# 2_keys.net
KiCad netlist of a schematic drawn in Altium Designer
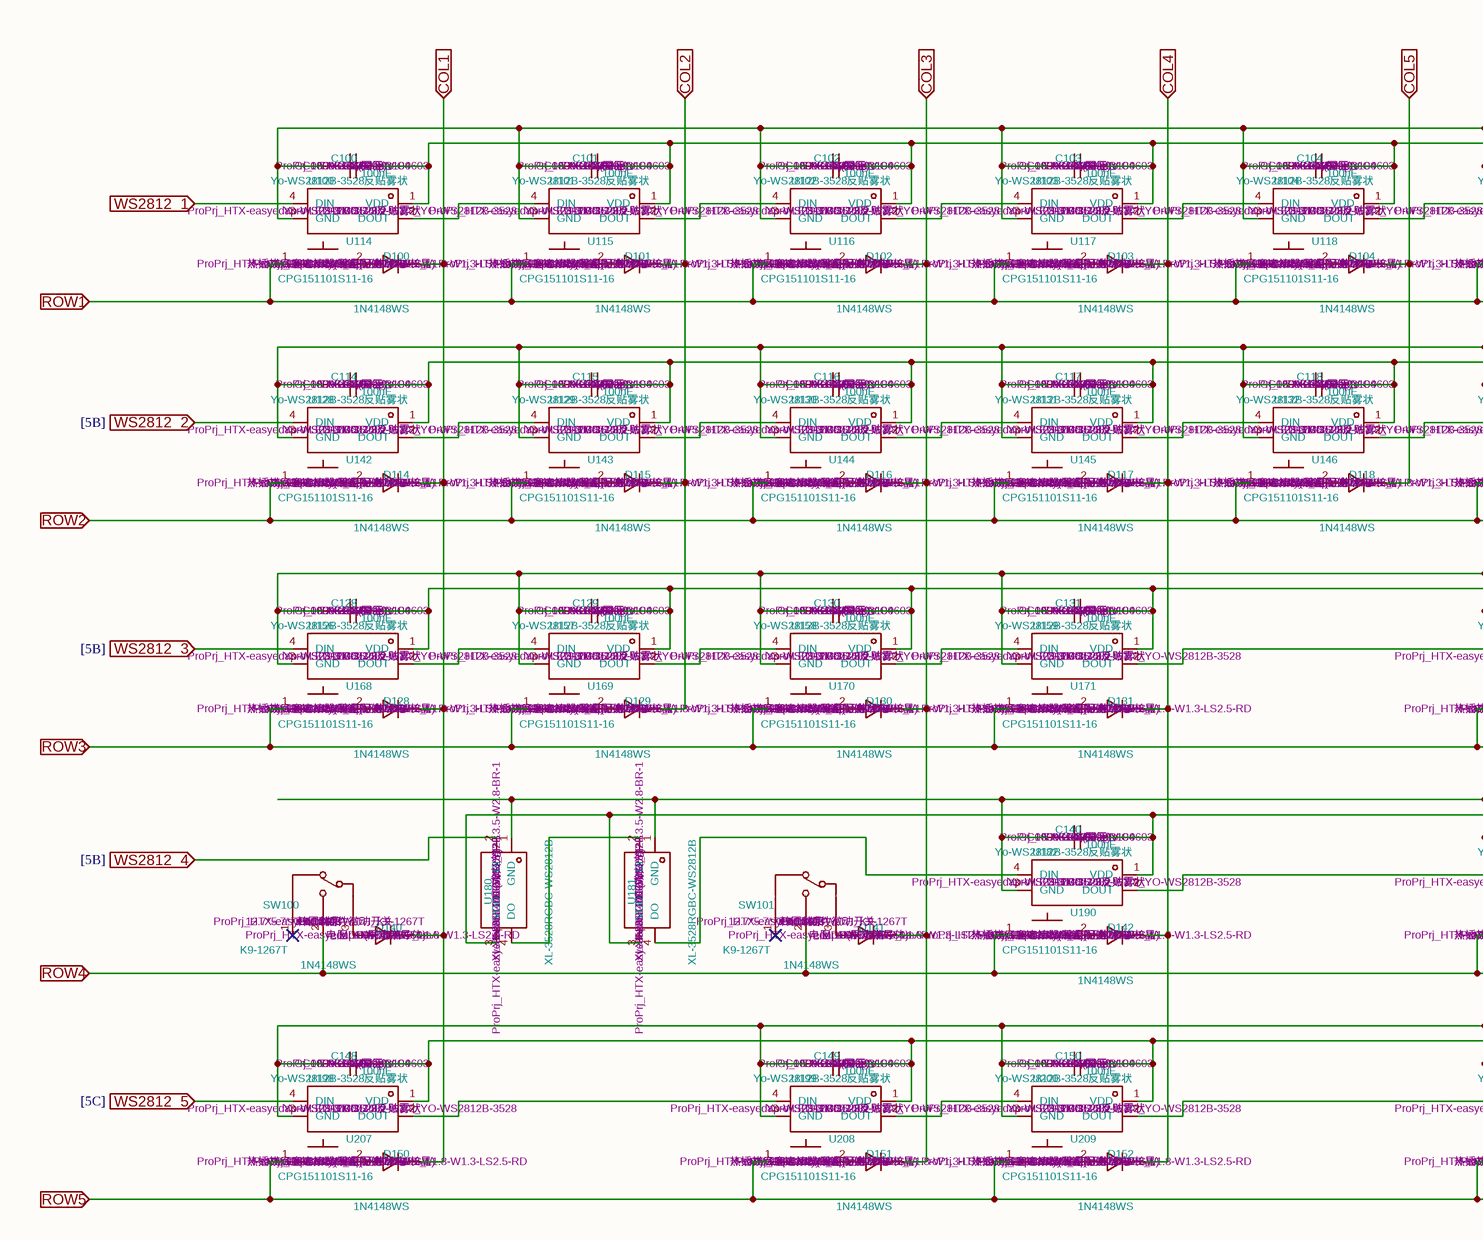
[diagram p0: 2_keys.SchDoc, left]
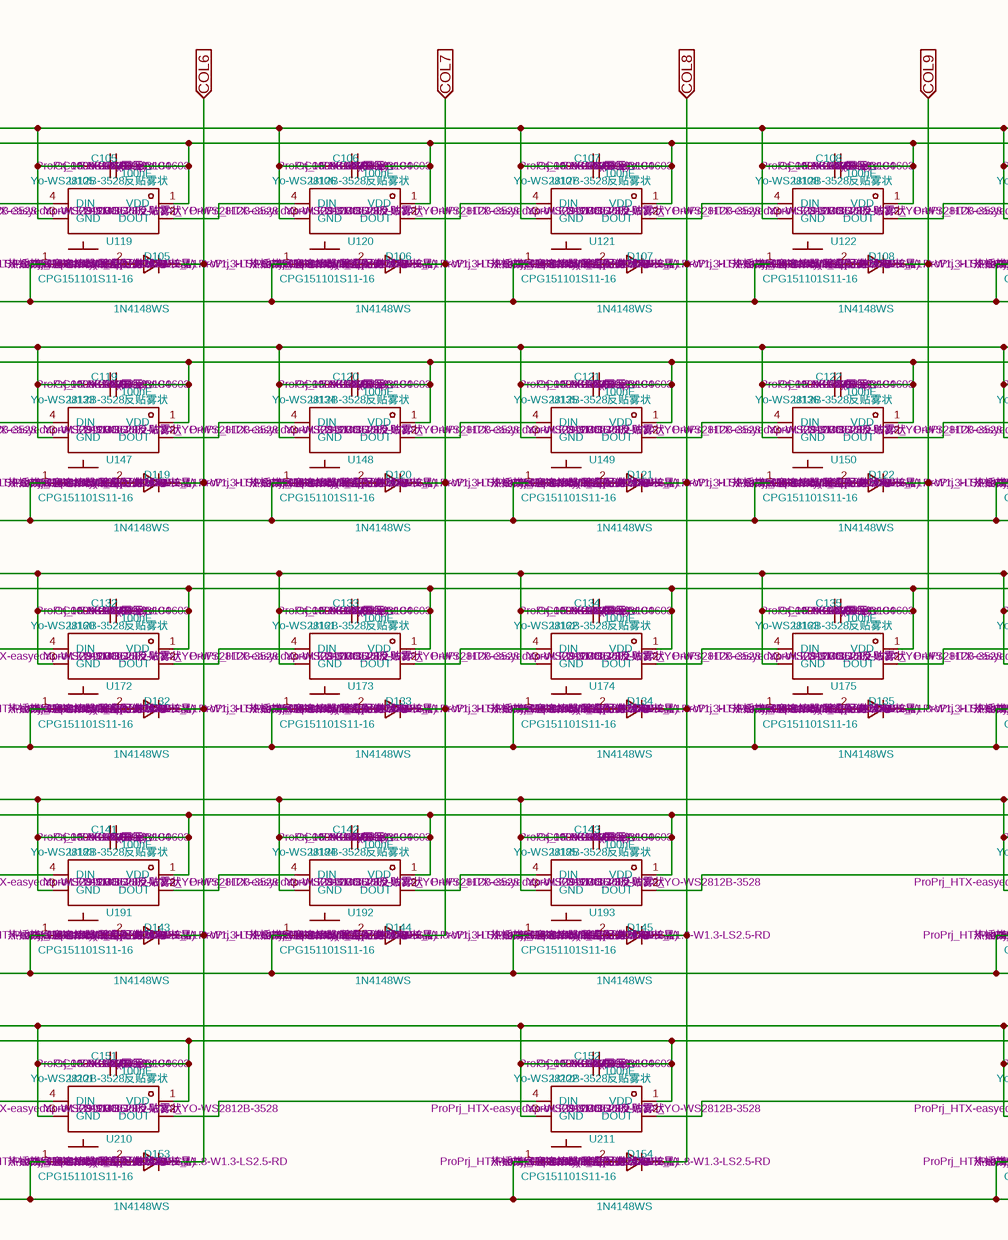
[diagram p1: 2_keys.SchDoc, middle]
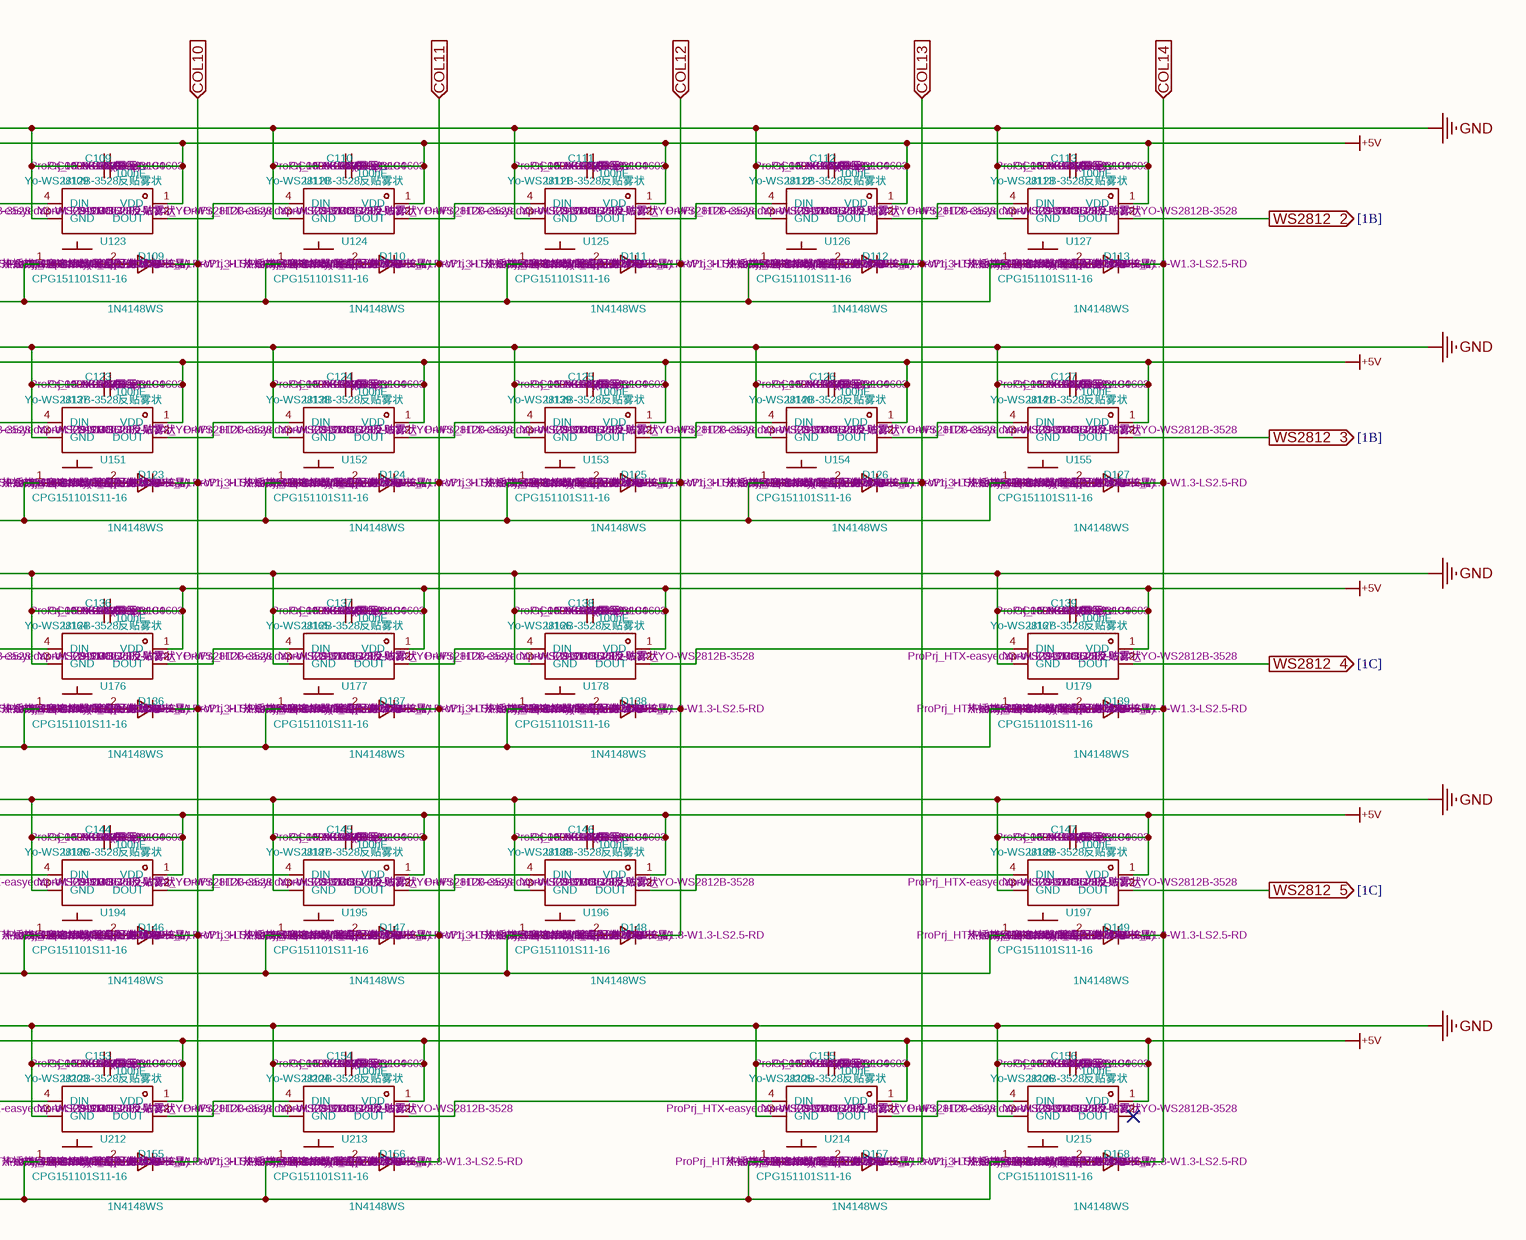
[diagram p2: 2_keys.SchDoc, right]

(export (version "E")
  (design (tool "Eeschema 10.0.6"))
  (components
    (comp (ref "C100")
      (value "100nF")
      (footprint "ProPrj_HTX-easyedapro:C0603")
      (fields
        (field (name "MANUFACTURER PART") "CC0603KRX7R9BB104")
        (field (name "MANUFACTURER") "YAGEO(国巨)")
        (field (name "SUPPLIER PART") "C14663")
        (field (name "SUPPLIER") "LCSC")
        (field (name "LCSC PART NAME") "100nF ±10% 50V")
      )
      (libsource (lib "easyedapro") (part "CC0603KRX7R9BB104"))
    )
    (comp (ref "C101")
      (value "100nF")
      (footprint "ProPrj_HTX-easyedapro:C0603")
      (fields
        (field (name "MANUFACTURER PART") "CC0603KRX7R9BB104")
        (field (name "MANUFACTURER") "YAGEO(国巨)")
        (field (name "SUPPLIER PART") "C14663")
        (field (name "SUPPLIER") "LCSC")
        (field (name "LCSC PART NAME") "100nF ±10% 50V")
      )
      (libsource (lib "easyedapro") (part "CC0603KRX7R9BB104"))
    )
    (comp (ref "C102")
      (value "100nF")
      (footprint "ProPrj_HTX-easyedapro:C0603")
      (fields
        (field (name "MANUFACTURER PART") "CC0603KRX7R9BB104")
        (field (name "MANUFACTURER") "YAGEO(国巨)")
        (field (name "SUPPLIER PART") "C14663")
        (field (name "SUPPLIER") "LCSC")
        (field (name "LCSC PART NAME") "100nF ±10% 50V")
      )
      (libsource (lib "easyedapro") (part "CC0603KRX7R9BB104"))
    )
    (comp (ref "C103")
      (value "100nF")
      (footprint "ProPrj_HTX-easyedapro:C0603")
      (fields
        (field (name "MANUFACTURER PART") "CC0603KRX7R9BB104")
        (field (name "MANUFACTURER") "YAGEO(国巨)")
        (field (name "SUPPLIER PART") "C14663")
        (field (name "SUPPLIER") "LCSC")
        (field (name "LCSC PART NAME") "100nF ±10% 50V")
      )
      (libsource (lib "easyedapro") (part "CC0603KRX7R9BB104"))
    )
    (comp (ref "C104")
      (value "100nF")
      (footprint "ProPrj_HTX-easyedapro:C0603")
      (fields
        (field (name "MANUFACTURER PART") "CC0603KRX7R9BB104")
        (field (name "MANUFACTURER") "YAGEO(国巨)")
        (field (name "SUPPLIER PART") "C14663")
        (field (name "SUPPLIER") "LCSC")
        (field (name "LCSC PART NAME") "100nF ±10% 50V")
      )
      (libsource (lib "easyedapro") (part "CC0603KRX7R9BB104"))
    )
    (comp (ref "C105")
      (value "100nF")
      (footprint "ProPrj_HTX-easyedapro:C0603")
      (fields
        (field (name "MANUFACTURER PART") "CC0603KRX7R9BB104")
        (field (name "MANUFACTURER") "YAGEO(国巨)")
        (field (name "SUPPLIER PART") "C14663")
        (field (name "SUPPLIER") "LCSC")
        (field (name "LCSC PART NAME") "100nF ±10% 50V")
      )
      (libsource (lib "easyedapro") (part "CC0603KRX7R9BB104"))
    )
    (comp (ref "C106")
      (value "100nF")
      (footprint "ProPrj_HTX-easyedapro:C0603")
      (fields
        (field (name "MANUFACTURER PART") "CC0603KRX7R9BB104")
        (field (name "MANUFACTURER") "YAGEO(国巨)")
        (field (name "SUPPLIER PART") "C14663")
        (field (name "SUPPLIER") "LCSC")
        (field (name "LCSC PART NAME") "100nF ±10% 50V")
      )
      (libsource (lib "easyedapro") (part "CC0603KRX7R9BB104"))
    )
    (comp (ref "C107")
      (value "100nF")
      (footprint "ProPrj_HTX-easyedapro:C0603")
      (fields
        (field (name "MANUFACTURER PART") "CC0603KRX7R9BB104")
        (field (name "MANUFACTURER") "YAGEO(国巨)")
        (field (name "SUPPLIER PART") "C14663")
        (field (name "SUPPLIER") "LCSC")
        (field (name "LCSC PART NAME") "100nF ±10% 50V")
      )
      (libsource (lib "easyedapro") (part "CC0603KRX7R9BB104"))
    )
    (comp (ref "C108")
      (value "100nF")
      (footprint "ProPrj_HTX-easyedapro:C0603")
      (fields
        (field (name "MANUFACTURER PART") "CC0603KRX7R9BB104")
        (field (name "MANUFACTURER") "YAGEO(国巨)")
        (field (name "SUPPLIER PART") "C14663")
        (field (name "SUPPLIER") "LCSC")
        (field (name "LCSC PART NAME") "100nF ±10% 50V")
      )
      (libsource (lib "easyedapro") (part "CC0603KRX7R9BB104"))
    )
    (comp (ref "C109")
      (value "100nF")
      (footprint "ProPrj_HTX-easyedapro:C0603")
      (fields
        (field (name "MANUFACTURER PART") "CC0603KRX7R9BB104")
        (field (name "MANUFACTURER") "YAGEO(国巨)")
        (field (name "SUPPLIER PART") "C14663")
        (field (name "SUPPLIER") "LCSC")
        (field (name "LCSC PART NAME") "100nF ±10% 50V")
      )
      (libsource (lib "easyedapro") (part "CC0603KRX7R9BB104"))
    )
    (comp (ref "C110")
      (value "100nF")
      (footprint "ProPrj_HTX-easyedapro:C0603")
      (fields
        (field (name "MANUFACTURER PART") "CC0603KRX7R9BB104")
        (field (name "MANUFACTURER") "YAGEO(国巨)")
        (field (name "SUPPLIER PART") "C14663")
        (field (name "SUPPLIER") "LCSC")
        (field (name "LCSC PART NAME") "100nF ±10% 50V")
      )
      (libsource (lib "easyedapro") (part "CC0603KRX7R9BB104"))
    )
    (comp (ref "C111")
      (value "100nF")
      (footprint "ProPrj_HTX-easyedapro:C0603")
      (fields
        (field (name "MANUFACTURER PART") "CC0603KRX7R9BB104")
        (field (name "MANUFACTURER") "YAGEO(国巨)")
        (field (name "SUPPLIER PART") "C14663")
        (field (name "SUPPLIER") "LCSC")
        (field (name "LCSC PART NAME") "100nF ±10% 50V")
      )
      (libsource (lib "easyedapro") (part "CC0603KRX7R9BB104"))
    )
    (comp (ref "C112")
      (value "100nF")
      (footprint "ProPrj_HTX-easyedapro:C0603")
      (fields
        (field (name "MANUFACTURER PART") "CC0603KRX7R9BB104")
        (field (name "MANUFACTURER") "YAGEO(国巨)")
        (field (name "SUPPLIER PART") "C14663")
        (field (name "SUPPLIER") "LCSC")
        (field (name "LCSC PART NAME") "100nF ±10% 50V")
      )
      (libsource (lib "easyedapro") (part "CC0603KRX7R9BB104"))
    )
    (comp (ref "C113")
      (value "100nF")
      (footprint "ProPrj_HTX-easyedapro:C0603")
      (fields
        (field (name "MANUFACTURER PART") "CC0603KRX7R9BB104")
        (field (name "MANUFACTURER") "YAGEO(国巨)")
        (field (name "SUPPLIER PART") "C14663")
        (field (name "SUPPLIER") "LCSC")
        (field (name "LCSC PART NAME") "100nF ±10% 50V")
      )
      (libsource (lib "easyedapro") (part "CC0603KRX7R9BB104"))
    )
    (comp (ref "C114")
      (value "100nF")
      (footprint "ProPrj_HTX-easyedapro:C0603")
      (fields
        (field (name "MANUFACTURER PART") "CC0603KRX7R9BB104")
        (field (name "MANUFACTURER") "YAGEO(国巨)")
        (field (name "SUPPLIER PART") "C14663")
        (field (name "SUPPLIER") "LCSC")
        (field (name "LCSC PART NAME") "100nF ±10% 50V")
      )
      (libsource (lib "easyedapro") (part "CC0603KRX7R9BB104"))
    )
    (comp (ref "C115")
      (value "100nF")
      (footprint "ProPrj_HTX-easyedapro:C0603")
      (fields
        (field (name "MANUFACTURER PART") "CC0603KRX7R9BB104")
        (field (name "MANUFACTURER") "YAGEO(国巨)")
        (field (name "SUPPLIER PART") "C14663")
        (field (name "SUPPLIER") "LCSC")
        (field (name "LCSC PART NAME") "100nF ±10% 50V")
      )
      (libsource (lib "easyedapro") (part "CC0603KRX7R9BB104"))
    )
    (comp (ref "C116")
      (value "100nF")
      (footprint "ProPrj_HTX-easyedapro:C0603")
      (fields
        (field (name "MANUFACTURER PART") "CC0603KRX7R9BB104")
        (field (name "MANUFACTURER") "YAGEO(国巨)")
        (field (name "SUPPLIER PART") "C14663")
        (field (name "SUPPLIER") "LCSC")
        (field (name "LCSC PART NAME") "100nF ±10% 50V")
      )
      (libsource (lib "easyedapro") (part "CC0603KRX7R9BB104"))
    )
    (comp (ref "C117")
      (value "100nF")
      (footprint "ProPrj_HTX-easyedapro:C0603")
      (fields
        (field (name "MANUFACTURER PART") "CC0603KRX7R9BB104")
        (field (name "MANUFACTURER") "YAGEO(国巨)")
        (field (name "SUPPLIER PART") "C14663")
        (field (name "SUPPLIER") "LCSC")
        (field (name "LCSC PART NAME") "100nF ±10% 50V")
      )
      (libsource (lib "easyedapro") (part "CC0603KRX7R9BB104"))
    )
    (comp (ref "C118")
      (value "100nF")
      (footprint "ProPrj_HTX-easyedapro:C0603")
      (fields
        (field (name "MANUFACTURER PART") "CC0603KRX7R9BB104")
        (field (name "MANUFACTURER") "YAGEO(国巨)")
        (field (name "SUPPLIER PART") "C14663")
        (field (name "SUPPLIER") "LCSC")
        (field (name "LCSC PART NAME") "100nF ±10% 50V")
      )
      (libsource (lib "easyedapro") (part "CC0603KRX7R9BB104"))
    )
    (comp (ref "C119")
      (value "100nF")
      (footprint "ProPrj_HTX-easyedapro:C0603")
      (fields
        (field (name "MANUFACTURER PART") "CC0603KRX7R9BB104")
        (field (name "MANUFACTURER") "YAGEO(国巨)")
        (field (name "SUPPLIER PART") "C14663")
        (field (name "SUPPLIER") "LCSC")
        (field (name "LCSC PART NAME") "100nF ±10% 50V")
      )
      (libsource (lib "easyedapro") (part "CC0603KRX7R9BB104"))
    )
    (comp (ref "C120")
      (value "100nF")
      (footprint "ProPrj_HTX-easyedapro:C0603")
      (fields
        (field (name "MANUFACTURER PART") "CC0603KRX7R9BB104")
        (field (name "MANUFACTURER") "YAGEO(国巨)")
        (field (name "SUPPLIER PART") "C14663")
        (field (name "SUPPLIER") "LCSC")
        (field (name "LCSC PART NAME") "100nF ±10% 50V")
      )
      (libsource (lib "easyedapro") (part "CC0603KRX7R9BB104"))
    )
    (comp (ref "C121")
      (value "100nF")
      (footprint "ProPrj_HTX-easyedapro:C0603")
      (fields
        (field (name "MANUFACTURER PART") "CC0603KRX7R9BB104")
        (field (name "MANUFACTURER") "YAGEO(国巨)")
        (field (name "SUPPLIER PART") "C14663")
        (field (name "SUPPLIER") "LCSC")
        (field (name "LCSC PART NAME") "100nF ±10% 50V")
      )
      (libsource (lib "easyedapro") (part "CC0603KRX7R9BB104"))
    )
    (comp (ref "C122")
      (value "100nF")
      (footprint "ProPrj_HTX-easyedapro:C0603")
      (fields
        (field (name "MANUFACTURER PART") "CC0603KRX7R9BB104")
        (field (name "MANUFACTURER") "YAGEO(国巨)")
        (field (name "SUPPLIER PART") "C14663")
        (field (name "SUPPLIER") "LCSC")
        (field (name "LCSC PART NAME") "100nF ±10% 50V")
      )
      (libsource (lib "easyedapro") (part "CC0603KRX7R9BB104"))
    )
    (comp (ref "C123")
      (value "100nF")
      (footprint "ProPrj_HTX-easyedapro:C0603")
      (fields
        (field (name "MANUFACTURER PART") "CC0603KRX7R9BB104")
        (field (name "MANUFACTURER") "YAGEO(国巨)")
        (field (name "SUPPLIER PART") "C14663")
        (field (name "SUPPLIER") "LCSC")
        (field (name "LCSC PART NAME") "100nF ±10% 50V")
      )
      (libsource (lib "easyedapro") (part "CC0603KRX7R9BB104"))
    )
    (comp (ref "C124")
      (value "100nF")
      (footprint "ProPrj_HTX-easyedapro:C0603")
      (fields
        (field (name "MANUFACTURER PART") "CC0603KRX7R9BB104")
        (field (name "MANUFACTURER") "YAGEO(国巨)")
        (field (name "SUPPLIER PART") "C14663")
        (field (name "SUPPLIER") "LCSC")
        (field (name "LCSC PART NAME") "100nF ±10% 50V")
      )
      (libsource (lib "easyedapro") (part "CC0603KRX7R9BB104"))
    )
    (comp (ref "C125")
      (value "100nF")
      (footprint "ProPrj_HTX-easyedapro:C0603")
      (fields
        (field (name "MANUFACTURER PART") "CC0603KRX7R9BB104")
        (field (name "MANUFACTURER") "YAGEO(国巨)")
        (field (name "SUPPLIER PART") "C14663")
        (field (name "SUPPLIER") "LCSC")
        (field (name "LCSC PART NAME") "100nF ±10% 50V")
      )
      (libsource (lib "easyedapro") (part "CC0603KRX7R9BB104"))
    )
    (comp (ref "C126")
      (value "100nF")
      (footprint "ProPrj_HTX-easyedapro:C0603")
      (fields
        (field (name "MANUFACTURER PART") "CC0603KRX7R9BB104")
        (field (name "MANUFACTURER") "YAGEO(国巨)")
        (field (name "SUPPLIER PART") "C14663")
        (field (name "SUPPLIER") "LCSC")
        (field (name "LCSC PART NAME") "100nF ±10% 50V")
      )
      (libsource (lib "easyedapro") (part "CC0603KRX7R9BB104"))
    )
    (comp (ref "C127")
      (value "100nF")
      (footprint "ProPrj_HTX-easyedapro:C0603")
      (fields
        (field (name "MANUFACTURER PART") "CC0603KRX7R9BB104")
        (field (name "MANUFACTURER") "YAGEO(国巨)")
        (field (name "SUPPLIER PART") "C14663")
        (field (name "SUPPLIER") "LCSC")
        (field (name "LCSC PART NAME") "100nF ±10% 50V")
      )
      (libsource (lib "easyedapro") (part "CC0603KRX7R9BB104"))
    )
    (comp (ref "C128")
      (value "100nF")
      (footprint "ProPrj_HTX-easyedapro:C0603")
      (fields
        (field (name "MANUFACTURER PART") "CC0603KRX7R9BB104")
        (field (name "MANUFACTURER") "YAGEO(国巨)")
        (field (name "SUPPLIER PART") "C14663")
        (field (name "SUPPLIER") "LCSC")
        (field (name "LCSC PART NAME") "100nF ±10% 50V")
      )
      (libsource (lib "easyedapro") (part "CC0603KRX7R9BB104"))
    )
    (comp (ref "C129")
      (value "100nF")
      (footprint "ProPrj_HTX-easyedapro:C0603")
      (fields
        (field (name "MANUFACTURER PART") "CC0603KRX7R9BB104")
        (field (name "MANUFACTURER") "YAGEO(国巨)")
        (field (name "SUPPLIER PART") "C14663")
        (field (name "SUPPLIER") "LCSC")
        (field (name "LCSC PART NAME") "100nF ±10% 50V")
      )
      (libsource (lib "easyedapro") (part "CC0603KRX7R9BB104"))
    )
    (comp (ref "C130")
      (value "100nF")
      (footprint "ProPrj_HTX-easyedapro:C0603")
      (fields
        (field (name "MANUFACTURER PART") "CC0603KRX7R9BB104")
        (field (name "MANUFACTURER") "YAGEO(国巨)")
        (field (name "SUPPLIER PART") "C14663")
        (field (name "SUPPLIER") "LCSC")
        (field (name "LCSC PART NAME") "100nF ±10% 50V")
      )
      (libsource (lib "easyedapro") (part "CC0603KRX7R9BB104"))
    )
    (comp (ref "C131")
      (value "100nF")
      (footprint "ProPrj_HTX-easyedapro:C0603")
      (fields
        (field (name "MANUFACTURER PART") "CC0603KRX7R9BB104")
        (field (name "MANUFACTURER") "YAGEO(国巨)")
        (field (name "SUPPLIER PART") "C14663")
        (field (name "SUPPLIER") "LCSC")
        (field (name "LCSC PART NAME") "100nF ±10% 50V")
      )
      (libsource (lib "easyedapro") (part "CC0603KRX7R9BB104"))
    )
    (comp (ref "C132")
      (value "100nF")
      (footprint "ProPrj_HTX-easyedapro:C0603")
      (fields
        (field (name "MANUFACTURER PART") "CC0603KRX7R9BB104")
        (field (name "MANUFACTURER") "YAGEO(国巨)")
        (field (name "SUPPLIER PART") "C14663")
        (field (name "SUPPLIER") "LCSC")
        (field (name "LCSC PART NAME") "100nF ±10% 50V")
      )
      (libsource (lib "easyedapro") (part "CC0603KRX7R9BB104"))
    )
    (comp (ref "C133")
      (value "100nF")
      (footprint "ProPrj_HTX-easyedapro:C0603")
      (fields
        (field (name "MANUFACTURER PART") "CC0603KRX7R9BB104")
        (field (name "MANUFACTURER") "YAGEO(国巨)")
        (field (name "SUPPLIER PART") "C14663")
        (field (name "SUPPLIER") "LCSC")
        (field (name "LCSC PART NAME") "100nF ±10% 50V")
      )
      (libsource (lib "easyedapro") (part "CC0603KRX7R9BB104"))
    )
    (comp (ref "C134")
      (value "100nF")
      (footprint "ProPrj_HTX-easyedapro:C0603")
      (fields
        (field (name "MANUFACTURER PART") "CC0603KRX7R9BB104")
        (field (name "MANUFACTURER") "YAGEO(国巨)")
        (field (name "SUPPLIER PART") "C14663")
        (field (name "SUPPLIER") "LCSC")
        (field (name "LCSC PART NAME") "100nF ±10% 50V")
      )
      (libsource (lib "easyedapro") (part "CC0603KRX7R9BB104"))
    )
    (comp (ref "C135")
      (value "100nF")
      (footprint "ProPrj_HTX-easyedapro:C0603")
      (fields
        (field (name "MANUFACTURER PART") "CC0603KRX7R9BB104")
        (field (name "MANUFACTURER") "YAGEO(国巨)")
        (field (name "SUPPLIER PART") "C14663")
        (field (name "SUPPLIER") "LCSC")
        (field (name "LCSC PART NAME") "100nF ±10% 50V")
      )
      (libsource (lib "easyedapro") (part "CC0603KRX7R9BB104"))
    )
    (comp (ref "C136")
      (value "100nF")
      (footprint "ProPrj_HTX-easyedapro:C0603")
      (fields
        (field (name "MANUFACTURER PART") "CC0603KRX7R9BB104")
        (field (name "MANUFACTURER") "YAGEO(国巨)")
        (field (name "SUPPLIER PART") "C14663")
        (field (name "SUPPLIER") "LCSC")
        (field (name "LCSC PART NAME") "100nF ±10% 50V")
      )
      (libsource (lib "easyedapro") (part "CC0603KRX7R9BB104"))
    )
    (comp (ref "C137")
      (value "100nF")
      (footprint "ProPrj_HTX-easyedapro:C0603")
      (fields
        (field (name "MANUFACTURER PART") "CC0603KRX7R9BB104")
        (field (name "MANUFACTURER") "YAGEO(国巨)")
        (field (name "SUPPLIER PART") "C14663")
        (field (name "SUPPLIER") "LCSC")
        (field (name "LCSC PART NAME") "100nF ±10% 50V")
      )
      (libsource (lib "easyedapro") (part "CC0603KRX7R9BB104"))
    )
    (comp (ref "C138")
      (value "100nF")
      (footprint "ProPrj_HTX-easyedapro:C0603")
      (fields
        (field (name "MANUFACTURER PART") "CC0603KRX7R9BB104")
        (field (name "MANUFACTURER") "YAGEO(国巨)")
        (field (name "SUPPLIER PART") "C14663")
        (field (name "SUPPLIER") "LCSC")
        (field (name "LCSC PART NAME") "100nF ±10% 50V")
      )
      (libsource (lib "easyedapro") (part "CC0603KRX7R9BB104"))
    )
    (comp (ref "C139")
      (value "100nF")
      (footprint "ProPrj_HTX-easyedapro:C0603")
      (fields
        (field (name "MANUFACTURER PART") "CC0603KRX7R9BB104")
        (field (name "MANUFACTURER") "YAGEO(国巨)")
        (field (name "SUPPLIER PART") "C14663")
        (field (name "SUPPLIER") "LCSC")
        (field (name "LCSC PART NAME") "100nF ±10% 50V")
      )
      (libsource (lib "easyedapro") (part "CC0603KRX7R9BB104"))
    )
    (comp (ref "C140")
      (value "100nF")
      (footprint "ProPrj_HTX-easyedapro:C0603")
      (fields
        (field (name "MANUFACTURER PART") "CC0603KRX7R9BB104")
        (field (name "MANUFACTURER") "YAGEO(国巨)")
        (field (name "SUPPLIER PART") "C14663")
        (field (name "SUPPLIER") "LCSC")
        (field (name "LCSC PART NAME") "100nF ±10% 50V")
      )
      (libsource (lib "easyedapro") (part "CC0603KRX7R9BB104"))
    )
    (comp (ref "C141")
      (value "100nF")
      (footprint "ProPrj_HTX-easyedapro:C0603")
      (fields
        (field (name "MANUFACTURER PART") "CC0603KRX7R9BB104")
        (field (name "MANUFACTURER") "YAGEO(国巨)")
        (field (name "SUPPLIER PART") "C14663")
        (field (name "SUPPLIER") "LCSC")
        (field (name "LCSC PART NAME") "100nF ±10% 50V")
      )
      (libsource (lib "easyedapro") (part "CC0603KRX7R9BB104"))
    )
    (comp (ref "C142")
      (value "100nF")
      (footprint "ProPrj_HTX-easyedapro:C0603")
      (fields
        (field (name "MANUFACTURER PART") "CC0603KRX7R9BB104")
        (field (name "MANUFACTURER") "YAGEO(国巨)")
        (field (name "SUPPLIER PART") "C14663")
        (field (name "SUPPLIER") "LCSC")
        (field (name "LCSC PART NAME") "100nF ±10% 50V")
      )
      (libsource (lib "easyedapro") (part "CC0603KRX7R9BB104"))
    )
    (comp (ref "C143")
      (value "100nF")
      (footprint "ProPrj_HTX-easyedapro:C0603")
      (fields
        (field (name "MANUFACTURER PART") "CC0603KRX7R9BB104")
        (field (name "MANUFACTURER") "YAGEO(国巨)")
        (field (name "SUPPLIER PART") "C14663")
        (field (name "SUPPLIER") "LCSC")
        (field (name "LCSC PART NAME") "100nF ±10% 50V")
      )
      (libsource (lib "easyedapro") (part "CC0603KRX7R9BB104"))
    )
    (comp (ref "C144")
      (value "100nF")
      (footprint "ProPrj_HTX-easyedapro:C0603")
      (fields
        (field (name "MANUFACTURER PART") "CC0603KRX7R9BB104")
        (field (name "MANUFACTURER") "YAGEO(国巨)")
        (field (name "SUPPLIER PART") "C14663")
        (field (name "SUPPLIER") "LCSC")
        (field (name "LCSC PART NAME") "100nF ±10% 50V")
      )
      (libsource (lib "easyedapro") (part "CC0603KRX7R9BB104"))
    )
    (comp (ref "C145")
      (value "100nF")
      (footprint "ProPrj_HTX-easyedapro:C0603")
      (fields
        (field (name "MANUFACTURER PART") "CC0603KRX7R9BB104")
        (field (name "MANUFACTURER") "YAGEO(国巨)")
        (field (name "SUPPLIER PART") "C14663")
        (field (name "SUPPLIER") "LCSC")
        (field (name "LCSC PART NAME") "100nF ±10% 50V")
      )
      (libsource (lib "easyedapro") (part "CC0603KRX7R9BB104"))
    )
    (comp (ref "C146")
      (value "100nF")
      (footprint "ProPrj_HTX-easyedapro:C0603")
      (fields
        (field (name "MANUFACTURER PART") "CC0603KRX7R9BB104")
        (field (name "MANUFACTURER") "YAGEO(国巨)")
        (field (name "SUPPLIER PART") "C14663")
        (field (name "SUPPLIER") "LCSC")
        (field (name "LCSC PART NAME") "100nF ±10% 50V")
      )
      (libsource (lib "easyedapro") (part "CC0603KRX7R9BB104"))
    )
    (comp (ref "C147")
      (value "100nF")
      (footprint "ProPrj_HTX-easyedapro:C0603")
      (fields
        (field (name "MANUFACTURER PART") "CC0603KRX7R9BB104")
        (field (name "MANUFACTURER") "YAGEO(国巨)")
        (field (name "SUPPLIER PART") "C14663")
        (field (name "SUPPLIER") "LCSC")
        (field (name "LCSC PART NAME") "100nF ±10% 50V")
      )
      (libsource (lib "easyedapro") (part "CC0603KRX7R9BB104"))
    )
    (comp (ref "C148")
      (value "100nF")
      (footprint "ProPrj_HTX-easyedapro:C0603")
      (fields
        (field (name "MANUFACTURER PART") "CC0603KRX7R9BB104")
        (field (name "MANUFACTURER") "YAGEO(国巨)")
        (field (name "SUPPLIER PART") "C14663")
        (field (name "SUPPLIER") "LCSC")
        (field (name "LCSC PART NAME") "100nF ±10% 50V")
      )
      (libsource (lib "easyedapro") (part "CC0603KRX7R9BB104"))
    )
    (comp (ref "C149")
      (value "100nF")
      (footprint "ProPrj_HTX-easyedapro:C0603")
      (fields
        (field (name "MANUFACTURER PART") "CC0603KRX7R9BB104")
        (field (name "MANUFACTURER") "YAGEO(国巨)")
        (field (name "SUPPLIER PART") "C14663")
        (field (name "SUPPLIER") "LCSC")
        (field (name "LCSC PART NAME") "100nF ±10% 50V")
      )
      (libsource (lib "easyedapro") (part "CC0603KRX7R9BB104"))
    )
    (comp (ref "C150")
      (value "100nF")
      (footprint "ProPrj_HTX-easyedapro:C0603")
      (fields
        (field (name "MANUFACTURER PART") "CC0603KRX7R9BB104")
        (field (name "MANUFACTURER") "YAGEO(国巨)")
        (field (name "SUPPLIER PART") "C14663")
        (field (name "SUPPLIER") "LCSC")
        (field (name "LCSC PART NAME") "100nF ±10% 50V")
      )
      (libsource (lib "easyedapro") (part "CC0603KRX7R9BB104"))
    )
    (comp (ref "C151")
      (value "100nF")
      (footprint "ProPrj_HTX-easyedapro:C0603")
      (fields
        (field (name "MANUFACTURER PART") "CC0603KRX7R9BB104")
        (field (name "MANUFACTURER") "YAGEO(国巨)")
        (field (name "SUPPLIER PART") "C14663")
        (field (name "SUPPLIER") "LCSC")
        (field (name "LCSC PART NAME") "100nF ±10% 50V")
      )
      (libsource (lib "easyedapro") (part "CC0603KRX7R9BB104"))
    )
    (comp (ref "C152")
      (value "100nF")
      (footprint "ProPrj_HTX-easyedapro:C0603")
      (fields
        (field (name "MANUFACTURER PART") "CC0603KRX7R9BB104")
        (field (name "MANUFACTURER") "YAGEO(国巨)")
        (field (name "SUPPLIER PART") "C14663")
        (field (name "SUPPLIER") "LCSC")
        (field (name "LCSC PART NAME") "100nF ±10% 50V")
      )
      (libsource (lib "easyedapro") (part "CC0603KRX7R9BB104"))
    )
    (comp (ref "C153")
      (value "100nF")
      (footprint "ProPrj_HTX-easyedapro:C0603")
      (fields
        (field (name "MANUFACTURER PART") "CC0603KRX7R9BB104")
        (field (name "MANUFACTURER") "YAGEO(国巨)")
        (field (name "SUPPLIER PART") "C14663")
        (field (name "SUPPLIER") "LCSC")
        (field (name "LCSC PART NAME") "100nF ±10% 50V")
      )
      (libsource (lib "easyedapro") (part "CC0603KRX7R9BB104"))
    )
    (comp (ref "C154")
      (value "100nF")
      (footprint "ProPrj_HTX-easyedapro:C0603")
      (fields
        (field (name "MANUFACTURER PART") "CC0603KRX7R9BB104")
        (field (name "MANUFACTURER") "YAGEO(国巨)")
        (field (name "SUPPLIER PART") "C14663")
        (field (name "SUPPLIER") "LCSC")
        (field (name "LCSC PART NAME") "100nF ±10% 50V")
      )
      (libsource (lib "easyedapro") (part "CC0603KRX7R9BB104"))
    )
    (comp (ref "C155")
      (value "100nF")
      (footprint "ProPrj_HTX-easyedapro:C0603")
      (fields
        (field (name "MANUFACTURER PART") "CC0603KRX7R9BB104")
        (field (name "MANUFACTURER") "YAGEO(国巨)")
        (field (name "SUPPLIER PART") "C14663")
        (field (name "SUPPLIER") "LCSC")
        (field (name "LCSC PART NAME") "100nF ±10% 50V")
      )
      (libsource (lib "easyedapro") (part "CC0603KRX7R9BB104"))
    )
    (comp (ref "C156")
      (value "100nF")
      (footprint "ProPrj_HTX-easyedapro:C0603")
      (fields
        (field (name "MANUFACTURER PART") "CC0603KRX7R9BB104")
        (field (name "MANUFACTURER") "YAGEO(国巨)")
        (field (name "SUPPLIER PART") "C14663")
        (field (name "SUPPLIER") "LCSC")
        (field (name "LCSC PART NAME") "100nF ±10% 50V")
      )
      (libsource (lib "easyedapro") (part "CC0603KRX7R9BB104"))
    )
    (comp (ref "D100")
      (value "1N4148WS")
      (footprint "ProPrj_HTX-easyedapro:SOD-323_L1.8-W1.3-LS2.5-RD")
      (fields
        (field (name "MANUFACTURER PART") "1N4148WS")
        (field (name "MANUFACTURER") "CJ(江苏长电/长晶)")
        (field (name "SUPPLIER PART") "C2128")
        (field (name "SUPPLIER") "LCSC")
        (field (name "LCSC PART NAME") "丝印T4")
      )
      (libsource (lib "easyedapro") (part "1N4148WS T4"))
    )
    (comp (ref "D101")
      (value "1N4148WS")
      (footprint "ProPrj_HTX-easyedapro:SOD-323_L1.8-W1.3-LS2.5-RD")
      (fields
        (field (name "MANUFACTURER PART") "1N4148WS")
        (field (name "MANUFACTURER") "CJ(江苏长电/长晶)")
        (field (name "SUPPLIER PART") "C2128")
        (field (name "SUPPLIER") "LCSC")
        (field (name "LCSC PART NAME") "丝印T4")
      )
      (libsource (lib "easyedapro") (part "1N4148WS T4"))
    )
    (comp (ref "D102")
      (value "1N4148WS")
      (footprint "ProPrj_HTX-easyedapro:SOD-323_L1.8-W1.3-LS2.5-RD")
      (fields
        (field (name "MANUFACTURER PART") "1N4148WS")
        (field (name "MANUFACTURER") "CJ(江苏长电/长晶)")
        (field (name "SUPPLIER PART") "C2128")
        (field (name "SUPPLIER") "LCSC")
        (field (name "LCSC PART NAME") "丝印T4")
      )
      (libsource (lib "easyedapro") (part "1N4148WS T4"))
    )
    (comp (ref "D103")
      (value "1N4148WS")
      (footprint "ProPrj_HTX-easyedapro:SOD-323_L1.8-W1.3-LS2.5-RD")
      (fields
        (field (name "MANUFACTURER PART") "1N4148WS")
        (field (name "MANUFACTURER") "CJ(江苏长电/长晶)")
        (field (name "SUPPLIER PART") "C2128")
        (field (name "SUPPLIER") "LCSC")
        (field (name "LCSC PART NAME") "丝印T4")
      )
      (libsource (lib "easyedapro") (part "1N4148WS T4"))
    )
    (comp (ref "D104")
      (value "1N4148WS")
      (footprint "ProPrj_HTX-easyedapro:SOD-323_L1.8-W1.3-LS2.5-RD")
      (fields
        (field (name "MANUFACTURER PART") "1N4148WS")
        (field (name "MANUFACTURER") "CJ(江苏长电/长晶)")
        (field (name "SUPPLIER PART") "C2128")
        (field (name "SUPPLIER") "LCSC")
        (field (name "LCSC PART NAME") "丝印T4")
      )
      (libsource (lib "easyedapro") (part "1N4148WS T4"))
    )
    (comp (ref "D105")
      (value "1N4148WS")
      (footprint "ProPrj_HTX-easyedapro:SOD-323_L1.8-W1.3-LS2.5-RD")
      (fields
        (field (name "MANUFACTURER PART") "1N4148WS")
        (field (name "MANUFACTURER") "CJ(江苏长电/长晶)")
        (field (name "SUPPLIER PART") "C2128")
        (field (name "SUPPLIER") "LCSC")
        (field (name "LCSC PART NAME") "丝印T4")
      )
      (libsource (lib "easyedapro") (part "1N4148WS T4"))
    )
    (comp (ref "D106")
      (value "1N4148WS")
      (footprint "ProPrj_HTX-easyedapro:SOD-323_L1.8-W1.3-LS2.5-RD")
      (fields
        (field (name "MANUFACTURER PART") "1N4148WS")
        (field (name "MANUFACTURER") "CJ(江苏长电/长晶)")
        (field (name "SUPPLIER PART") "C2128")
        (field (name "SUPPLIER") "LCSC")
        (field (name "LCSC PART NAME") "丝印T4")
      )
      (libsource (lib "easyedapro") (part "1N4148WS T4"))
    )
    (comp (ref "D107")
      (value "1N4148WS")
      (footprint "ProPrj_HTX-easyedapro:SOD-323_L1.8-W1.3-LS2.5-RD")
      (fields
        (field (name "MANUFACTURER PART") "1N4148WS")
        (field (name "MANUFACTURER") "CJ(江苏长电/长晶)")
        (field (name "SUPPLIER PART") "C2128")
        (field (name "SUPPLIER") "LCSC")
        (field (name "LCSC PART NAME") "丝印T4")
      )
      (libsource (lib "easyedapro") (part "1N4148WS T4"))
    )
    (comp (ref "D108")
      (value "1N4148WS")
      (footprint "ProPrj_HTX-easyedapro:SOD-323_L1.8-W1.3-LS2.5-RD")
      (fields
        (field (name "MANUFACTURER PART") "1N4148WS")
        (field (name "MANUFACTURER") "CJ(江苏长电/长晶)")
        (field (name "SUPPLIER PART") "C2128")
        (field (name "SUPPLIER") "LCSC")
        (field (name "LCSC PART NAME") "丝印T4")
      )
      (libsource (lib "easyedapro") (part "1N4148WS T4"))
    )
    (comp (ref "D109")
      (value "1N4148WS")
      (footprint "ProPrj_HTX-easyedapro:SOD-323_L1.8-W1.3-LS2.5-RD")
      (fields
        (field (name "MANUFACTURER PART") "1N4148WS")
        (field (name "MANUFACTURER") "CJ(江苏长电/长晶)")
        (field (name "SUPPLIER PART") "C2128")
        (field (name "SUPPLIER") "LCSC")
        (field (name "LCSC PART NAME") "丝印T4")
      )
      (libsource (lib "easyedapro") (part "1N4148WS T4"))
    )
    (comp (ref "D110")
      (value "1N4148WS")
      (footprint "ProPrj_HTX-easyedapro:SOD-323_L1.8-W1.3-LS2.5-RD")
      (fields
        (field (name "MANUFACTURER PART") "1N4148WS")
        (field (name "MANUFACTURER") "CJ(江苏长电/长晶)")
        (field (name "SUPPLIER PART") "C2128")
        (field (name "SUPPLIER") "LCSC")
        (field (name "LCSC PART NAME") "丝印T4")
      )
      (libsource (lib "easyedapro") (part "1N4148WS T4"))
    )
    (comp (ref "D111")
      (value "1N4148WS")
      (footprint "ProPrj_HTX-easyedapro:SOD-323_L1.8-W1.3-LS2.5-RD")
      (fields
        (field (name "MANUFACTURER PART") "1N4148WS")
        (field (name "MANUFACTURER") "CJ(江苏长电/长晶)")
        (field (name "SUPPLIER PART") "C2128")
        (field (name "SUPPLIER") "LCSC")
        (field (name "LCSC PART NAME") "丝印T4")
      )
      (libsource (lib "easyedapro") (part "1N4148WS T4"))
    )
    (comp (ref "D112")
      (value "1N4148WS")
      (footprint "ProPrj_HTX-easyedapro:SOD-323_L1.8-W1.3-LS2.5-RD")
      (fields
        (field (name "MANUFACTURER PART") "1N4148WS")
        (field (name "MANUFACTURER") "CJ(江苏长电/长晶)")
        (field (name "SUPPLIER PART") "C2128")
        (field (name "SUPPLIER") "LCSC")
        (field (name "LCSC PART NAME") "丝印T4")
      )
      (libsource (lib "easyedapro") (part "1N4148WS T4"))
    )
    (comp (ref "D113")
      (value "1N4148WS")
      (footprint "ProPrj_HTX-easyedapro:SOD-323_L1.8-W1.3-LS2.5-RD")
      (fields
        (field (name "MANUFACTURER PART") "1N4148WS")
        (field (name "MANUFACTURER") "CJ(江苏长电/长晶)")
        (field (name "SUPPLIER PART") "C2128")
        (field (name "SUPPLIER") "LCSC")
        (field (name "LCSC PART NAME") "丝印T4")
      )
      (libsource (lib "easyedapro") (part "1N4148WS T4"))
    )
    (comp (ref "D114")
      (value "1N4148WS")
      (footprint "ProPrj_HTX-easyedapro:SOD-323_L1.8-W1.3-LS2.5-RD")
      (fields
        (field (name "MANUFACTURER PART") "1N4148WS")
        (field (name "MANUFACTURER") "CJ(江苏长电/长晶)")
        (field (name "SUPPLIER PART") "C2128")
        (field (name "SUPPLIER") "LCSC")
        (field (name "LCSC PART NAME") "丝印T4")
      )
      (libsource (lib "easyedapro") (part "1N4148WS T4"))
    )
    (comp (ref "D115")
      (value "1N4148WS")
      (footprint "ProPrj_HTX-easyedapro:SOD-323_L1.8-W1.3-LS2.5-RD")
      (fields
        (field (name "MANUFACTURER PART") "1N4148WS")
        (field (name "MANUFACTURER") "CJ(江苏长电/长晶)")
        (field (name "SUPPLIER PART") "C2128")
        (field (name "SUPPLIER") "LCSC")
        (field (name "LCSC PART NAME") "丝印T4")
      )
      (libsource (lib "easyedapro") (part "1N4148WS T4"))
    )
    (comp (ref "D116")
      (value "1N4148WS")
      (footprint "ProPrj_HTX-easyedapro:SOD-323_L1.8-W1.3-LS2.5-RD")
      (fields
        (field (name "MANUFACTURER PART") "1N4148WS")
        (field (name "MANUFACTURER") "CJ(江苏长电/长晶)")
        (field (name "SUPPLIER PART") "C2128")
        (field (name "SUPPLIER") "LCSC")
        (field (name "LCSC PART NAME") "丝印T4")
      )
      (libsource (lib "easyedapro") (part "1N4148WS T4"))
    )
    (comp (ref "D117")
      (value "1N4148WS")
      (footprint "ProPrj_HTX-easyedapro:SOD-323_L1.8-W1.3-LS2.5-RD")
      (fields
        (field (name "MANUFACTURER PART") "1N4148WS")
        (field (name "MANUFACTURER") "CJ(江苏长电/长晶)")
        (field (name "SUPPLIER PART") "C2128")
        (field (name "SUPPLIER") "LCSC")
        (field (name "LCSC PART NAME") "丝印T4")
      )
      (libsource (lib "easyedapro") (part "1N4148WS T4"))
    )
    (comp (ref "D118")
      (value "1N4148WS")
      (footprint "ProPrj_HTX-easyedapro:SOD-323_L1.8-W1.3-LS2.5-RD")
      (fields
        (field (name "MANUFACTURER PART") "1N4148WS")
        (field (name "MANUFACTURER") "CJ(江苏长电/长晶)")
        (field (name "SUPPLIER PART") "C2128")
        (field (name "SUPPLIER") "LCSC")
        (field (name "LCSC PART NAME") "丝印T4")
      )
      (libsource (lib "easyedapro") (part "1N4148WS T4"))
    )
    (comp (ref "D119")
      (value "1N4148WS")
      (footprint "ProPrj_HTX-easyedapro:SOD-323_L1.8-W1.3-LS2.5-RD")
      (fields
        (field (name "MANUFACTURER PART") "1N4148WS")
        (field (name "MANUFACTURER") "CJ(江苏长电/长晶)")
        (field (name "SUPPLIER PART") "C2128")
        (field (name "SUPPLIER") "LCSC")
        (field (name "LCSC PART NAME") "丝印T4")
      )
      (libsource (lib "easyedapro") (part "1N4148WS T4"))
    )
    (comp (ref "D120")
      (value "1N4148WS")
      (footprint "ProPrj_HTX-easyedapro:SOD-323_L1.8-W1.3-LS2.5-RD")
      (fields
        (field (name "MANUFACTURER PART") "1N4148WS")
        (field (name "MANUFACTURER") "CJ(江苏长电/长晶)")
        (field (name "SUPPLIER PART") "C2128")
        (field (name "SUPPLIER") "LCSC")
        (field (name "LCSC PART NAME") "丝印T4")
      )
      (libsource (lib "easyedapro") (part "1N4148WS T4"))
    )
    (comp (ref "D121")
      (value "1N4148WS")
      (footprint "ProPrj_HTX-easyedapro:SOD-323_L1.8-W1.3-LS2.5-RD")
      (fields
        (field (name "MANUFACTURER PART") "1N4148WS")
        (field (name "MANUFACTURER") "CJ(江苏长电/长晶)")
        (field (name "SUPPLIER PART") "C2128")
        (field (name "SUPPLIER") "LCSC")
        (field (name "LCSC PART NAME") "丝印T4")
      )
      (libsource (lib "easyedapro") (part "1N4148WS T4"))
    )
    (comp (ref "D122")
      (value "1N4148WS")
      (footprint "ProPrj_HTX-easyedapro:SOD-323_L1.8-W1.3-LS2.5-RD")
      (fields
        (field (name "MANUFACTURER PART") "1N4148WS")
        (field (name "MANUFACTURER") "CJ(江苏长电/长晶)")
        (field (name "SUPPLIER PART") "C2128")
        (field (name "SUPPLIER") "LCSC")
        (field (name "LCSC PART NAME") "丝印T4")
      )
      (libsource (lib "easyedapro") (part "1N4148WS T4"))
    )
    (comp (ref "D123")
      (value "1N4148WS")
      (footprint "ProPrj_HTX-easyedapro:SOD-323_L1.8-W1.3-LS2.5-RD")
      (fields
        (field (name "MANUFACTURER PART") "1N4148WS")
        (field (name "MANUFACTURER") "CJ(江苏长电/长晶)")
        (field (name "SUPPLIER PART") "C2128")
        (field (name "SUPPLIER") "LCSC")
        (field (name "LCSC PART NAME") "丝印T4")
      )
      (libsource (lib "easyedapro") (part "1N4148WS T4"))
    )
    (comp (ref "D124")
      (value "1N4148WS")
      (footprint "ProPrj_HTX-easyedapro:SOD-323_L1.8-W1.3-LS2.5-RD")
      (fields
        (field (name "MANUFACTURER PART") "1N4148WS")
        (field (name "MANUFACTURER") "CJ(江苏长电/长晶)")
        (field (name "SUPPLIER PART") "C2128")
        (field (name "SUPPLIER") "LCSC")
        (field (name "LCSC PART NAME") "丝印T4")
      )
      (libsource (lib "easyedapro") (part "1N4148WS T4"))
    )
    (comp (ref "D125")
      (value "1N4148WS")
      (footprint "ProPrj_HTX-easyedapro:SOD-323_L1.8-W1.3-LS2.5-RD")
      (fields
        (field (name "MANUFACTURER PART") "1N4148WS")
        (field (name "MANUFACTURER") "CJ(江苏长电/长晶)")
        (field (name "SUPPLIER PART") "C2128")
        (field (name "SUPPLIER") "LCSC")
        (field (name "LCSC PART NAME") "丝印T4")
      )
      (libsource (lib "easyedapro") (part "1N4148WS T4"))
    )
    (comp (ref "D126")
      (value "1N4148WS")
      (footprint "ProPrj_HTX-easyedapro:SOD-323_L1.8-W1.3-LS2.5-RD")
      (fields
        (field (name "MANUFACTURER PART") "1N4148WS")
        (field (name "MANUFACTURER") "CJ(江苏长电/长晶)")
        (field (name "SUPPLIER PART") "C2128")
        (field (name "SUPPLIER") "LCSC")
        (field (name "LCSC PART NAME") "丝印T4")
      )
      (libsource (lib "easyedapro") (part "1N4148WS T4"))
    )
    (comp (ref "D127")
      (value "1N4148WS")
      (footprint "ProPrj_HTX-easyedapro:SOD-323_L1.8-W1.3-LS2.5-RD")
      (fields
        (field (name "MANUFACTURER PART") "1N4148WS")
        (field (name "MANUFACTURER") "CJ(江苏长电/长晶)")
        (field (name "SUPPLIER PART") "C2128")
        (field (name "SUPPLIER") "LCSC")
        (field (name "LCSC PART NAME") "丝印T4")
      )
      (libsource (lib "easyedapro") (part "1N4148WS T4"))
    )
    (comp (ref "D128")
      (value "1N4148WS")
      (footprint "ProPrj_HTX-easyedapro:SOD-323_L1.8-W1.3-LS2.5-RD")
      (fields
        (field (name "MANUFACTURER PART") "1N4148WS")
        (field (name "MANUFACTURER") "CJ(江苏长电/长晶)")
        (field (name "SUPPLIER PART") "C2128")
        (field (name "SUPPLIER") "LCSC")
        (field (name "LCSC PART NAME") "丝印T4")
      )
      (libsource (lib "easyedapro") (part "1N4148WS T4"))
    )
    (comp (ref "D129")
      (value "1N4148WS")
      (footprint "ProPrj_HTX-easyedapro:SOD-323_L1.8-W1.3-LS2.5-RD")
      (fields
        (field (name "MANUFACTURER PART") "1N4148WS")
        (field (name "MANUFACTURER") "CJ(江苏长电/长晶)")
        (field (name "SUPPLIER PART") "C2128")
        (field (name "SUPPLIER") "LCSC")
        (field (name "LCSC PART NAME") "丝印T4")
      )
      (libsource (lib "easyedapro") (part "1N4148WS T4"))
    )
    (comp (ref "D130")
      (value "1N4148WS")
      (footprint "ProPrj_HTX-easyedapro:SOD-323_L1.8-W1.3-LS2.5-RD")
      (fields
        (field (name "MANUFACTURER PART") "1N4148WS")
        (field (name "MANUFACTURER") "CJ(江苏长电/长晶)")
        (field (name "SUPPLIER PART") "C2128")
        (field (name "SUPPLIER") "LCSC")
        (field (name "LCSC PART NAME") "丝印T4")
      )
      (libsource (lib "easyedapro") (part "1N4148WS T4"))
    )
    (comp (ref "D131")
      (value "1N4148WS")
      (footprint "ProPrj_HTX-easyedapro:SOD-323_L1.8-W1.3-LS2.5-RD")
      (fields
        (field (name "MANUFACTURER PART") "1N4148WS")
        (field (name "MANUFACTURER") "CJ(江苏长电/长晶)")
        (field (name "SUPPLIER PART") "C2128")
        (field (name "SUPPLIER") "LCSC")
        (field (name "LCSC PART NAME") "丝印T4")
      )
      (libsource (lib "easyedapro") (part "1N4148WS T4"))
    )
    (comp (ref "D132")
      (value "1N4148WS")
      (footprint "ProPrj_HTX-easyedapro:SOD-323_L1.8-W1.3-LS2.5-RD")
      (fields
        (field (name "MANUFACTURER PART") "1N4148WS")
        (field (name "MANUFACTURER") "CJ(江苏长电/长晶)")
        (field (name "SUPPLIER PART") "C2128")
        (field (name "SUPPLIER") "LCSC")
        (field (name "LCSC PART NAME") "丝印T4")
      )
      (libsource (lib "easyedapro") (part "1N4148WS T4"))
    )
    (comp (ref "D133")
      (value "1N4148WS")
      (footprint "ProPrj_HTX-easyedapro:SOD-323_L1.8-W1.3-LS2.5-RD")
      (fields
        (field (name "MANUFACTURER PART") "1N4148WS")
        (field (name "MANUFACTURER") "CJ(江苏长电/长晶)")
        (field (name "SUPPLIER PART") "C2128")
        (field (name "SUPPLIER") "LCSC")
        (field (name "LCSC PART NAME") "丝印T4")
      )
      (libsource (lib "easyedapro") (part "1N4148WS T4"))
    )
    (comp (ref "D134")
      (value "1N4148WS")
      (footprint "ProPrj_HTX-easyedapro:SOD-323_L1.8-W1.3-LS2.5-RD")
      (fields
        (field (name "MANUFACTURER PART") "1N4148WS")
        (field (name "MANUFACTURER") "CJ(江苏长电/长晶)")
        (field (name "SUPPLIER PART") "C2128")
        (field (name "SUPPLIER") "LCSC")
        (field (name "LCSC PART NAME") "丝印T4")
      )
      (libsource (lib "easyedapro") (part "1N4148WS T4"))
    )
    (comp (ref "D135")
      (value "1N4148WS")
      (footprint "ProPrj_HTX-easyedapro:SOD-323_L1.8-W1.3-LS2.5-RD")
      (fields
        (field (name "MANUFACTURER PART") "1N4148WS")
        (field (name "MANUFACTURER") "CJ(江苏长电/长晶)")
        (field (name "SUPPLIER PART") "C2128")
        (field (name "SUPPLIER") "LCSC")
        (field (name "LCSC PART NAME") "丝印T4")
      )
      (libsource (lib "easyedapro") (part "1N4148WS T4"))
    )
    (comp (ref "D136")
      (value "1N4148WS")
      (footprint "ProPrj_HTX-easyedapro:SOD-323_L1.8-W1.3-LS2.5-RD")
      (fields
        (field (name "MANUFACTURER PART") "1N4148WS")
        (field (name "MANUFACTURER") "CJ(江苏长电/长晶)")
        (field (name "SUPPLIER PART") "C2128")
        (field (name "SUPPLIER") "LCSC")
        (field (name "LCSC PART NAME") "丝印T4")
      )
      (libsource (lib "easyedapro") (part "1N4148WS T4"))
    )
    (comp (ref "D137")
      (value "1N4148WS")
      (footprint "ProPrj_HTX-easyedapro:SOD-323_L1.8-W1.3-LS2.5-RD")
      (fields
        (field (name "MANUFACTURER PART") "1N4148WS")
        (field (name "MANUFACTURER") "CJ(江苏长电/长晶)")
        (field (name "SUPPLIER PART") "C2128")
        (field (name "SUPPLIER") "LCSC")
        (field (name "LCSC PART NAME") "丝印T4")
      )
      (libsource (lib "easyedapro") (part "1N4148WS T4"))
    )
    (comp (ref "D138")
      (value "1N4148WS")
      (footprint "ProPrj_HTX-easyedapro:SOD-323_L1.8-W1.3-LS2.5-RD")
      (fields
        (field (name "MANUFACTURER PART") "1N4148WS")
        (field (name "MANUFACTURER") "CJ(江苏长电/长晶)")
        (field (name "SUPPLIER PART") "C2128")
        (field (name "SUPPLIER") "LCSC")
        (field (name "LCSC PART NAME") "丝印T4")
      )
      (libsource (lib "easyedapro") (part "1N4148WS T4"))
    )
    (comp (ref "D139")
      (value "1N4148WS")
      (footprint "ProPrj_HTX-easyedapro:SOD-323_L1.8-W1.3-LS2.5-RD")
      (fields
        (field (name "MANUFACTURER PART") "1N4148WS")
        (field (name "MANUFACTURER") "CJ(江苏长电/长晶)")
        (field (name "SUPPLIER PART") "C2128")
        (field (name "SUPPLIER") "LCSC")
        (field (name "LCSC PART NAME") "丝印T4")
      )
      (libsource (lib "easyedapro") (part "1N4148WS T4"))
    )
    (comp (ref "D140")
      (value "1N4148WS")
      (footprint "ProPrj_HTX-easyedapro:SOD-323_L1.8-W1.3-LS2.5-RD")
      (fields
        (field (name "MANUFACTURER PART") "1N4148WS")
        (field (name "MANUFACTURER") "MDD(辰达半导体)")
        (field (name "SUPPLIER PART") "C437156")
        (field (name "SUPPLIER") "LCSC")
        (field (name "LCSC PART NAME") "电压:100V 电流:150mA")
      )
      (libsource (lib "easyedapro") (part "1N4148WS_C437156"))
    )
    (comp (ref "D141")
      (value "1N4148WS")
      (footprint "ProPrj_HTX-easyedapro:SOD-323_L1.8-W1.3-LS2.5-RD")
      (fields
        (field (name "MANUFACTURER PART") "1N4148WS")
        (field (name "MANUFACTURER") "MDD(辰达半导体)")
        (field (name "SUPPLIER PART") "C437156")
        (field (name "SUPPLIER") "LCSC")
        (field (name "LCSC PART NAME") "电压:100V 电流:150mA")
      )
      (libsource (lib "easyedapro") (part "1N4148WS_C437156"))
    )
    (comp (ref "D142")
      (value "1N4148WS")
      (footprint "ProPrj_HTX-easyedapro:SOD-323_L1.8-W1.3-LS2.5-RD")
      (fields
        (field (name "MANUFACTURER PART") "1N4148WS")
        (field (name "MANUFACTURER") "CJ(江苏长电/长晶)")
        (field (name "SUPPLIER PART") "C2128")
        (field (name "SUPPLIER") "LCSC")
        (field (name "LCSC PART NAME") "丝印T4")
      )
      (libsource (lib "easyedapro") (part "1N4148WS T4"))
    )
    (comp (ref "D143")
      (value "1N4148WS")
      (footprint "ProPrj_HTX-easyedapro:SOD-323_L1.8-W1.3-LS2.5-RD")
      (fields
        (field (name "MANUFACTURER PART") "1N4148WS")
        (field (name "MANUFACTURER") "CJ(江苏长电/长晶)")
        (field (name "SUPPLIER PART") "C2128")
        (field (name "SUPPLIER") "LCSC")
        (field (name "LCSC PART NAME") "丝印T4")
      )
      (libsource (lib "easyedapro") (part "1N4148WS T4"))
    )
    (comp (ref "D144")
      (value "1N4148WS")
      (footprint "ProPrj_HTX-easyedapro:SOD-323_L1.8-W1.3-LS2.5-RD")
      (fields
        (field (name "MANUFACTURER PART") "1N4148WS")
        (field (name "MANUFACTURER") "CJ(江苏长电/长晶)")
        (field (name "SUPPLIER PART") "C2128")
        (field (name "SUPPLIER") "LCSC")
        (field (name "LCSC PART NAME") "丝印T4")
      )
      (libsource (lib "easyedapro") (part "1N4148WS T4"))
    )
    (comp (ref "D145")
      (value "1N4148WS")
      (footprint "ProPrj_HTX-easyedapro:SOD-323_L1.8-W1.3-LS2.5-RD")
      (fields
        (field (name "MANUFACTURER PART") "1N4148WS")
        (field (name "MANUFACTURER") "CJ(江苏长电/长晶)")
        (field (name "SUPPLIER PART") "C2128")
        (field (name "SUPPLIER") "LCSC")
        (field (name "LCSC PART NAME") "丝印T4")
      )
      (libsource (lib "easyedapro") (part "1N4148WS T4"))
    )
    (comp (ref "D146")
      (value "1N4148WS")
      (footprint "ProPrj_HTX-easyedapro:SOD-323_L1.8-W1.3-LS2.5-RD")
      (fields
        (field (name "MANUFACTURER PART") "1N4148WS")
        (field (name "MANUFACTURER") "CJ(江苏长电/长晶)")
        (field (name "SUPPLIER PART") "C2128")
        (field (name "SUPPLIER") "LCSC")
        (field (name "LCSC PART NAME") "丝印T4")
      )
      (libsource (lib "easyedapro") (part "1N4148WS T4"))
    )
    (comp (ref "D147")
      (value "1N4148WS")
      (footprint "ProPrj_HTX-easyedapro:SOD-323_L1.8-W1.3-LS2.5-RD")
      (fields
        (field (name "MANUFACTURER PART") "1N4148WS")
        (field (name "MANUFACTURER") "CJ(江苏长电/长晶)")
        (field (name "SUPPLIER PART") "C2128")
        (field (name "SUPPLIER") "LCSC")
        (field (name "LCSC PART NAME") "丝印T4")
      )
      (libsource (lib "easyedapro") (part "1N4148WS T4"))
    )
    (comp (ref "D148")
      (value "1N4148WS")
      (footprint "ProPrj_HTX-easyedapro:SOD-323_L1.8-W1.3-LS2.5-RD")
      (fields
        (field (name "MANUFACTURER PART") "1N4148WS")
        (field (name "MANUFACTURER") "CJ(江苏长电/长晶)")
        (field (name "SUPPLIER PART") "C2128")
        (field (name "SUPPLIER") "LCSC")
        (field (name "LCSC PART NAME") "丝印T4")
      )
      (libsource (lib "easyedapro") (part "1N4148WS T4"))
    )
    (comp (ref "D149")
      (value "1N4148WS")
      (footprint "ProPrj_HTX-easyedapro:SOD-323_L1.8-W1.3-LS2.5-RD")
      (fields
        (field (name "MANUFACTURER PART") "1N4148WS")
        (field (name "MANUFACTURER") "CJ(江苏长电/长晶)")
        (field (name "SUPPLIER PART") "C2128")
        (field (name "SUPPLIER") "LCSC")
        (field (name "LCSC PART NAME") "丝印T4")
      )
      (libsource (lib "easyedapro") (part "1N4148WS T4"))
    )
    (comp (ref "D150")
      (value "1N4148WS")
      (footprint "ProPrj_HTX-easyedapro:SOD-323_L1.8-W1.3-LS2.5-RD")
      (fields
        (field (name "MANUFACTURER PART") "1N4148WS")
        (field (name "MANUFACTURER") "CJ(江苏长电/长晶)")
        (field (name "SUPPLIER PART") "C2128")
        (field (name "SUPPLIER") "LCSC")
        (field (name "LCSC PART NAME") "丝印T4")
      )
      (libsource (lib "easyedapro") (part "1N4148WS T4"))
    )
    (comp (ref "D151")
      (value "1N4148WS")
      (footprint "ProPrj_HTX-easyedapro:SOD-323_L1.8-W1.3-LS2.5-RD")
      (fields
        (field (name "MANUFACTURER PART") "1N4148WS")
        (field (name "MANUFACTURER") "CJ(江苏长电/长晶)")
        (field (name "SUPPLIER PART") "C2128")
        (field (name "SUPPLIER") "LCSC")
        (field (name "LCSC PART NAME") "丝印T4")
      )
      (libsource (lib "easyedapro") (part "1N4148WS T4"))
    )
    (comp (ref "D152")
      (value "1N4148WS")
      (footprint "ProPrj_HTX-easyedapro:SOD-323_L1.8-W1.3-LS2.5-RD")
      (fields
        (field (name "MANUFACTURER PART") "1N4148WS")
        (field (name "MANUFACTURER") "CJ(江苏长电/长晶)")
        (field (name "SUPPLIER PART") "C2128")
        (field (name "SUPPLIER") "LCSC")
        (field (name "LCSC PART NAME") "丝印T4")
      )
      (libsource (lib "easyedapro") (part "1N4148WS T4"))
    )
    (comp (ref "D153")
      (value "1N4148WS")
      (footprint "ProPrj_HTX-easyedapro:SOD-323_L1.8-W1.3-LS2.5-RD")
      (fields
        (field (name "MANUFACTURER PART") "1N4148WS")
        (field (name "MANUFACTURER") "CJ(江苏长电/长晶)")
        (field (name "SUPPLIER PART") "C2128")
        (field (name "SUPPLIER") "LCSC")
        (field (name "LCSC PART NAME") "丝印T4")
      )
      (libsource (lib "easyedapro") (part "1N4148WS T4"))
    )
    (comp (ref "D154")
      (value "1N4148WS")
      (footprint "ProPrj_HTX-easyedapro:SOD-323_L1.8-W1.3-LS2.5-RD")
      (fields
        (field (name "MANUFACTURER PART") "1N4148WS")
        (field (name "MANUFACTURER") "CJ(江苏长电/长晶)")
        (field (name "SUPPLIER PART") "C2128")
        (field (name "SUPPLIER") "LCSC")
        (field (name "LCSC PART NAME") "丝印T4")
      )
      (libsource (lib "easyedapro") (part "1N4148WS T4"))
    )
    (comp (ref "D155")
      (value "1N4148WS")
      (footprint "ProPrj_HTX-easyedapro:SOD-323_L1.8-W1.3-LS2.5-RD")
      (fields
        (field (name "MANUFACTURER PART") "1N4148WS")
        (field (name "MANUFACTURER") "CJ(江苏长电/长晶)")
        (field (name "SUPPLIER PART") "C2128")
        (field (name "SUPPLIER") "LCSC")
        (field (name "LCSC PART NAME") "丝印T4")
      )
      (libsource (lib "easyedapro") (part "1N4148WS T4"))
    )
    (comp (ref "D156")
      (value "1N4148WS")
      (footprint "ProPrj_HTX-easyedapro:SOD-323_L1.8-W1.3-LS2.5-RD")
      (fields
        (field (name "MANUFACTURER PART") "1N4148WS")
        (field (name "MANUFACTURER") "CJ(江苏长电/长晶)")
        (field (name "SUPPLIER PART") "C2128")
        (field (name "SUPPLIER") "LCSC")
        (field (name "LCSC PART NAME") "丝印T4")
      )
      (libsource (lib "easyedapro") (part "1N4148WS T4"))
    )
    (comp (ref "D157")
      (value "1N4148WS")
      (footprint "ProPrj_HTX-easyedapro:SOD-323_L1.8-W1.3-LS2.5-RD")
      (fields
        (field (name "MANUFACTURER PART") "1N4148WS")
        (field (name "MANUFACTURER") "CJ(江苏长电/长晶)")
        (field (name "SUPPLIER PART") "C2128")
        (field (name "SUPPLIER") "LCSC")
        (field (name "LCSC PART NAME") "丝印T4")
      )
      (libsource (lib "easyedapro") (part "1N4148WS T4"))
    )
    (comp (ref "D158")
      (value "1N4148WS")
      (footprint "ProPrj_HTX-easyedapro:SOD-323_L1.8-W1.3-LS2.5-RD")
      (fields
        (field (name "MANUFACTURER PART") "1N4148WS")
        (field (name "MANUFACTURER") "CJ(江苏长电/长晶)")
        (field (name "SUPPLIER PART") "C2128")
        (field (name "SUPPLIER") "LCSC")
        (field (name "LCSC PART NAME") "丝印T4")
      )
      (libsource (lib "easyedapro") (part "1N4148WS T4"))
    )
    (comp (ref "SW100")
      (value "K9-1267T")
      (footprint "ProPrj_HTX-easyedapro:SW-TH_K9-1267T")
      (fields
        (field (name "MANUFACTURER PART") "K9-1267T")
        (field (name "MANUFACTURER") "韩国韩荣")
        (field (name "SUPPLIER PART") "C107266")
        (field (name "SUPPLIER") "LCSC")
        (field (name "LCSC PART NAME") "12.7*5.7*7.5mm 插件微动开关")
      )
      (libsource (lib "easyedapro") (part "K9-1267T"))
    )
    (comp (ref "SW101")
      (value "K9-1267T")
      (footprint "ProPrj_HTX-easyedapro:SW-TH_K9-1267T")
      (fields
        (field (name "MANUFACTURER PART") "K9-1267T")
        (field (name "MANUFACTURER") "韩国韩荣")
        (field (name "SUPPLIER PART") "C107266")
        (field (name "SUPPLIER") "LCSC")
        (field (name "LCSC PART NAME") "12.7*5.7*7.5mm 插件微动开关")
      )
      (libsource (lib "easyedapro") (part "K9-1267T"))
    )
    (comp (ref "U100")
      (value "Yo-WS2812B-3528反贴雾状")
      (footprint "ProPrj_HTX-easyedapro:LED-SMD_L3.2-W2.8_YO-WS2812B-3528")
      (fields
        (field (name "MANUFACTURER PART") "Yo-WS2812B-3528反贴雾状")
        (field (name "SUPPLIER PART") "C9900003682")
        (field (name "SUPPLIER") "LCSC")
        (field (name "LCSC PART NAME") "Yo-WS2812B-3528反贴雾状")
      )
      (libsource (lib "easyedapro") (part "YO-WS2812B-3528_C9900003682"))
    )
    (comp (ref "U101")
      (value "Yo-WS2812B-3528反贴雾状")
      (footprint "ProPrj_HTX-easyedapro:LED-SMD_L3.2-W2.8_YO-WS2812B-3528")
      (fields
        (field (name "MANUFACTURER PART") "Yo-WS2812B-3528反贴雾状")
        (field (name "SUPPLIER PART") "C9900003682")
        (field (name "SUPPLIER") "LCSC")
        (field (name "LCSC PART NAME") "Yo-WS2812B-3528反贴雾状")
      )
      (libsource (lib "easyedapro") (part "YO-WS2812B-3528_C9900003682"))
    )
    (comp (ref "U102")
      (value "Yo-WS2812B-3528反贴雾状")
      (footprint "ProPrj_HTX-easyedapro:LED-SMD_L3.2-W2.8_YO-WS2812B-3528")
      (fields
        (field (name "MANUFACTURER PART") "Yo-WS2812B-3528反贴雾状")
        (field (name "SUPPLIER PART") "C9900003682")
        (field (name "SUPPLIER") "LCSC")
        (field (name "LCSC PART NAME") "Yo-WS2812B-3528反贴雾状")
      )
      (libsource (lib "easyedapro") (part "YO-WS2812B-3528_C9900003682"))
    )
    (comp (ref "U103")
      (value "Yo-WS2812B-3528反贴雾状")
      (footprint "ProPrj_HTX-easyedapro:LED-SMD_L3.2-W2.8_YO-WS2812B-3528")
      (fields
        (field (name "MANUFACTURER PART") "Yo-WS2812B-3528反贴雾状")
        (field (name "SUPPLIER PART") "C9900003682")
        (field (name "SUPPLIER") "LCSC")
        (field (name "LCSC PART NAME") "Yo-WS2812B-3528反贴雾状")
      )
      (libsource (lib "easyedapro") (part "YO-WS2812B-3528_C9900003682"))
    )
    (comp (ref "U104")
      (value "Yo-WS2812B-3528反贴雾状")
      (footprint "ProPrj_HTX-easyedapro:LED-SMD_L3.2-W2.8_YO-WS2812B-3528")
      (fields
        (field (name "MANUFACTURER PART") "Yo-WS2812B-3528反贴雾状")
        (field (name "SUPPLIER PART") "C9900003682")
        (field (name "SUPPLIER") "LCSC")
        (field (name "LCSC PART NAME") "Yo-WS2812B-3528反贴雾状")
      )
      (libsource (lib "easyedapro") (part "YO-WS2812B-3528_C9900003682"))
    )
    (comp (ref "U105")
      (value "Yo-WS2812B-3528反贴雾状")
      (footprint "ProPrj_HTX-easyedapro:LED-SMD_L3.2-W2.8_YO-WS2812B-3528")
      (fields
        (field (name "MANUFACTURER PART") "Yo-WS2812B-3528反贴雾状")
        (field (name "SUPPLIER PART") "C9900003682")
        (field (name "SUPPLIER") "LCSC")
        (field (name "LCSC PART NAME") "Yo-WS2812B-3528反贴雾状")
      )
      (libsource (lib "easyedapro") (part "YO-WS2812B-3528_C9900003682"))
    )
    (comp (ref "U106")
      (value "Yo-WS2812B-3528反贴雾状")
      (footprint "ProPrj_HTX-easyedapro:LED-SMD_L3.2-W2.8_YO-WS2812B-3528")
      (fields
        (field (name "MANUFACTURER PART") "Yo-WS2812B-3528反贴雾状")
        (field (name "SUPPLIER PART") "C9900003682")
        (field (name "SUPPLIER") "LCSC")
        (field (name "LCSC PART NAME") "Yo-WS2812B-3528反贴雾状")
      )
      (libsource (lib "easyedapro") (part "YO-WS2812B-3528_C9900003682"))
    )
    (comp (ref "U107")
      (value "Yo-WS2812B-3528反贴雾状")
      (footprint "ProPrj_HTX-easyedapro:LED-SMD_L3.2-W2.8_YO-WS2812B-3528")
      (fields
        (field (name "MANUFACTURER PART") "Yo-WS2812B-3528反贴雾状")
        (field (name "SUPPLIER PART") "C9900003682")
        (field (name "SUPPLIER") "LCSC")
        (field (name "LCSC PART NAME") "Yo-WS2812B-3528反贴雾状")
      )
      (libsource (lib "easyedapro") (part "YO-WS2812B-3528_C9900003682"))
    )
    (comp (ref "U108")
      (value "Yo-WS2812B-3528反贴雾状")
      (footprint "ProPrj_HTX-easyedapro:LED-SMD_L3.2-W2.8_YO-WS2812B-3528")
      (fields
        (field (name "MANUFACTURER PART") "Yo-WS2812B-3528反贴雾状")
        (field (name "SUPPLIER PART") "C9900003682")
        (field (name "SUPPLIER") "LCSC")
        (field (name "LCSC PART NAME") "Yo-WS2812B-3528反贴雾状")
      )
      (libsource (lib "easyedapro") (part "YO-WS2812B-3528_C9900003682"))
    )
    (comp (ref "U109")
      (value "Yo-WS2812B-3528反贴雾状")
      (footprint "ProPrj_HTX-easyedapro:LED-SMD_L3.2-W2.8_YO-WS2812B-3528")
      (fields
        (field (name "MANUFACTURER PART") "Yo-WS2812B-3528反贴雾状")
        (field (name "SUPPLIER PART") "C9900003682")
        (field (name "SUPPLIER") "LCSC")
        (field (name "LCSC PART NAME") "Yo-WS2812B-3528反贴雾状")
      )
      (libsource (lib "easyedapro") (part "YO-WS2812B-3528_C9900003682"))
    )
    (comp (ref "U110")
      (value "Yo-WS2812B-3528反贴雾状")
      (footprint "ProPrj_HTX-easyedapro:LED-SMD_L3.2-W2.8_YO-WS2812B-3528")
      (fields
        (field (name "MANUFACTURER PART") "Yo-WS2812B-3528反贴雾状")
        (field (name "SUPPLIER PART") "C9900003682")
        (field (name "SUPPLIER") "LCSC")
        (field (name "LCSC PART NAME") "Yo-WS2812B-3528反贴雾状")
      )
      (libsource (lib "easyedapro") (part "YO-WS2812B-3528_C9900003682"))
    )
    (comp (ref "U111")
      (value "Yo-WS2812B-3528反贴雾状")
      (footprint "ProPrj_HTX-easyedapro:LED-SMD_L3.2-W2.8_YO-WS2812B-3528")
      (fields
        (field (name "MANUFACTURER PART") "Yo-WS2812B-3528反贴雾状")
        (field (name "SUPPLIER PART") "C9900003682")
        (field (name "SUPPLIER") "LCSC")
        (field (name "LCSC PART NAME") "Yo-WS2812B-3528反贴雾状")
      )
      (libsource (lib "easyedapro") (part "YO-WS2812B-3528_C9900003682"))
    )
    (comp (ref "U112")
      (value "Yo-WS2812B-3528反贴雾状")
      (footprint "ProPrj_HTX-easyedapro:LED-SMD_L3.2-W2.8_YO-WS2812B-3528")
      (fields
        (field (name "MANUFACTURER PART") "Yo-WS2812B-3528反贴雾状")
        (field (name "SUPPLIER PART") "C9900003682")
        (field (name "SUPPLIER") "LCSC")
        (field (name "LCSC PART NAME") "Yo-WS2812B-3528反贴雾状")
      )
      (libsource (lib "easyedapro") (part "YO-WS2812B-3528_C9900003682"))
    )
    (comp (ref "U113")
      (value "Yo-WS2812B-3528反贴雾状")
      (footprint "ProPrj_HTX-easyedapro:LED-SMD_L3.2-W2.8_YO-WS2812B-3528")
      (fields
        (field (name "MANUFACTURER PART") "Yo-WS2812B-3528反贴雾状")
        (field (name "SUPPLIER PART") "C9900003682")
        (field (name "SUPPLIER") "LCSC")
        (field (name "LCSC PART NAME") "Yo-WS2812B-3528反贴雾状")
      )
      (libsource (lib "easyedapro") (part "YO-WS2812B-3528_C9900003682"))
    )
    (comp (ref "U114")
      (value "CPG151101S11-16")
      (footprint "ProPrj_HTX-easyedapro:SMD_KEYBOARD-SW")
      (fields
        (field (name "MANUFACTURER PART") "CPG151101S11-16")
        (field (name "MANUFACTURER") "HanElectricity(瀚源)")
        (field (name "SUPPLIER PART") "C41430893")
        (field (name "SUPPLIER") "LCSC")
        (field (name "LCSC PART NAME") "热插拔底座连接器 键盘配件")
      )
      (libsource (lib "easyedapro") (part "CPG151101S11-16_C41430893"))
    )
    (comp (ref "U115")
      (value "CPG151101S11-16")
      (footprint "ProPrj_HTX-easyedapro:SMD_KEYBOARD-SW")
      (fields
        (field (name "MANUFACTURER PART") "CPG151101S11-16")
        (field (name "MANUFACTURER") "HanElectricity(瀚源)")
        (field (name "SUPPLIER PART") "C41430893")
        (field (name "SUPPLIER") "LCSC")
        (field (name "LCSC PART NAME") "热插拔底座连接器 键盘配件")
      )
      (libsource (lib "easyedapro") (part "CPG151101S11-16_C41430893"))
    )
    (comp (ref "U116")
      (value "CPG151101S11-16")
      (footprint "ProPrj_HTX-easyedapro:SMD_KEYBOARD-SW")
      (fields
        (field (name "MANUFACTURER PART") "CPG151101S11-16")
        (field (name "MANUFACTURER") "HanElectricity(瀚源)")
        (field (name "SUPPLIER PART") "C41430893")
        (field (name "SUPPLIER") "LCSC")
        (field (name "LCSC PART NAME") "热插拔底座连接器 键盘配件")
      )
      (libsource (lib "easyedapro") (part "CPG151101S11-16_C41430893"))
    )
    (comp (ref "U117")
      (value "CPG151101S11-16")
      (footprint "ProPrj_HTX-easyedapro:SMD_KEYBOARD-SW")
      (fields
        (field (name "MANUFACTURER PART") "CPG151101S11-16")
        (field (name "MANUFACTURER") "HanElectricity(瀚源)")
        (field (name "SUPPLIER PART") "C41430893")
        (field (name "SUPPLIER") "LCSC")
        (field (name "LCSC PART NAME") "热插拔底座连接器 键盘配件")
      )
      (libsource (lib "easyedapro") (part "CPG151101S11-16_C41430893"))
    )
    (comp (ref "U118")
      (value "CPG151101S11-16")
      (footprint "ProPrj_HTX-easyedapro:SMD_KEYBOARD-SW")
      (fields
        (field (name "MANUFACTURER PART") "CPG151101S11-16")
        (field (name "MANUFACTURER") "HanElectricity(瀚源)")
        (field (name "SUPPLIER PART") "C41430893")
        (field (name "SUPPLIER") "LCSC")
        (field (name "LCSC PART NAME") "热插拔底座连接器 键盘配件")
      )
      (libsource (lib "easyedapro") (part "CPG151101S11-16_C41430893"))
    )
    (comp (ref "U119")
      (value "CPG151101S11-16")
      (footprint "ProPrj_HTX-easyedapro:SMD_KEYBOARD-SW")
      (fields
        (field (name "MANUFACTURER PART") "CPG151101S11-16")
        (field (name "MANUFACTURER") "HanElectricity(瀚源)")
        (field (name "SUPPLIER PART") "C41430893")
        (field (name "SUPPLIER") "LCSC")
        (field (name "LCSC PART NAME") "热插拔底座连接器 键盘配件")
      )
      (libsource (lib "easyedapro") (part "CPG151101S11-16_C41430893"))
    )
    (comp (ref "U120")
      (value "CPG151101S11-16")
      (footprint "ProPrj_HTX-easyedapro:SMD_KEYBOARD-SW")
      (fields
        (field (name "MANUFACTURER PART") "CPG151101S11-16")
        (field (name "MANUFACTURER") "HanElectricity(瀚源)")
        (field (name "SUPPLIER PART") "C41430893")
        (field (name "SUPPLIER") "LCSC")
        (field (name "LCSC PART NAME") "热插拔底座连接器 键盘配件")
      )
      (libsource (lib "easyedapro") (part "CPG151101S11-16_C41430893"))
    )
    (comp (ref "U121")
      (value "CPG151101S11-16")
      (footprint "ProPrj_HTX-easyedapro:SMD_KEYBOARD-SW")
      (fields
        (field (name "MANUFACTURER PART") "CPG151101S11-16")
        (field (name "MANUFACTURER") "HanElectricity(瀚源)")
        (field (name "SUPPLIER PART") "C41430893")
        (field (name "SUPPLIER") "LCSC")
        (field (name "LCSC PART NAME") "热插拔底座连接器 键盘配件")
      )
      (libsource (lib "easyedapro") (part "CPG151101S11-16_C41430893"))
    )
    (comp (ref "U122")
      (value "CPG151101S11-16")
      (footprint "ProPrj_HTX-easyedapro:SMD_KEYBOARD-SW")
      (fields
        (field (name "MANUFACTURER PART") "CPG151101S11-16")
        (field (name "MANUFACTURER") "HanElectricity(瀚源)")
        (field (name "SUPPLIER PART") "C41430893")
        (field (name "SUPPLIER") "LCSC")
        (field (name "LCSC PART NAME") "热插拔底座连接器 键盘配件")
      )
      (libsource (lib "easyedapro") (part "CPG151101S11-16_C41430893"))
    )
    (comp (ref "U123")
      (value "CPG151101S11-16")
      (footprint "ProPrj_HTX-easyedapro:SMD_KEYBOARD-SW")
      (fields
        (field (name "MANUFACTURER PART") "CPG151101S11-16")
        (field (name "MANUFACTURER") "HanElectricity(瀚源)")
        (field (name "SUPPLIER PART") "C41430893")
        (field (name "SUPPLIER") "LCSC")
        (field (name "LCSC PART NAME") "热插拔底座连接器 键盘配件")
      )
      (libsource (lib "easyedapro") (part "CPG151101S11-16_C41430893"))
    )
    (comp (ref "U124")
      (value "CPG151101S11-16")
      (footprint "ProPrj_HTX-easyedapro:SMD_KEYBOARD-SW")
      (fields
        (field (name "MANUFACTURER PART") "CPG151101S11-16")
        (field (name "MANUFACTURER") "HanElectricity(瀚源)")
        (field (name "SUPPLIER PART") "C41430893")
        (field (name "SUPPLIER") "LCSC")
        (field (name "LCSC PART NAME") "热插拔底座连接器 键盘配件")
      )
      (libsource (lib "easyedapro") (part "CPG151101S11-16_C41430893"))
    )
    (comp (ref "U125")
      (value "CPG151101S11-16")
      (footprint "ProPrj_HTX-easyedapro:SMD_KEYBOARD-SW")
      (fields
        (field (name "MANUFACTURER PART") "CPG151101S11-16")
        (field (name "MANUFACTURER") "HanElectricity(瀚源)")
        (field (name "SUPPLIER PART") "C41430893")
        (field (name "SUPPLIER") "LCSC")
        (field (name "LCSC PART NAME") "热插拔底座连接器 键盘配件")
      )
      (libsource (lib "easyedapro") (part "CPG151101S11-16_C41430893"))
    )
    (comp (ref "U126")
      (value "CPG151101S11-16")
      (footprint "ProPrj_HTX-easyedapro:SMD_KEYBOARD-SW")
      (fields
        (field (name "MANUFACTURER PART") "CPG151101S11-16")
        (field (name "MANUFACTURER") "HanElectricity(瀚源)")
        (field (name "SUPPLIER PART") "C41430893")
        (field (name "SUPPLIER") "LCSC")
        (field (name "LCSC PART NAME") "热插拔底座连接器 键盘配件")
      )
      (libsource (lib "easyedapro") (part "CPG151101S11-16_C41430893"))
    )
    (comp (ref "U127")
      (value "CPG151101S11-16")
      (footprint "ProPrj_HTX-easyedapro:SMD_KEYBOARD-SW")
      (fields
        (field (name "MANUFACTURER PART") "CPG151101S11-16")
        (field (name "MANUFACTURER") "HanElectricity(瀚源)")
        (field (name "SUPPLIER PART") "C41430893")
        (field (name "SUPPLIER") "LCSC")
        (field (name "LCSC PART NAME") "热插拔底座连接器 键盘配件")
      )
      (libsource (lib "easyedapro") (part "CPG151101S11-16_C41430893"))
    )
    (comp (ref "U128")
      (value "Yo-WS2812B-3528反贴雾状")
      (footprint "ProPrj_HTX-easyedapro:LED-SMD_L3.2-W2.8_YO-WS2812B-3528")
      (fields
        (field (name "MANUFACTURER PART") "Yo-WS2812B-3528反贴雾状")
        (field (name "SUPPLIER PART") "C9900003682")
        (field (name "SUPPLIER") "LCSC")
        (field (name "LCSC PART NAME") "Yo-WS2812B-3528反贴雾状")
      )
      (libsource (lib "easyedapro") (part "YO-WS2812B-3528_C9900003682"))
    )
    (comp (ref "U129")
      (value "Yo-WS2812B-3528反贴雾状")
      (footprint "ProPrj_HTX-easyedapro:LED-SMD_L3.2-W2.8_YO-WS2812B-3528")
      (fields
        (field (name "MANUFACTURER PART") "Yo-WS2812B-3528反贴雾状")
        (field (name "SUPPLIER PART") "C9900003682")
        (field (name "SUPPLIER") "LCSC")
        (field (name "LCSC PART NAME") "Yo-WS2812B-3528反贴雾状")
      )
      (libsource (lib "easyedapro") (part "YO-WS2812B-3528_C9900003682"))
    )
    (comp (ref "U130")
      (value "Yo-WS2812B-3528反贴雾状")
      (footprint "ProPrj_HTX-easyedapro:LED-SMD_L3.2-W2.8_YO-WS2812B-3528")
      (fields
        (field (name "MANUFACTURER PART") "Yo-WS2812B-3528反贴雾状")
        (field (name "SUPPLIER PART") "C9900003682")
        (field (name "SUPPLIER") "LCSC")
        (field (name "LCSC PART NAME") "Yo-WS2812B-3528反贴雾状")
      )
      (libsource (lib "easyedapro") (part "YO-WS2812B-3528_C9900003682"))
    )
    (comp (ref "U131")
      (value "Yo-WS2812B-3528反贴雾状")
      (footprint "ProPrj_HTX-easyedapro:LED-SMD_L3.2-W2.8_YO-WS2812B-3528")
      (fields
        (field (name "MANUFACTURER PART") "Yo-WS2812B-3528反贴雾状")
        (field (name "SUPPLIER PART") "C9900003682")
        (field (name "SUPPLIER") "LCSC")
        (field (name "LCSC PART NAME") "Yo-WS2812B-3528反贴雾状")
      )
      (libsource (lib "easyedapro") (part "YO-WS2812B-3528_C9900003682"))
    )
    (comp (ref "U132")
      (value "Yo-WS2812B-3528反贴雾状")
      (footprint "ProPrj_HTX-easyedapro:LED-SMD_L3.2-W2.8_YO-WS2812B-3528")
      (fields
        (field (name "MANUFACTURER PART") "Yo-WS2812B-3528反贴雾状")
        (field (name "SUPPLIER PART") "C9900003682")
        (field (name "SUPPLIER") "LCSC")
        (field (name "LCSC PART NAME") "Yo-WS2812B-3528反贴雾状")
      )
      (libsource (lib "easyedapro") (part "YO-WS2812B-3528_C9900003682"))
    )
    (comp (ref "U133")
      (value "Yo-WS2812B-3528反贴雾状")
      (footprint "ProPrj_HTX-easyedapro:LED-SMD_L3.2-W2.8_YO-WS2812B-3528")
      (fields
        (field (name "MANUFACTURER PART") "Yo-WS2812B-3528反贴雾状")
        (field (name "SUPPLIER PART") "C9900003682")
        (field (name "SUPPLIER") "LCSC")
        (field (name "LCSC PART NAME") "Yo-WS2812B-3528反贴雾状")
      )
      (libsource (lib "easyedapro") (part "YO-WS2812B-3528_C9900003682"))
    )
    (comp (ref "U134")
      (value "Yo-WS2812B-3528反贴雾状")
      (footprint "ProPrj_HTX-easyedapro:LED-SMD_L3.2-W2.8_YO-WS2812B-3528")
      (fields
        (field (name "MANUFACTURER PART") "Yo-WS2812B-3528反贴雾状")
        (field (name "SUPPLIER PART") "C9900003682")
        (field (name "SUPPLIER") "LCSC")
        (field (name "LCSC PART NAME") "Yo-WS2812B-3528反贴雾状")
      )
      (libsource (lib "easyedapro") (part "YO-WS2812B-3528_C9900003682"))
    )
    (comp (ref "U135")
      (value "Yo-WS2812B-3528反贴雾状")
      (footprint "ProPrj_HTX-easyedapro:LED-SMD_L3.2-W2.8_YO-WS2812B-3528")
      (fields
        (field (name "MANUFACTURER PART") "Yo-WS2812B-3528反贴雾状")
        (field (name "SUPPLIER PART") "C9900003682")
        (field (name "SUPPLIER") "LCSC")
        (field (name "LCSC PART NAME") "Yo-WS2812B-3528反贴雾状")
      )
      (libsource (lib "easyedapro") (part "YO-WS2812B-3528_C9900003682"))
    )
    (comp (ref "U136")
      (value "Yo-WS2812B-3528反贴雾状")
      (footprint "ProPrj_HTX-easyedapro:LED-SMD_L3.2-W2.8_YO-WS2812B-3528")
      (fields
        (field (name "MANUFACTURER PART") "Yo-WS2812B-3528反贴雾状")
        (field (name "SUPPLIER PART") "C9900003682")
        (field (name "SUPPLIER") "LCSC")
        (field (name "LCSC PART NAME") "Yo-WS2812B-3528反贴雾状")
      )
      (libsource (lib "easyedapro") (part "YO-WS2812B-3528_C9900003682"))
    )
    (comp (ref "U137")
      (value "Yo-WS2812B-3528反贴雾状")
      (footprint "ProPrj_HTX-easyedapro:LED-SMD_L3.2-W2.8_YO-WS2812B-3528")
      (fields
        (field (name "MANUFACTURER PART") "Yo-WS2812B-3528反贴雾状")
        (field (name "SUPPLIER PART") "C9900003682")
        (field (name "SUPPLIER") "LCSC")
        (field (name "LCSC PART NAME") "Yo-WS2812B-3528反贴雾状")
      )
      (libsource (lib "easyedapro") (part "YO-WS2812B-3528_C9900003682"))
    )
    (comp (ref "U138")
      (value "Yo-WS2812B-3528反贴雾状")
      (footprint "ProPrj_HTX-easyedapro:LED-SMD_L3.2-W2.8_YO-WS2812B-3528")
      (fields
        (field (name "MANUFACTURER PART") "Yo-WS2812B-3528反贴雾状")
        (field (name "SUPPLIER PART") "C9900003682")
        (field (name "SUPPLIER") "LCSC")
        (field (name "LCSC PART NAME") "Yo-WS2812B-3528反贴雾状")
      )
      (libsource (lib "easyedapro") (part "YO-WS2812B-3528_C9900003682"))
    )
    (comp (ref "U139")
      (value "Yo-WS2812B-3528反贴雾状")
      (footprint "ProPrj_HTX-easyedapro:LED-SMD_L3.2-W2.8_YO-WS2812B-3528")
      (fields
        (field (name "MANUFACTURER PART") "Yo-WS2812B-3528反贴雾状")
        (field (name "SUPPLIER PART") "C9900003682")
        (field (name "SUPPLIER") "LCSC")
        (field (name "LCSC PART NAME") "Yo-WS2812B-3528反贴雾状")
      )
      (libsource (lib "easyedapro") (part "YO-WS2812B-3528_C9900003682"))
    )
    (comp (ref "U140")
      (value "Yo-WS2812B-3528反贴雾状")
      (footprint "ProPrj_HTX-easyedapro:LED-SMD_L3.2-W2.8_YO-WS2812B-3528")
      (fields
        (field (name "MANUFACTURER PART") "Yo-WS2812B-3528反贴雾状")
        (field (name "SUPPLIER PART") "C9900003682")
        (field (name "SUPPLIER") "LCSC")
        (field (name "LCSC PART NAME") "Yo-WS2812B-3528反贴雾状")
      )
      (libsource (lib "easyedapro") (part "YO-WS2812B-3528_C9900003682"))
    )
    (comp (ref "U141")
      (value "Yo-WS2812B-3528反贴雾状")
      (footprint "ProPrj_HTX-easyedapro:LED-SMD_L3.2-W2.8_YO-WS2812B-3528")
      (fields
        (field (name "MANUFACTURER PART") "Yo-WS2812B-3528反贴雾状")
        (field (name "SUPPLIER PART") "C9900003682")
        (field (name "SUPPLIER") "LCSC")
        (field (name "LCSC PART NAME") "Yo-WS2812B-3528反贴雾状")
      )
      (libsource (lib "easyedapro") (part "YO-WS2812B-3528_C9900003682"))
    )
    (comp (ref "U142")
      (value "CPG151101S11-16")
      (footprint "ProPrj_HTX-easyedapro:SMD_KEYBOARD-SW")
      (fields
        (field (name "MANUFACTURER PART") "CPG151101S11-16")
        (field (name "MANUFACTURER") "HanElectricity(瀚源)")
        (field (name "SUPPLIER PART") "C41430893")
        (field (name "SUPPLIER") "LCSC")
        (field (name "LCSC PART NAME") "热插拔底座连接器 键盘配件")
      )
      (libsource (lib "easyedapro") (part "CPG151101S11-16_C41430893"))
    )
    (comp (ref "U143")
      (value "CPG151101S11-16")
      (footprint "ProPrj_HTX-easyedapro:SMD_KEYBOARD-SW")
      (fields
        (field (name "MANUFACTURER PART") "CPG151101S11-16")
        (field (name "MANUFACTURER") "HanElectricity(瀚源)")
        (field (name "SUPPLIER PART") "C41430893")
        (field (name "SUPPLIER") "LCSC")
        (field (name "LCSC PART NAME") "热插拔底座连接器 键盘配件")
      )
      (libsource (lib "easyedapro") (part "CPG151101S11-16_C41430893"))
    )
    (comp (ref "U144")
      (value "CPG151101S11-16")
      (footprint "ProPrj_HTX-easyedapro:SMD_KEYBOARD-SW")
      (fields
        (field (name "MANUFACTURER PART") "CPG151101S11-16")
        (field (name "MANUFACTURER") "HanElectricity(瀚源)")
        (field (name "SUPPLIER PART") "C41430893")
        (field (name "SUPPLIER") "LCSC")
        (field (name "LCSC PART NAME") "热插拔底座连接器 键盘配件")
      )
      (libsource (lib "easyedapro") (part "CPG151101S11-16_C41430893"))
    )
    (comp (ref "U145")
      (value "CPG151101S11-16")
      (footprint "ProPrj_HTX-easyedapro:SMD_KEYBOARD-SW")
      (fields
        (field (name "MANUFACTURER PART") "CPG151101S11-16")
        (field (name "MANUFACTURER") "HanElectricity(瀚源)")
        (field (name "SUPPLIER PART") "C41430893")
        (field (name "SUPPLIER") "LCSC")
        (field (name "LCSC PART NAME") "热插拔底座连接器 键盘配件")
      )
      (libsource (lib "easyedapro") (part "CPG151101S11-16_C41430893"))
    )
    (comp (ref "U146")
      (value "CPG151101S11-16")
      (footprint "ProPrj_HTX-easyedapro:SMD_KEYBOARD-SW")
      (fields
        (field (name "MANUFACTURER PART") "CPG151101S11-16")
        (field (name "MANUFACTURER") "HanElectricity(瀚源)")
        (field (name "SUPPLIER PART") "C41430893")
        (field (name "SUPPLIER") "LCSC")
        (field (name "LCSC PART NAME") "热插拔底座连接器 键盘配件")
      )
      (libsource (lib "easyedapro") (part "CPG151101S11-16_C41430893"))
    )
    (comp (ref "U147")
      (value "CPG151101S11-16")
      (footprint "ProPrj_HTX-easyedapro:SMD_KEYBOARD-SW")
      (fields
        (field (name "MANUFACTURER PART") "CPG151101S11-16")
        (field (name "MANUFACTURER") "HanElectricity(瀚源)")
        (field (name "SUPPLIER PART") "C41430893")
        (field (name "SUPPLIER") "LCSC")
        (field (name "LCSC PART NAME") "热插拔底座连接器 键盘配件")
      )
      (libsource (lib "easyedapro") (part "CPG151101S11-16_C41430893"))
    )
    (comp (ref "U148")
      (value "CPG151101S11-16")
      (footprint "ProPrj_HTX-easyedapro:SMD_KEYBOARD-SW")
      (fields
        (field (name "MANUFACTURER PART") "CPG151101S11-16")
        (field (name "MANUFACTURER") "HanElectricity(瀚源)")
        (field (name "SUPPLIER PART") "C41430893")
        (field (name "SUPPLIER") "LCSC")
        (field (name "LCSC PART NAME") "热插拔底座连接器 键盘配件")
      )
      (libsource (lib "easyedapro") (part "CPG151101S11-16_C41430893"))
    )
    (comp (ref "U149")
      (value "CPG151101S11-16")
      (footprint "ProPrj_HTX-easyedapro:SMD_KEYBOARD-SW")
      (fields
        (field (name "MANUFACTURER PART") "CPG151101S11-16")
        (field (name "MANUFACTURER") "HanElectricity(瀚源)")
        (field (name "SUPPLIER PART") "C41430893")
        (field (name "SUPPLIER") "LCSC")
        (field (name "LCSC PART NAME") "热插拔底座连接器 键盘配件")
      )
      (libsource (lib "easyedapro") (part "CPG151101S11-16_C41430893"))
    )
    (comp (ref "U150")
      (value "CPG151101S11-16")
      (footprint "ProPrj_HTX-easyedapro:SMD_KEYBOARD-SW")
      (fields
        (field (name "MANUFACTURER PART") "CPG151101S11-16")
        (field (name "MANUFACTURER") "HanElectricity(瀚源)")
        (field (name "SUPPLIER PART") "C41430893")
        (field (name "SUPPLIER") "LCSC")
        (field (name "LCSC PART NAME") "热插拔底座连接器 键盘配件")
      )
      (libsource (lib "easyedapro") (part "CPG151101S11-16_C41430893"))
    )
    (comp (ref "U151")
      (value "CPG151101S11-16")
      (footprint "ProPrj_HTX-easyedapro:SMD_KEYBOARD-SW")
      (fields
        (field (name "MANUFACTURER PART") "CPG151101S11-16")
        (field (name "MANUFACTURER") "HanElectricity(瀚源)")
        (field (name "SUPPLIER PART") "C41430893")
        (field (name "SUPPLIER") "LCSC")
        (field (name "LCSC PART NAME") "热插拔底座连接器 键盘配件")
      )
      (libsource (lib "easyedapro") (part "CPG151101S11-16_C41430893"))
    )
    (comp (ref "U152")
      (value "CPG151101S11-16")
      (footprint "ProPrj_HTX-easyedapro:SMD_KEYBOARD-SW")
      (fields
        (field (name "MANUFACTURER PART") "CPG151101S11-16")
        (field (name "MANUFACTURER") "HanElectricity(瀚源)")
        (field (name "SUPPLIER PART") "C41430893")
        (field (name "SUPPLIER") "LCSC")
        (field (name "LCSC PART NAME") "热插拔底座连接器 键盘配件")
      )
      (libsource (lib "easyedapro") (part "CPG151101S11-16_C41430893"))
    )
    (comp (ref "U153")
      (value "CPG151101S11-16")
      (footprint "ProPrj_HTX-easyedapro:SMD_KEYBOARD-SW")
      (fields
        (field (name "MANUFACTURER PART") "CPG151101S11-16")
        (field (name "MANUFACTURER") "HanElectricity(瀚源)")
        (field (name "SUPPLIER PART") "C41430893")
        (field (name "SUPPLIER") "LCSC")
        (field (name "LCSC PART NAME") "热插拔底座连接器 键盘配件")
      )
      (libsource (lib "easyedapro") (part "CPG151101S11-16_C41430893"))
    )
    (comp (ref "U154")
      (value "CPG151101S11-16")
      (footprint "ProPrj_HTX-easyedapro:SMD_KEYBOARD-SW")
      (fields
        (field (name "MANUFACTURER PART") "CPG151101S11-16")
        (field (name "MANUFACTURER") "HanElectricity(瀚源)")
        (field (name "SUPPLIER PART") "C41430893")
        (field (name "SUPPLIER") "LCSC")
        (field (name "LCSC PART NAME") "热插拔底座连接器 键盘配件")
      )
      (libsource (lib "easyedapro") (part "CPG151101S11-16_C41430893"))
    )
    (comp (ref "U155")
      (value "CPG151101S11-16")
      (footprint "ProPrj_HTX-easyedapro:SMD_KEYBOARD-SW")
      (fields
        (field (name "MANUFACTURER PART") "CPG151101S11-16")
        (field (name "MANUFACTURER") "HanElectricity(瀚源)")
        (field (name "SUPPLIER PART") "C41430893")
        (field (name "SUPPLIER") "LCSC")
        (field (name "LCSC PART NAME") "热插拔底座连接器 键盘配件")
      )
      (libsource (lib "easyedapro") (part "CPG151101S11-16_C41430893"))
    )
    (comp (ref "U156")
      (value "Yo-WS2812B-3528反贴雾状")
      (footprint "ProPrj_HTX-easyedapro:LED-SMD_L3.2-W2.8_YO-WS2812B-3528")
      (fields
        (field (name "MANUFACTURER PART") "Yo-WS2812B-3528反贴雾状")
        (field (name "SUPPLIER PART") "C9900003682")
        (field (name "SUPPLIER") "LCSC")
        (field (name "LCSC PART NAME") "Yo-WS2812B-3528反贴雾状")
      )
      (libsource (lib "easyedapro") (part "YO-WS2812B-3528_C9900003682"))
    )
    (comp (ref "U157")
      (value "Yo-WS2812B-3528反贴雾状")
      (footprint "ProPrj_HTX-easyedapro:LED-SMD_L3.2-W2.8_YO-WS2812B-3528")
      (fields
        (field (name "MANUFACTURER PART") "Yo-WS2812B-3528反贴雾状")
        (field (name "SUPPLIER PART") "C9900003682")
        (field (name "SUPPLIER") "LCSC")
        (field (name "LCSC PART NAME") "Yo-WS2812B-3528反贴雾状")
      )
      (libsource (lib "easyedapro") (part "YO-WS2812B-3528_C9900003682"))
    )
    (comp (ref "U158")
      (value "Yo-WS2812B-3528反贴雾状")
      (footprint "ProPrj_HTX-easyedapro:LED-SMD_L3.2-W2.8_YO-WS2812B-3528")
      (fields
        (field (name "MANUFACTURER PART") "Yo-WS2812B-3528反贴雾状")
        (field (name "SUPPLIER PART") "C9900003682")
        (field (name "SUPPLIER") "LCSC")
        (field (name "LCSC PART NAME") "Yo-WS2812B-3528反贴雾状")
      )
      (libsource (lib "easyedapro") (part "YO-WS2812B-3528_C9900003682"))
    )
    (comp (ref "U159")
      (value "Yo-WS2812B-3528反贴雾状")
      (footprint "ProPrj_HTX-easyedapro:LED-SMD_L3.2-W2.8_YO-WS2812B-3528")
      (fields
        (field (name "MANUFACTURER PART") "Yo-WS2812B-3528反贴雾状")
        (field (name "SUPPLIER PART") "C9900003682")
        (field (name "SUPPLIER") "LCSC")
        (field (name "LCSC PART NAME") "Yo-WS2812B-3528反贴雾状")
      )
      (libsource (lib "easyedapro") (part "YO-WS2812B-3528_C9900003682"))
    )
    (comp (ref "U160")
      (value "Yo-WS2812B-3528反贴雾状")
      (footprint "ProPrj_HTX-easyedapro:LED-SMD_L3.2-W2.8_YO-WS2812B-3528")
      (fields
        (field (name "MANUFACTURER PART") "Yo-WS2812B-3528反贴雾状")
        (field (name "SUPPLIER PART") "C9900003682")
        (field (name "SUPPLIER") "LCSC")
        (field (name "LCSC PART NAME") "Yo-WS2812B-3528反贴雾状")
      )
      (libsource (lib "easyedapro") (part "YO-WS2812B-3528_C9900003682"))
    )
    (comp (ref "U161")
      (value "Yo-WS2812B-3528反贴雾状")
      (footprint "ProPrj_HTX-easyedapro:LED-SMD_L3.2-W2.8_YO-WS2812B-3528")
      (fields
        (field (name "MANUFACTURER PART") "Yo-WS2812B-3528反贴雾状")
        (field (name "SUPPLIER PART") "C9900003682")
        (field (name "SUPPLIER") "LCSC")
        (field (name "LCSC PART NAME") "Yo-WS2812B-3528反贴雾状")
      )
      (libsource (lib "easyedapro") (part "YO-WS2812B-3528_C9900003682"))
    )
    (comp (ref "U162")
      (value "Yo-WS2812B-3528反贴雾状")
      (footprint "ProPrj_HTX-easyedapro:LED-SMD_L3.2-W2.8_YO-WS2812B-3528")
      (fields
        (field (name "MANUFACTURER PART") "Yo-WS2812B-3528反贴雾状")
        (field (name "SUPPLIER PART") "C9900003682")
        (field (name "SUPPLIER") "LCSC")
        (field (name "LCSC PART NAME") "Yo-WS2812B-3528反贴雾状")
      )
      (libsource (lib "easyedapro") (part "YO-WS2812B-3528_C9900003682"))
    )
    (comp (ref "U163")
      (value "Yo-WS2812B-3528反贴雾状")
      (footprint "ProPrj_HTX-easyedapro:LED-SMD_L3.2-W2.8_YO-WS2812B-3528")
      (fields
        (field (name "MANUFACTURER PART") "Yo-WS2812B-3528反贴雾状")
        (field (name "SUPPLIER PART") "C9900003682")
        (field (name "SUPPLIER") "LCSC")
        (field (name "LCSC PART NAME") "Yo-WS2812B-3528反贴雾状")
      )
      (libsource (lib "easyedapro") (part "YO-WS2812B-3528_C9900003682"))
    )
    (comp (ref "U164")
      (value "Yo-WS2812B-3528反贴雾状")
      (footprint "ProPrj_HTX-easyedapro:LED-SMD_L3.2-W2.8_YO-WS2812B-3528")
      (fields
        (field (name "MANUFACTURER PART") "Yo-WS2812B-3528反贴雾状")
        (field (name "SUPPLIER PART") "C9900003682")
        (field (name "SUPPLIER") "LCSC")
        (field (name "LCSC PART NAME") "Yo-WS2812B-3528反贴雾状")
      )
      (libsource (lib "easyedapro") (part "YO-WS2812B-3528_C9900003682"))
    )
    (comp (ref "U165")
      (value "Yo-WS2812B-3528反贴雾状")
      (footprint "ProPrj_HTX-easyedapro:LED-SMD_L3.2-W2.8_YO-WS2812B-3528")
      (fields
        (field (name "MANUFACTURER PART") "Yo-WS2812B-3528反贴雾状")
        (field (name "SUPPLIER PART") "C9900003682")
        (field (name "SUPPLIER") "LCSC")
        (field (name "LCSC PART NAME") "Yo-WS2812B-3528反贴雾状")
      )
      (libsource (lib "easyedapro") (part "YO-WS2812B-3528_C9900003682"))
    )
    (comp (ref "U166")
      (value "Yo-WS2812B-3528反贴雾状")
      (footprint "ProPrj_HTX-easyedapro:LED-SMD_L3.2-W2.8_YO-WS2812B-3528")
      (fields
        (field (name "MANUFACTURER PART") "Yo-WS2812B-3528反贴雾状")
        (field (name "SUPPLIER PART") "C9900003682")
        (field (name "SUPPLIER") "LCSC")
        (field (name "LCSC PART NAME") "Yo-WS2812B-3528反贴雾状")
      )
      (libsource (lib "easyedapro") (part "YO-WS2812B-3528_C9900003682"))
    )
    (comp (ref "U167")
      (value "Yo-WS2812B-3528反贴雾状")
      (footprint "ProPrj_HTX-easyedapro:LED-SMD_L3.2-W2.8_YO-WS2812B-3528")
      (fields
        (field (name "MANUFACTURER PART") "Yo-WS2812B-3528反贴雾状")
        (field (name "SUPPLIER PART") "C9900003682")
        (field (name "SUPPLIER") "LCSC")
        (field (name "LCSC PART NAME") "Yo-WS2812B-3528反贴雾状")
      )
      (libsource (lib "easyedapro") (part "YO-WS2812B-3528_C9900003682"))
    )
    (comp (ref "U168")
      (value "CPG151101S11-16")
      (footprint "ProPrj_HTX-easyedapro:SMD_KEYBOARD-SW")
      (fields
        (field (name "MANUFACTURER PART") "CPG151101S11-16")
        (field (name "MANUFACTURER") "HanElectricity(瀚源)")
        (field (name "SUPPLIER PART") "C41430893")
        (field (name "SUPPLIER") "LCSC")
        (field (name "LCSC PART NAME") "热插拔底座连接器 键盘配件")
      )
      (libsource (lib "easyedapro") (part "CPG151101S11-16_C41430893"))
    )
    (comp (ref "U169")
      (value "CPG151101S11-16")
      (footprint "ProPrj_HTX-easyedapro:SMD_KEYBOARD-SW")
      (fields
        (field (name "MANUFACTURER PART") "CPG151101S11-16")
        (field (name "MANUFACTURER") "HanElectricity(瀚源)")
        (field (name "SUPPLIER PART") "C41430893")
        (field (name "SUPPLIER") "LCSC")
        (field (name "LCSC PART NAME") "热插拔底座连接器 键盘配件")
      )
      (libsource (lib "easyedapro") (part "CPG151101S11-16_C41430893"))
    )
    (comp (ref "U170")
      (value "CPG151101S11-16")
      (footprint "ProPrj_HTX-easyedapro:SMD_KEYBOARD-SW")
      (fields
        (field (name "MANUFACTURER PART") "CPG151101S11-16")
        (field (name "MANUFACTURER") "HanElectricity(瀚源)")
        (field (name "SUPPLIER PART") "C41430893")
        (field (name "SUPPLIER") "LCSC")
        (field (name "LCSC PART NAME") "热插拔底座连接器 键盘配件")
      )
      (libsource (lib "easyedapro") (part "CPG151101S11-16_C41430893"))
    )
    (comp (ref "U171")
      (value "CPG151101S11-16")
      (footprint "ProPrj_HTX-easyedapro:SMD_KEYBOARD-SW")
      (fields
        (field (name "MANUFACTURER PART") "CPG151101S11-16")
        (field (name "MANUFACTURER") "HanElectricity(瀚源)")
        (field (name "SUPPLIER PART") "C41430893")
        (field (name "SUPPLIER") "LCSC")
        (field (name "LCSC PART NAME") "热插拔底座连接器 键盘配件")
      )
      (libsource (lib "easyedapro") (part "CPG151101S11-16_C41430893"))
    )
    (comp (ref "U172")
      (value "CPG151101S11-16")
      (footprint "ProPrj_HTX-easyedapro:SMD_KEYBOARD-SW")
      (fields
        (field (name "MANUFACTURER PART") "CPG151101S11-16")
        (field (name "MANUFACTURER") "HanElectricity(瀚源)")
        (field (name "SUPPLIER PART") "C41430893")
        (field (name "SUPPLIER") "LCSC")
        (field (name "LCSC PART NAME") "热插拔底座连接器 键盘配件")
      )
      (libsource (lib "easyedapro") (part "CPG151101S11-16_C41430893"))
    )
    (comp (ref "U173")
      (value "CPG151101S11-16")
      (footprint "ProPrj_HTX-easyedapro:SMD_KEYBOARD-SW")
      (fields
        (field (name "MANUFACTURER PART") "CPG151101S11-16")
        (field (name "MANUFACTURER") "HanElectricity(瀚源)")
        (field (name "SUPPLIER PART") "C41430893")
        (field (name "SUPPLIER") "LCSC")
        (field (name "LCSC PART NAME") "热插拔底座连接器 键盘配件")
      )
      (libsource (lib "easyedapro") (part "CPG151101S11-16_C41430893"))
    )
    (comp (ref "U174")
      (value "CPG151101S11-16")
      (footprint "ProPrj_HTX-easyedapro:SMD_KEYBOARD-SW")
      (fields
        (field (name "MANUFACTURER PART") "CPG151101S11-16")
        (field (name "MANUFACTURER") "HanElectricity(瀚源)")
        (field (name "SUPPLIER PART") "C41430893")
        (field (name "SUPPLIER") "LCSC")
        (field (name "LCSC PART NAME") "热插拔底座连接器 键盘配件")
      )
      (libsource (lib "easyedapro") (part "CPG151101S11-16_C41430893"))
    )
    (comp (ref "U175")
      (value "CPG151101S11-16")
      (footprint "ProPrj_HTX-easyedapro:SMD_KEYBOARD-SW")
      (fields
        (field (name "MANUFACTURER PART") "CPG151101S11-16")
        (field (name "MANUFACTURER") "HanElectricity(瀚源)")
        (field (name "SUPPLIER PART") "C41430893")
        (field (name "SUPPLIER") "LCSC")
        (field (name "LCSC PART NAME") "热插拔底座连接器 键盘配件")
      )
      (libsource (lib "easyedapro") (part "CPG151101S11-16_C41430893"))
    )
    (comp (ref "U176")
      (value "CPG151101S11-16")
      (footprint "ProPrj_HTX-easyedapro:SMD_KEYBOARD-SW")
      (fields
        (field (name "MANUFACTURER PART") "CPG151101S11-16")
        (field (name "MANUFACTURER") "HanElectricity(瀚源)")
        (field (name "SUPPLIER PART") "C41430893")
        (field (name "SUPPLIER") "LCSC")
        (field (name "LCSC PART NAME") "热插拔底座连接器 键盘配件")
      )
      (libsource (lib "easyedapro") (part "CPG151101S11-16_C41430893"))
    )
    (comp (ref "U177")
      (value "CPG151101S11-16")
      (footprint "ProPrj_HTX-easyedapro:SMD_KEYBOARD-SW")
      (fields
        (field (name "MANUFACTURER PART") "CPG151101S11-16")
        (field (name "MANUFACTURER") "HanElectricity(瀚源)")
        (field (name "SUPPLIER PART") "C41430893")
        (field (name "SUPPLIER") "LCSC")
        (field (name "LCSC PART NAME") "热插拔底座连接器 键盘配件")
      )
      (libsource (lib "easyedapro") (part "CPG151101S11-16_C41430893"))
    )
    (comp (ref "U178")
      (value "CPG151101S11-16")
      (footprint "ProPrj_HTX-easyedapro:SMD_KEYBOARD-SW")
      (fields
        (field (name "MANUFACTURER PART") "CPG151101S11-16")
        (field (name "MANUFACTURER") "HanElectricity(瀚源)")
        (field (name "SUPPLIER PART") "C41430893")
        (field (name "SUPPLIER") "LCSC")
        (field (name "LCSC PART NAME") "热插拔底座连接器 键盘配件")
      )
      (libsource (lib "easyedapro") (part "CPG151101S11-16_C41430893"))
    )
    (comp (ref "U179")
      (value "CPG151101S11-16")
      (footprint "ProPrj_HTX-easyedapro:SMD_KEYBOARD-SW")
      (fields
        (field (name "MANUFACTURER PART") "CPG151101S11-16")
        (field (name "MANUFACTURER") "HanElectricity(瀚源)")
        (field (name "SUPPLIER PART") "C41430893")
        (field (name "SUPPLIER") "LCSC")
        (field (name "LCSC PART NAME") "热插拔底座连接器 键盘配件")
      )
      (libsource (lib "easyedapro") (part "CPG151101S11-16_C41430893"))
    )
    (comp (ref "U180")
      (value "XL-3528RGBC-WS2812B")
      (footprint "ProPrj_HTX-easyedapro:LED-SMD_4P-L3.5-W2.8-BR-1")
      (fields
        (field (name "MANUFACTURER PART") "XL-3528RGBC-WS2812B")
        (field (name "MANUFACTURER") "XINGLIGHT(成兴光)")
        (field (name "SUPPLIER PART") "C5440693")
        (field (name "SUPPLIER") "LCSC")
        (field (name "LCSC PART NAME") "XL-3528RGBC-WS2812B")
      )
      (libsource (lib "easyedapro") (part "XL-3528RGBC-WS2812B"))
    )
    (comp (ref "U181")
      (value "XL-3528RGBC-WS2812B")
      (footprint "ProPrj_HTX-easyedapro:LED-SMD_4P-L3.5-W2.8-BR-1")
      (fields
        (field (name "MANUFACTURER PART") "XL-3528RGBC-WS2812B")
        (field (name "MANUFACTURER") "XINGLIGHT(成兴光)")
        (field (name "SUPPLIER PART") "C5440693")
        (field (name "SUPPLIER") "LCSC")
        (field (name "LCSC PART NAME") "XL-3528RGBC-WS2812B")
      )
      (libsource (lib "easyedapro") (part "XL-3528RGBC-WS2812B"))
    )
    (comp (ref "U182")
      (value "Yo-WS2812B-3528反贴雾状")
      (footprint "ProPrj_HTX-easyedapro:LED-SMD_L3.2-W2.8_YO-WS2812B-3528")
      (fields
        (field (name "MANUFACTURER PART") "Yo-WS2812B-3528反贴雾状")
        (field (name "SUPPLIER PART") "C9900003682")
        (field (name "SUPPLIER") "LCSC")
        (field (name "LCSC PART NAME") "Yo-WS2812B-3528反贴雾状")
      )
      (libsource (lib "easyedapro") (part "YO-WS2812B-3528_C9900003682"))
    )
    (comp (ref "U183")
      (value "Yo-WS2812B-3528反贴雾状")
      (footprint "ProPrj_HTX-easyedapro:LED-SMD_L3.2-W2.8_YO-WS2812B-3528")
      (fields
        (field (name "MANUFACTURER PART") "Yo-WS2812B-3528反贴雾状")
        (field (name "SUPPLIER PART") "C9900003682")
        (field (name "SUPPLIER") "LCSC")
        (field (name "LCSC PART NAME") "Yo-WS2812B-3528反贴雾状")
      )
      (libsource (lib "easyedapro") (part "YO-WS2812B-3528_C9900003682"))
    )
    (comp (ref "U184")
      (value "Yo-WS2812B-3528反贴雾状")
      (footprint "ProPrj_HTX-easyedapro:LED-SMD_L3.2-W2.8_YO-WS2812B-3528")
      (fields
        (field (name "MANUFACTURER PART") "Yo-WS2812B-3528反贴雾状")
        (field (name "SUPPLIER PART") "C9900003682")
        (field (name "SUPPLIER") "LCSC")
        (field (name "LCSC PART NAME") "Yo-WS2812B-3528反贴雾状")
      )
      (libsource (lib "easyedapro") (part "YO-WS2812B-3528_C9900003682"))
    )
    (comp (ref "U185")
      (value "Yo-WS2812B-3528反贴雾状")
      (footprint "ProPrj_HTX-easyedapro:LED-SMD_L3.2-W2.8_YO-WS2812B-3528")
      (fields
        (field (name "MANUFACTURER PART") "Yo-WS2812B-3528反贴雾状")
        (field (name "SUPPLIER PART") "C9900003682")
        (field (name "SUPPLIER") "LCSC")
        (field (name "LCSC PART NAME") "Yo-WS2812B-3528反贴雾状")
      )
      (libsource (lib "easyedapro") (part "YO-WS2812B-3528_C9900003682"))
    )
    (comp (ref "U186")
      (value "Yo-WS2812B-3528反贴雾状")
      (footprint "ProPrj_HTX-easyedapro:LED-SMD_L3.2-W2.8_YO-WS2812B-3528")
      (fields
        (field (name "MANUFACTURER PART") "Yo-WS2812B-3528反贴雾状")
        (field (name "SUPPLIER PART") "C9900003682")
        (field (name "SUPPLIER") "LCSC")
        (field (name "LCSC PART NAME") "Yo-WS2812B-3528反贴雾状")
      )
      (libsource (lib "easyedapro") (part "YO-WS2812B-3528_C9900003682"))
    )
    (comp (ref "U187")
      (value "Yo-WS2812B-3528反贴雾状")
      (footprint "ProPrj_HTX-easyedapro:LED-SMD_L3.2-W2.8_YO-WS2812B-3528")
      (fields
        (field (name "MANUFACTURER PART") "Yo-WS2812B-3528反贴雾状")
        (field (name "SUPPLIER PART") "C9900003682")
        (field (name "SUPPLIER") "LCSC")
        (field (name "LCSC PART NAME") "Yo-WS2812B-3528反贴雾状")
      )
      (libsource (lib "easyedapro") (part "YO-WS2812B-3528_C9900003682"))
    )
    (comp (ref "U188")
      (value "Yo-WS2812B-3528反贴雾状")
      (footprint "ProPrj_HTX-easyedapro:LED-SMD_L3.2-W2.8_YO-WS2812B-3528")
      (fields
        (field (name "MANUFACTURER PART") "Yo-WS2812B-3528反贴雾状")
        (field (name "SUPPLIER PART") "C9900003682")
        (field (name "SUPPLIER") "LCSC")
        (field (name "LCSC PART NAME") "Yo-WS2812B-3528反贴雾状")
      )
      (libsource (lib "easyedapro") (part "YO-WS2812B-3528_C9900003682"))
    )
    (comp (ref "U189")
      (value "Yo-WS2812B-3528反贴雾状")
      (footprint "ProPrj_HTX-easyedapro:LED-SMD_L3.2-W2.8_YO-WS2812B-3528")
      (fields
        (field (name "MANUFACTURER PART") "Yo-WS2812B-3528反贴雾状")
        (field (name "SUPPLIER PART") "C9900003682")
        (field (name "SUPPLIER") "LCSC")
        (field (name "LCSC PART NAME") "Yo-WS2812B-3528反贴雾状")
      )
      (libsource (lib "easyedapro") (part "YO-WS2812B-3528_C9900003682"))
    )
    (comp (ref "U190")
      (value "CPG151101S11-16")
      (footprint "ProPrj_HTX-easyedapro:SMD_KEYBOARD-SW")
      (fields
        (field (name "MANUFACTURER PART") "CPG151101S11-16")
        (field (name "MANUFACTURER") "HanElectricity(瀚源)")
        (field (name "SUPPLIER PART") "C41430893")
        (field (name "SUPPLIER") "LCSC")
        (field (name "LCSC PART NAME") "热插拔底座连接器 键盘配件")
      )
      (libsource (lib "easyedapro") (part "CPG151101S11-16_C41430893"))
    )
    (comp (ref "U191")
      (value "CPG151101S11-16")
      (footprint "ProPrj_HTX-easyedapro:SMD_KEYBOARD-SW")
      (fields
        (field (name "MANUFACTURER PART") "CPG151101S11-16")
        (field (name "MANUFACTURER") "HanElectricity(瀚源)")
        (field (name "SUPPLIER PART") "C41430893")
        (field (name "SUPPLIER") "LCSC")
        (field (name "LCSC PART NAME") "热插拔底座连接器 键盘配件")
      )
      (libsource (lib "easyedapro") (part "CPG151101S11-16_C41430893"))
    )
    (comp (ref "U192")
      (value "CPG151101S11-16")
      (footprint "ProPrj_HTX-easyedapro:SMD_KEYBOARD-SW")
      (fields
        (field (name "MANUFACTURER PART") "CPG151101S11-16")
        (field (name "MANUFACTURER") "HanElectricity(瀚源)")
        (field (name "SUPPLIER PART") "C41430893")
        (field (name "SUPPLIER") "LCSC")
        (field (name "LCSC PART NAME") "热插拔底座连接器 键盘配件")
      )
      (libsource (lib "easyedapro") (part "CPG151101S11-16_C41430893"))
    )
    (comp (ref "U193")
      (value "CPG151101S11-16")
      (footprint "ProPrj_HTX-easyedapro:SMD_KEYBOARD-SW")
      (fields
        (field (name "MANUFACTURER PART") "CPG151101S11-16")
        (field (name "MANUFACTURER") "HanElectricity(瀚源)")
        (field (name "SUPPLIER PART") "C41430893")
        (field (name "SUPPLIER") "LCSC")
        (field (name "LCSC PART NAME") "热插拔底座连接器 键盘配件")
      )
      (libsource (lib "easyedapro") (part "CPG151101S11-16_C41430893"))
    )
    (comp (ref "U194")
      (value "CPG151101S11-16")
      (footprint "ProPrj_HTX-easyedapro:SMD_KEYBOARD-SW")
      (fields
        (field (name "MANUFACTURER PART") "CPG151101S11-16")
        (field (name "MANUFACTURER") "HanElectricity(瀚源)")
        (field (name "SUPPLIER PART") "C41430893")
        (field (name "SUPPLIER") "LCSC")
        (field (name "LCSC PART NAME") "热插拔底座连接器 键盘配件")
      )
      (libsource (lib "easyedapro") (part "CPG151101S11-16_C41430893"))
    )
    (comp (ref "U195")
      (value "CPG151101S11-16")
      (footprint "ProPrj_HTX-easyedapro:SMD_KEYBOARD-SW")
      (fields
        (field (name "MANUFACTURER PART") "CPG151101S11-16")
        (field (name "MANUFACTURER") "HanElectricity(瀚源)")
        (field (name "SUPPLIER PART") "C41430893")
        (field (name "SUPPLIER") "LCSC")
        (field (name "LCSC PART NAME") "热插拔底座连接器 键盘配件")
      )
      (libsource (lib "easyedapro") (part "CPG151101S11-16_C41430893"))
    )
    (comp (ref "U196")
      (value "CPG151101S11-16")
      (footprint "ProPrj_HTX-easyedapro:SMD_KEYBOARD-SW")
      (fields
        (field (name "MANUFACTURER PART") "CPG151101S11-16")
        (field (name "MANUFACTURER") "HanElectricity(瀚源)")
        (field (name "SUPPLIER PART") "C41430893")
        (field (name "SUPPLIER") "LCSC")
        (field (name "LCSC PART NAME") "热插拔底座连接器 键盘配件")
      )
      (libsource (lib "easyedapro") (part "CPG151101S11-16_C41430893"))
    )
    (comp (ref "U197")
      (value "CPG151101S11-16")
      (footprint "ProPrj_HTX-easyedapro:SMD_KEYBOARD-SW")
      (fields
        (field (name "MANUFACTURER PART") "CPG151101S11-16")
        (field (name "MANUFACTURER") "HanElectricity(瀚源)")
        (field (name "SUPPLIER PART") "C41430893")
        (field (name "SUPPLIER") "LCSC")
        (field (name "LCSC PART NAME") "热插拔底座连接器 键盘配件")
      )
      (libsource (lib "easyedapro") (part "CPG151101S11-16_C41430893"))
    )
    (comp (ref "U198")
      (value "Yo-WS2812B-3528反贴雾状")
      (footprint "ProPrj_HTX-easyedapro:LED-SMD_L3.2-W2.8_YO-WS2812B-3528")
      (fields
        (field (name "MANUFACTURER PART") "Yo-WS2812B-3528反贴雾状")
        (field (name "SUPPLIER PART") "C9900003682")
        (field (name "SUPPLIER") "LCSC")
        (field (name "LCSC PART NAME") "Yo-WS2812B-3528反贴雾状")
      )
      (libsource (lib "easyedapro") (part "YO-WS2812B-3528_C9900003682"))
    )
    (comp (ref "U199")
      (value "Yo-WS2812B-3528反贴雾状")
      (footprint "ProPrj_HTX-easyedapro:LED-SMD_L3.2-W2.8_YO-WS2812B-3528")
      (fields
        (field (name "MANUFACTURER PART") "Yo-WS2812B-3528反贴雾状")
        (field (name "SUPPLIER PART") "C9900003682")
        (field (name "SUPPLIER") "LCSC")
        (field (name "LCSC PART NAME") "Yo-WS2812B-3528反贴雾状")
      )
      (libsource (lib "easyedapro") (part "YO-WS2812B-3528_C9900003682"))
    )
    (comp (ref "U200")
      (value "Yo-WS2812B-3528反贴雾状")
      (footprint "ProPrj_HTX-easyedapro:LED-SMD_L3.2-W2.8_YO-WS2812B-3528")
      (fields
        (field (name "MANUFACTURER PART") "Yo-WS2812B-3528反贴雾状")
        (field (name "SUPPLIER PART") "C9900003682")
        (field (name "SUPPLIER") "LCSC")
        (field (name "LCSC PART NAME") "Yo-WS2812B-3528反贴雾状")
      )
      (libsource (lib "easyedapro") (part "YO-WS2812B-3528_C9900003682"))
    )
    (comp (ref "U201")
      (value "Yo-WS2812B-3528反贴雾状")
      (footprint "ProPrj_HTX-easyedapro:LED-SMD_L3.2-W2.8_YO-WS2812B-3528")
      (fields
        (field (name "MANUFACTURER PART") "Yo-WS2812B-3528反贴雾状")
        (field (name "SUPPLIER PART") "C9900003682")
        (field (name "SUPPLIER") "LCSC")
        (field (name "LCSC PART NAME") "Yo-WS2812B-3528反贴雾状")
      )
      (libsource (lib "easyedapro") (part "YO-WS2812B-3528_C9900003682"))
    )
    (comp (ref "U202")
      (value "Yo-WS2812B-3528反贴雾状")
      (footprint "ProPrj_HTX-easyedapro:LED-SMD_L3.2-W2.8_YO-WS2812B-3528")
      (fields
        (field (name "MANUFACTURER PART") "Yo-WS2812B-3528反贴雾状")
        (field (name "SUPPLIER PART") "C9900003682")
        (field (name "SUPPLIER") "LCSC")
        (field (name "LCSC PART NAME") "Yo-WS2812B-3528反贴雾状")
      )
      (libsource (lib "easyedapro") (part "YO-WS2812B-3528_C9900003682"))
    )
    (comp (ref "U203")
      (value "Yo-WS2812B-3528反贴雾状")
      (footprint "ProPrj_HTX-easyedapro:LED-SMD_L3.2-W2.8_YO-WS2812B-3528")
      (fields
        (field (name "MANUFACTURER PART") "Yo-WS2812B-3528反贴雾状")
        (field (name "SUPPLIER PART") "C9900003682")
        (field (name "SUPPLIER") "LCSC")
        (field (name "LCSC PART NAME") "Yo-WS2812B-3528反贴雾状")
      )
      (libsource (lib "easyedapro") (part "YO-WS2812B-3528_C9900003682"))
    )
    (comp (ref "U204")
      (value "Yo-WS2812B-3528反贴雾状")
      (footprint "ProPrj_HTX-easyedapro:LED-SMD_L3.2-W2.8_YO-WS2812B-3528")
      (fields
        (field (name "MANUFACTURER PART") "Yo-WS2812B-3528反贴雾状")
        (field (name "SUPPLIER PART") "C9900003682")
        (field (name "SUPPLIER") "LCSC")
        (field (name "LCSC PART NAME") "Yo-WS2812B-3528反贴雾状")
      )
      (libsource (lib "easyedapro") (part "YO-WS2812B-3528_C9900003682"))
    )
    (comp (ref "U205")
      (value "Yo-WS2812B-3528反贴雾状")
      (footprint "ProPrj_HTX-easyedapro:LED-SMD_L3.2-W2.8_YO-WS2812B-3528")
      (fields
        (field (name "MANUFACTURER PART") "Yo-WS2812B-3528反贴雾状")
        (field (name "SUPPLIER PART") "C9900003682")
        (field (name "SUPPLIER") "LCSC")
        (field (name "LCSC PART NAME") "Yo-WS2812B-3528反贴雾状")
      )
      (libsource (lib "easyedapro") (part "YO-WS2812B-3528_C9900003682"))
    )
    (comp (ref "U206")
      (value "Yo-WS2812B-3528反贴雾状")
      (footprint "ProPrj_HTX-easyedapro:LED-SMD_L3.2-W2.8_YO-WS2812B-3528")
      (fields
        (field (name "MANUFACTURER PART") "Yo-WS2812B-3528反贴雾状")
        (field (name "SUPPLIER PART") "C9900003682")
        (field (name "SUPPLIER") "LCSC")
        (field (name "LCSC PART NAME") "Yo-WS2812B-3528反贴雾状")
      )
      (libsource (lib "easyedapro") (part "YO-WS2812B-3528_C9900003682"))
    )
    (comp (ref "U207")
      (value "CPG151101S11-16")
      (footprint "ProPrj_HTX-easyedapro:SMD_KEYBOARD-SW")
      (fields
        (field (name "MANUFACTURER PART") "CPG151101S11-16")
        (field (name "MANUFACTURER") "HanElectricity(瀚源)")
        (field (name "SUPPLIER PART") "C41430893")
        (field (name "SUPPLIER") "LCSC")
        (field (name "LCSC PART NAME") "热插拔底座连接器 键盘配件")
      )
      (libsource (lib "easyedapro") (part "CPG151101S11-16_C41430893"))
    )
    (comp (ref "U208")
      (value "CPG151101S11-16")
      (footprint "ProPrj_HTX-easyedapro:SMD_KEYBOARD-SW")
      (fields
        (field (name "MANUFACTURER PART") "CPG151101S11-16")
        (field (name "MANUFACTURER") "HanElectricity(瀚源)")
        (field (name "SUPPLIER PART") "C41430893")
        (field (name "SUPPLIER") "LCSC")
        (field (name "LCSC PART NAME") "热插拔底座连接器 键盘配件")
      )
      (libsource (lib "easyedapro") (part "CPG151101S11-16_C41430893"))
    )
    (comp (ref "U209")
      (value "CPG151101S11-16")
      (footprint "ProPrj_HTX-easyedapro:SMD_KEYBOARD-SW")
      (fields
        (field (name "MANUFACTURER PART") "CPG151101S11-16")
        (field (name "MANUFACTURER") "HanElectricity(瀚源)")
        (field (name "SUPPLIER PART") "C41430893")
        (field (name "SUPPLIER") "LCSC")
        (field (name "LCSC PART NAME") "热插拔底座连接器 键盘配件")
      )
      (libsource (lib "easyedapro") (part "CPG151101S11-16_C41430893"))
    )
    (comp (ref "U210")
      (value "CPG151101S11-16")
      (footprint "ProPrj_HTX-easyedapro:SMD_KEYBOARD-SW")
      (fields
        (field (name "MANUFACTURER PART") "CPG151101S11-16")
        (field (name "MANUFACTURER") "HanElectricity(瀚源)")
        (field (name "SUPPLIER PART") "C41430893")
        (field (name "SUPPLIER") "LCSC")
        (field (name "LCSC PART NAME") "热插拔底座连接器 键盘配件")
      )
      (libsource (lib "easyedapro") (part "CPG151101S11-16_C41430893"))
    )
    (comp (ref "U211")
      (value "CPG151101S11-16")
      (footprint "ProPrj_HTX-easyedapro:SMD_KEYBOARD-SW")
      (fields
        (field (name "MANUFACTURER PART") "CPG151101S11-16")
        (field (name "MANUFACTURER") "HanElectricity(瀚源)")
        (field (name "SUPPLIER PART") "C41430893")
        (field (name "SUPPLIER") "LCSC")
        (field (name "LCSC PART NAME") "热插拔底座连接器 键盘配件")
      )
      (libsource (lib "easyedapro") (part "CPG151101S11-16_C41430893"))
    )
    (comp (ref "U212")
      (value "CPG151101S11-16")
      (footprint "ProPrj_HTX-easyedapro:SMD_KEYBOARD-SW")
      (fields
        (field (name "MANUFACTURER PART") "CPG151101S11-16")
        (field (name "MANUFACTURER") "HanElectricity(瀚源)")
        (field (name "SUPPLIER PART") "C41430893")
        (field (name "SUPPLIER") "LCSC")
        (field (name "LCSC PART NAME") "热插拔底座连接器 键盘配件")
      )
      (libsource (lib "easyedapro") (part "CPG151101S11-16_C41430893"))
    )
    (comp (ref "U213")
      (value "CPG151101S11-16")
      (footprint "ProPrj_HTX-easyedapro:SMD_KEYBOARD-SW")
      (fields
        (field (name "MANUFACTURER PART") "CPG151101S11-16")
        (field (name "MANUFACTURER") "HanElectricity(瀚源)")
        (field (name "SUPPLIER PART") "C41430893")
        (field (name "SUPPLIER") "LCSC")
        (field (name "LCSC PART NAME") "热插拔底座连接器 键盘配件")
      )
      (libsource (lib "easyedapro") (part "CPG151101S11-16_C41430893"))
    )
    (comp (ref "U214")
      (value "CPG151101S11-16")
      (footprint "ProPrj_HTX-easyedapro:SMD_KEYBOARD-SW")
      (fields
        (field (name "MANUFACTURER PART") "CPG151101S11-16")
        (field (name "MANUFACTURER") "HanElectricity(瀚源)")
        (field (name "SUPPLIER PART") "C41430893")
        (field (name "SUPPLIER") "LCSC")
        (field (name "LCSC PART NAME") "热插拔底座连接器 键盘配件")
      )
      (libsource (lib "easyedapro") (part "CPG151101S11-16_C41430893"))
    )
    (comp (ref "U215")
      (value "CPG151101S11-16")
      (footprint "ProPrj_HTX-easyedapro:SMD_KEYBOARD-SW")
      (fields
        (field (name "MANUFACTURER PART") "CPG151101S11-16")
        (field (name "MANUFACTURER") "HanElectricity(瀚源)")
        (field (name "SUPPLIER PART") "C41430893")
        (field (name "SUPPLIER") "LCSC")
        (field (name "LCSC PART NAME") "热插拔底座连接器 键盘配件")
      )
      (libsource (lib "easyedapro") (part "CPG151101S11-16_C41430893"))
    )
  )
  (nets
    (net (code "1") (name "+5V") (class "Default")
      (node (ref "C100") (pin "2") (pinfunction "2_2") (pintype "passive"))
      (node (ref "C101") (pin "2") (pinfunction "2_2") (pintype "passive"))
      (node (ref "C102") (pin "2") (pinfunction "2_2") (pintype "passive"))
      (node (ref "C103") (pin "2") (pinfunction "2_2") (pintype "passive"))
      (node (ref "C104") (pin "2") (pinfunction "2_2") (pintype "passive"))
      (node (ref "C105") (pin "2") (pinfunction "2_2") (pintype "passive"))
      (node (ref "C106") (pin "2") (pinfunction "2_2") (pintype "passive"))
      (node (ref "C107") (pin "2") (pinfunction "2_2") (pintype "passive"))
      (node (ref "C108") (pin "2") (pinfunction "2_2") (pintype "passive"))
      (node (ref "C109") (pin "2") (pinfunction "2_2") (pintype "passive"))
      (node (ref "C110") (pin "2") (pinfunction "2_2") (pintype "passive"))
      (node (ref "C111") (pin "2") (pinfunction "2_2") (pintype "passive"))
      (node (ref "C112") (pin "2") (pinfunction "2_2") (pintype "passive"))
      (node (ref "C113") (pin "2") (pinfunction "2_2") (pintype "passive"))
      (node (ref "C114") (pin "2") (pinfunction "2_2") (pintype "passive"))
      (node (ref "C115") (pin "2") (pinfunction "2_2") (pintype "passive"))
      (node (ref "C116") (pin "2") (pinfunction "2_2") (pintype "passive"))
      (node (ref "C117") (pin "2") (pinfunction "2_2") (pintype "passive"))
      (node (ref "C118") (pin "2") (pinfunction "2_2") (pintype "passive"))
      (node (ref "C119") (pin "2") (pinfunction "2_2") (pintype "passive"))
      (node (ref "C120") (pin "2") (pinfunction "2_2") (pintype "passive"))
      (node (ref "C121") (pin "2") (pinfunction "2_2") (pintype "passive"))
      (node (ref "C122") (pin "2") (pinfunction "2_2") (pintype "passive"))
      (node (ref "C123") (pin "2") (pinfunction "2_2") (pintype "passive"))
      (node (ref "C124") (pin "2") (pinfunction "2_2") (pintype "passive"))
      (node (ref "C125") (pin "2") (pinfunction "2_2") (pintype "passive"))
      (node (ref "C126") (pin "2") (pinfunction "2_2") (pintype "passive"))
      (node (ref "C127") (pin "2") (pinfunction "2_2") (pintype "passive"))
      (node (ref "C128") (pin "2") (pinfunction "2_2") (pintype "passive"))
      (node (ref "C129") (pin "2") (pinfunction "2_2") (pintype "passive"))
      (node (ref "C130") (pin "2") (pinfunction "2_2") (pintype "passive"))
      (node (ref "C131") (pin "2") (pinfunction "2_2") (pintype "passive"))
      (node (ref "C132") (pin "2") (pinfunction "2_2") (pintype "passive"))
      (node (ref "C133") (pin "2") (pinfunction "2_2") (pintype "passive"))
      (node (ref "C134") (pin "2") (pinfunction "2_2") (pintype "passive"))
      (node (ref "C135") (pin "2") (pinfunction "2_2") (pintype "passive"))
      (node (ref "C136") (pin "2") (pinfunction "2_2") (pintype "passive"))
      (node (ref "C137") (pin "2") (pinfunction "2_2") (pintype "passive"))
      (node (ref "C138") (pin "2") (pinfunction "2_2") (pintype "passive"))
      (node (ref "C139") (pin "2") (pinfunction "2_2") (pintype "passive"))
      (node (ref "C140") (pin "2") (pinfunction "2_2") (pintype "passive"))
      (node (ref "C141") (pin "2") (pinfunction "2_2") (pintype "passive"))
      (node (ref "C142") (pin "2") (pinfunction "2_2") (pintype "passive"))
      (node (ref "C143") (pin "2") (pinfunction "2_2") (pintype "passive"))
      (node (ref "C144") (pin "2") (pinfunction "2_2") (pintype "passive"))
      (node (ref "C145") (pin "2") (pinfunction "2_2") (pintype "passive"))
      (node (ref "C146") (pin "2") (pinfunction "2_2") (pintype "passive"))
      (node (ref "C147") (pin "2") (pinfunction "2_2") (pintype "passive"))
      (node (ref "C148") (pin "2") (pinfunction "2_2") (pintype "passive"))
      (node (ref "C149") (pin "2") (pinfunction "2_2") (pintype "passive"))
      (node (ref "C150") (pin "2") (pinfunction "2_2") (pintype "passive"))
      (node (ref "C151") (pin "2") (pinfunction "2_2") (pintype "passive"))
      (node (ref "C152") (pin "2") (pinfunction "2_2") (pintype "passive"))
      (node (ref "C153") (pin "2") (pinfunction "2_2") (pintype "passive"))
      (node (ref "C154") (pin "2") (pinfunction "2_2") (pintype "passive"))
      (node (ref "C155") (pin "2") (pinfunction "2_2") (pintype "passive"))
      (node (ref "C156") (pin "2") (pinfunction "2_2") (pintype "passive"))
      (node (ref "U100") (pin "1") (pinfunction "VDD_1") (pintype "passive"))
      (node (ref "U101") (pin "1") (pinfunction "VDD_1") (pintype "passive"))
      (node (ref "U102") (pin "1") (pinfunction "VDD_1") (pintype "passive"))
      (node (ref "U103") (pin "1") (pinfunction "VDD_1") (pintype "passive"))
      (node (ref "U104") (pin "1") (pinfunction "VDD_1") (pintype "passive"))
      (node (ref "U105") (pin "1") (pinfunction "VDD_1") (pintype "passive"))
      (node (ref "U106") (pin "1") (pinfunction "VDD_1") (pintype "passive"))
      (node (ref "U107") (pin "1") (pinfunction "VDD_1") (pintype "passive"))
      (node (ref "U108") (pin "1") (pinfunction "VDD_1") (pintype "passive"))
      (node (ref "U109") (pin "1") (pinfunction "VDD_1") (pintype "passive"))
      (node (ref "U110") (pin "1") (pinfunction "VDD_1") (pintype "passive"))
      (node (ref "U111") (pin "1") (pinfunction "VDD_1") (pintype "passive"))
      (node (ref "U112") (pin "1") (pinfunction "VDD_1") (pintype "passive"))
      (node (ref "U113") (pin "1") (pinfunction "VDD_1") (pintype "passive"))
      (node (ref "U128") (pin "1") (pinfunction "VDD_1") (pintype "passive"))
      (node (ref "U129") (pin "1") (pinfunction "VDD_1") (pintype "passive"))
      (node (ref "U130") (pin "1") (pinfunction "VDD_1") (pintype "passive"))
      (node (ref "U131") (pin "1") (pinfunction "VDD_1") (pintype "passive"))
      (node (ref "U132") (pin "1") (pinfunction "VDD_1") (pintype "passive"))
      (node (ref "U133") (pin "1") (pinfunction "VDD_1") (pintype "passive"))
      (node (ref "U134") (pin "1") (pinfunction "VDD_1") (pintype "passive"))
      (node (ref "U135") (pin "1") (pinfunction "VDD_1") (pintype "passive"))
      (node (ref "U136") (pin "1") (pinfunction "VDD_1") (pintype "passive"))
      (node (ref "U137") (pin "1") (pinfunction "VDD_1") (pintype "passive"))
      (node (ref "U138") (pin "1") (pinfunction "VDD_1") (pintype "passive"))
      (node (ref "U139") (pin "1") (pinfunction "VDD_1") (pintype "passive"))
      (node (ref "U140") (pin "1") (pinfunction "VDD_1") (pintype "passive"))
      (node (ref "U141") (pin "1") (pinfunction "VDD_1") (pintype "passive"))
      (node (ref "U156") (pin "1") (pinfunction "VDD_1") (pintype "passive"))
      (node (ref "U157") (pin "1") (pinfunction "VDD_1") (pintype "passive"))
      (node (ref "U158") (pin "1") (pinfunction "VDD_1") (pintype "passive"))
      (node (ref "U159") (pin "1") (pinfunction "VDD_1") (pintype "passive"))
      (node (ref "U160") (pin "1") (pinfunction "VDD_1") (pintype "passive"))
      (node (ref "U161") (pin "1") (pinfunction "VDD_1") (pintype "passive"))
      (node (ref "U162") (pin "1") (pinfunction "VDD_1") (pintype "passive"))
      (node (ref "U163") (pin "1") (pinfunction "VDD_1") (pintype "passive"))
      (node (ref "U164") (pin "1") (pinfunction "VDD_1") (pintype "passive"))
      (node (ref "U165") (pin "1") (pinfunction "VDD_1") (pintype "passive"))
      (node (ref "U166") (pin "1") (pinfunction "VDD_1") (pintype "passive"))
      (node (ref "U167") (pin "1") (pinfunction "VDD_1") (pintype "passive"))
      (node (ref "U180") (pin "3") (pinfunction "VDD_3") (pintype "passive"))
      (node (ref "U181") (pin "3") (pinfunction "VDD_3") (pintype "passive"))
      (node (ref "U182") (pin "1") (pinfunction "VDD_1") (pintype "passive"))
      (node (ref "U183") (pin "1") (pinfunction "VDD_1") (pintype "passive"))
      (node (ref "U184") (pin "1") (pinfunction "VDD_1") (pintype "passive"))
      (node (ref "U185") (pin "1") (pinfunction "VDD_1") (pintype "passive"))
      (node (ref "U186") (pin "1") (pinfunction "VDD_1") (pintype "passive"))
      (node (ref "U187") (pin "1") (pinfunction "VDD_1") (pintype "passive"))
      (node (ref "U188") (pin "1") (pinfunction "VDD_1") (pintype "passive"))
      (node (ref "U189") (pin "1") (pinfunction "VDD_1") (pintype "passive"))
      (node (ref "U198") (pin "1") (pinfunction "VDD_1") (pintype "passive"))
      (node (ref "U199") (pin "1") (pinfunction "VDD_1") (pintype "passive"))
      (node (ref "U200") (pin "1") (pinfunction "VDD_1") (pintype "passive"))
      (node (ref "U201") (pin "1") (pinfunction "VDD_1") (pintype "passive"))
      (node (ref "U202") (pin "1") (pinfunction "VDD_1") (pintype "passive"))
      (node (ref "U203") (pin "1") (pinfunction "VDD_1") (pintype "passive"))
      (node (ref "U204") (pin "1") (pinfunction "VDD_1") (pintype "passive"))
      (node (ref "U205") (pin "1") (pinfunction "VDD_1") (pintype "passive"))
      (node (ref "U206") (pin "1") (pinfunction "VDD_1") (pintype "passive"))
    )
    (net (code "2") (name "/COL1") (class "Default")
      (node (ref "D100") (pin "1") (pinfunction "K_1") (pintype "passive"))
      (node (ref "D114") (pin "1") (pinfunction "K_1") (pintype "passive"))
      (node (ref "D128") (pin "1") (pinfunction "K_1") (pintype "passive"))
      (node (ref "D140") (pin "1") (pinfunction "C_1") (pintype "passive"))
      (node (ref "D150") (pin "1") (pinfunction "K_1") (pintype "passive"))
    )
    (net (code "3") (name "/COL2") (class "Default")
      (node (ref "D101") (pin "1") (pinfunction "K_1") (pintype "passive"))
      (node (ref "D115") (pin "1") (pinfunction "K_1") (pintype "passive"))
      (node (ref "D129") (pin "1") (pinfunction "K_1") (pintype "passive"))
    )
    (net (code "4") (name "/COL3") (class "Default")
      (node (ref "D102") (pin "1") (pinfunction "K_1") (pintype "passive"))
      (node (ref "D116") (pin "1") (pinfunction "K_1") (pintype "passive"))
      (node (ref "D130") (pin "1") (pinfunction "K_1") (pintype "passive"))
      (node (ref "D141") (pin "1") (pinfunction "C_1") (pintype "passive"))
      (node (ref "D151") (pin "1") (pinfunction "K_1") (pintype "passive"))
    )
    (net (code "5") (name "/COL4") (class "Default")
      (node (ref "D103") (pin "1") (pinfunction "K_1") (pintype "passive"))
      (node (ref "D117") (pin "1") (pinfunction "K_1") (pintype "passive"))
      (node (ref "D131") (pin "1") (pinfunction "K_1") (pintype "passive"))
      (node (ref "D142") (pin "1") (pinfunction "K_1") (pintype "passive"))
      (node (ref "D152") (pin "1") (pinfunction "K_1") (pintype "passive"))
    )
    (net (code "6") (name "/COL5") (class "Default")
      (node (ref "D104") (pin "1") (pinfunction "K_1") (pintype "passive"))
      (node (ref "D118") (pin "1") (pinfunction "K_1") (pintype "passive"))
    )
    (net (code "7") (name "/COL6") (class "Default")
      (node (ref "D105") (pin "1") (pinfunction "K_1") (pintype "passive"))
      (node (ref "D119") (pin "1") (pinfunction "K_1") (pintype "passive"))
      (node (ref "D132") (pin "1") (pinfunction "K_1") (pintype "passive"))
      (node (ref "D143") (pin "1") (pinfunction "K_1") (pintype "passive"))
      (node (ref "D153") (pin "1") (pinfunction "K_1") (pintype "passive"))
    )
    (net (code "8") (name "/COL7") (class "Default")
      (node (ref "D106") (pin "1") (pinfunction "K_1") (pintype "passive"))
      (node (ref "D120") (pin "1") (pinfunction "K_1") (pintype "passive"))
      (node (ref "D133") (pin "1") (pinfunction "K_1") (pintype "passive"))
      (node (ref "D144") (pin "1") (pinfunction "K_1") (pintype "passive"))
    )
    (net (code "9") (name "/COL8") (class "Default")
      (node (ref "D107") (pin "1") (pinfunction "K_1") (pintype "passive"))
      (node (ref "D121") (pin "1") (pinfunction "K_1") (pintype "passive"))
      (node (ref "D134") (pin "1") (pinfunction "K_1") (pintype "passive"))
      (node (ref "D145") (pin "1") (pinfunction "K_1") (pintype "passive"))
      (node (ref "D154") (pin "1") (pinfunction "K_1") (pintype "passive"))
    )
    (net (code "10") (name "/COL9") (class "Default")
      (node (ref "D108") (pin "1") (pinfunction "K_1") (pintype "passive"))
      (node (ref "D122") (pin "1") (pinfunction "K_1") (pintype "passive"))
      (node (ref "D135") (pin "1") (pinfunction "K_1") (pintype "passive"))
    )
    (net (code "11") (name "/COL10") (class "Default")
      (node (ref "D109") (pin "1") (pinfunction "K_1") (pintype "passive"))
      (node (ref "D123") (pin "1") (pinfunction "K_1") (pintype "passive"))
      (node (ref "D136") (pin "1") (pinfunction "K_1") (pintype "passive"))
      (node (ref "D146") (pin "1") (pinfunction "K_1") (pintype "passive"))
      (node (ref "D155") (pin "1") (pinfunction "K_1") (pintype "passive"))
    )
    (net (code "12") (name "/COL11") (class "Default")
      (node (ref "D110") (pin "1") (pinfunction "K_1") (pintype "passive"))
      (node (ref "D124") (pin "1") (pinfunction "K_1") (pintype "passive"))
      (node (ref "D137") (pin "1") (pinfunction "K_1") (pintype "passive"))
      (node (ref "D147") (pin "1") (pinfunction "K_1") (pintype "passive"))
      (node (ref "D156") (pin "1") (pinfunction "K_1") (pintype "passive"))
    )
    (net (code "13") (name "/COL12") (class "Default")
      (node (ref "D111") (pin "1") (pinfunction "K_1") (pintype "passive"))
      (node (ref "D125") (pin "1") (pinfunction "K_1") (pintype "passive"))
      (node (ref "D138") (pin "1") (pinfunction "K_1") (pintype "passive"))
      (node (ref "D148") (pin "1") (pinfunction "K_1") (pintype "passive"))
    )
    (net (code "14") (name "/COL13") (class "Default")
      (node (ref "D112") (pin "1") (pinfunction "K_1") (pintype "passive"))
      (node (ref "D126") (pin "1") (pinfunction "K_1") (pintype "passive"))
      (node (ref "D157") (pin "1") (pinfunction "K_1") (pintype "passive"))
    )
    (net (code "15") (name "/COL14") (class "Default")
      (node (ref "D113") (pin "1") (pinfunction "K_1") (pintype "passive"))
      (node (ref "D127") (pin "1") (pinfunction "K_1") (pintype "passive"))
      (node (ref "D139") (pin "1") (pinfunction "K_1") (pintype "passive"))
      (node (ref "D149") (pin "1") (pinfunction "K_1") (pintype "passive"))
      (node (ref "D158") (pin "1") (pinfunction "K_1") (pintype "passive"))
    )
    (net (code "16") (name "/ROW1") (class "Default")
      (node (ref "U114") (pin "1") (pinfunction "1_1") (pintype "passive"))
      (node (ref "U115") (pin "1") (pinfunction "1_1") (pintype "passive"))
      (node (ref "U116") (pin "1") (pinfunction "1_1") (pintype "passive"))
      (node (ref "U117") (pin "1") (pinfunction "1_1") (pintype "passive"))
      (node (ref "U118") (pin "1") (pinfunction "1_1") (pintype "passive"))
      (node (ref "U119") (pin "1") (pinfunction "1_1") (pintype "passive"))
      (node (ref "U120") (pin "1") (pinfunction "1_1") (pintype "passive"))
      (node (ref "U121") (pin "1") (pinfunction "1_1") (pintype "passive"))
      (node (ref "U122") (pin "1") (pinfunction "1_1") (pintype "passive"))
      (node (ref "U123") (pin "1") (pinfunction "1_1") (pintype "passive"))
      (node (ref "U124") (pin "1") (pinfunction "1_1") (pintype "passive"))
      (node (ref "U125") (pin "1") (pinfunction "1_1") (pintype "passive"))
      (node (ref "U126") (pin "1") (pinfunction "1_1") (pintype "passive"))
      (node (ref "U127") (pin "1") (pinfunction "1_1") (pintype "passive"))
    )
    (net (code "17") (name "/ROW2") (class "Default")
      (node (ref "U142") (pin "1") (pinfunction "1_1") (pintype "passive"))
      (node (ref "U143") (pin "1") (pinfunction "1_1") (pintype "passive"))
      (node (ref "U144") (pin "1") (pinfunction "1_1") (pintype "passive"))
      (node (ref "U145") (pin "1") (pinfunction "1_1") (pintype "passive"))
      (node (ref "U146") (pin "1") (pinfunction "1_1") (pintype "passive"))
      (node (ref "U147") (pin "1") (pinfunction "1_1") (pintype "passive"))
      (node (ref "U148") (pin "1") (pinfunction "1_1") (pintype "passive"))
      (node (ref "U149") (pin "1") (pinfunction "1_1") (pintype "passive"))
      (node (ref "U150") (pin "1") (pinfunction "1_1") (pintype "passive"))
      (node (ref "U151") (pin "1") (pinfunction "1_1") (pintype "passive"))
      (node (ref "U152") (pin "1") (pinfunction "1_1") (pintype "passive"))
      (node (ref "U153") (pin "1") (pinfunction "1_1") (pintype "passive"))
      (node (ref "U154") (pin "1") (pinfunction "1_1") (pintype "passive"))
      (node (ref "U155") (pin "1") (pinfunction "1_1") (pintype "passive"))
    )
    (net (code "18") (name "/ROW3") (class "Default")
      (node (ref "U168") (pin "1") (pinfunction "1_1") (pintype "passive"))
      (node (ref "U169") (pin "1") (pinfunction "1_1") (pintype "passive"))
      (node (ref "U170") (pin "1") (pinfunction "1_1") (pintype "passive"))
      (node (ref "U171") (pin "1") (pinfunction "1_1") (pintype "passive"))
      (node (ref "U172") (pin "1") (pinfunction "1_1") (pintype "passive"))
      (node (ref "U173") (pin "1") (pinfunction "1_1") (pintype "passive"))
      (node (ref "U174") (pin "1") (pinfunction "1_1") (pintype "passive"))
      (node (ref "U175") (pin "1") (pinfunction "1_1") (pintype "passive"))
      (node (ref "U176") (pin "1") (pinfunction "1_1") (pintype "passive"))
      (node (ref "U177") (pin "1") (pinfunction "1_1") (pintype "passive"))
      (node (ref "U178") (pin "1") (pinfunction "1_1") (pintype "passive"))
      (node (ref "U179") (pin "1") (pinfunction "1_1") (pintype "passive"))
    )
    (net (code "19") (name "/ROW4") (class "Default")
      (node (ref "SW100") (pin "2") (pinfunction "ON_2") (pintype "passive"))
      (node (ref "SW101") (pin "2") (pinfunction "ON_2") (pintype "passive"))
      (node (ref "U190") (pin "1") (pinfunction "1_1") (pintype "passive"))
      (node (ref "U191") (pin "1") (pinfunction "1_1") (pintype "passive"))
      (node (ref "U192") (pin "1") (pinfunction "1_1") (pintype "passive"))
      (node (ref "U193") (pin "1") (pinfunction "1_1") (pintype "passive"))
      (node (ref "U194") (pin "1") (pinfunction "1_1") (pintype "passive"))
      (node (ref "U195") (pin "1") (pinfunction "1_1") (pintype "passive"))
      (node (ref "U196") (pin "1") (pinfunction "1_1") (pintype "passive"))
      (node (ref "U197") (pin "1") (pinfunction "1_1") (pintype "passive"))
    )
    (net (code "20") (name "/ROW5") (class "Default")
      (node (ref "U207") (pin "1") (pinfunction "1_1") (pintype "passive"))
      (node (ref "U208") (pin "1") (pinfunction "1_1") (pintype "passive"))
      (node (ref "U209") (pin "1") (pinfunction "1_1") (pintype "passive"))
      (node (ref "U210") (pin "1") (pinfunction "1_1") (pintype "passive"))
      (node (ref "U211") (pin "1") (pinfunction "1_1") (pintype "passive"))
      (node (ref "U212") (pin "1") (pinfunction "1_1") (pintype "passive"))
      (node (ref "U213") (pin "1") (pinfunction "1_1") (pintype "passive"))
      (node (ref "U214") (pin "1") (pinfunction "1_1") (pintype "passive"))
      (node (ref "U215") (pin "1") (pinfunction "1_1") (pintype "passive"))
    )
    (net (code "21") (name "/WS2812_1") (class "Default")
      (node (ref "U100") (pin "4") (pinfunction "DIN_4") (pintype "passive"))
    )
    (net (code "22") (name "/WS2812_2") (class "Default")
      (node (ref "U113") (pin "2") (pinfunction "DOUT_2") (pintype "passive"))
      (node (ref "U128") (pin "4") (pinfunction "DIN_4") (pintype "passive"))
    )
    (net (code "23") (name "/WS2812_3") (class "Default")
      (node (ref "U141") (pin "2") (pinfunction "DOUT_2") (pintype "passive"))
      (node (ref "U156") (pin "4") (pinfunction "DIN_4") (pintype "passive"))
    )
    (net (code "24") (name "/WS2812_4") (class "Default")
      (node (ref "U167") (pin "2") (pinfunction "DOUT_2") (pintype "passive"))
      (node (ref "U180") (pin "2") (pinfunction "DI_2") (pintype "passive"))
    )
    (net (code "25") (name "/WS2812_5") (class "Default")
      (node (ref "U189") (pin "2") (pinfunction "DOUT_2") (pintype "passive"))
      (node (ref "U198") (pin "4") (pinfunction "DIN_4") (pintype "passive"))
    )
    (net (code "26") (name "GND") (class "Default")
      (node (ref "C100") (pin "1") (pinfunction "1_1") (pintype "passive"))
      (node (ref "C101") (pin "1") (pinfunction "1_1") (pintype "passive"))
      (node (ref "C102") (pin "1") (pinfunction "1_1") (pintype "passive"))
      (node (ref "C103") (pin "1") (pinfunction "1_1") (pintype "passive"))
      (node (ref "C104") (pin "1") (pinfunction "1_1") (pintype "passive"))
      (node (ref "C105") (pin "1") (pinfunction "1_1") (pintype "passive"))
      (node (ref "C106") (pin "1") (pinfunction "1_1") (pintype "passive"))
      (node (ref "C107") (pin "1") (pinfunction "1_1") (pintype "passive"))
      (node (ref "C108") (pin "1") (pinfunction "1_1") (pintype "passive"))
      (node (ref "C109") (pin "1") (pinfunction "1_1") (pintype "passive"))
      (node (ref "C110") (pin "1") (pinfunction "1_1") (pintype "passive"))
      (node (ref "C111") (pin "1") (pinfunction "1_1") (pintype "passive"))
      (node (ref "C112") (pin "1") (pinfunction "1_1") (pintype "passive"))
      (node (ref "C113") (pin "1") (pinfunction "1_1") (pintype "passive"))
      (node (ref "C114") (pin "1") (pinfunction "1_1") (pintype "passive"))
      (node (ref "C115") (pin "1") (pinfunction "1_1") (pintype "passive"))
      (node (ref "C116") (pin "1") (pinfunction "1_1") (pintype "passive"))
      (node (ref "C117") (pin "1") (pinfunction "1_1") (pintype "passive"))
      (node (ref "C118") (pin "1") (pinfunction "1_1") (pintype "passive"))
      (node (ref "C119") (pin "1") (pinfunction "1_1") (pintype "passive"))
      (node (ref "C120") (pin "1") (pinfunction "1_1") (pintype "passive"))
      (node (ref "C121") (pin "1") (pinfunction "1_1") (pintype "passive"))
      (node (ref "C122") (pin "1") (pinfunction "1_1") (pintype "passive"))
      (node (ref "C123") (pin "1") (pinfunction "1_1") (pintype "passive"))
      (node (ref "C124") (pin "1") (pinfunction "1_1") (pintype "passive"))
      (node (ref "C125") (pin "1") (pinfunction "1_1") (pintype "passive"))
      (node (ref "C126") (pin "1") (pinfunction "1_1") (pintype "passive"))
      (node (ref "C127") (pin "1") (pinfunction "1_1") (pintype "passive"))
      (node (ref "C128") (pin "1") (pinfunction "1_1") (pintype "passive"))
      (node (ref "C129") (pin "1") (pinfunction "1_1") (pintype "passive"))
      (node (ref "C130") (pin "1") (pinfunction "1_1") (pintype "passive"))
      (node (ref "C131") (pin "1") (pinfunction "1_1") (pintype "passive"))
      (node (ref "C132") (pin "1") (pinfunction "1_1") (pintype "passive"))
      (node (ref "C133") (pin "1") (pinfunction "1_1") (pintype "passive"))
      (node (ref "C134") (pin "1") (pinfunction "1_1") (pintype "passive"))
      (node (ref "C135") (pin "1") (pinfunction "1_1") (pintype "passive"))
      (node (ref "C136") (pin "1") (pinfunction "1_1") (pintype "passive"))
      (node (ref "C137") (pin "1") (pinfunction "1_1") (pintype "passive"))
      (node (ref "C138") (pin "1") (pinfunction "1_1") (pintype "passive"))
      (node (ref "C139") (pin "1") (pinfunction "1_1") (pintype "passive"))
      (node (ref "C140") (pin "1") (pinfunction "1_1") (pintype "passive"))
      (node (ref "C141") (pin "1") (pinfunction "1_1") (pintype "passive"))
      (node (ref "C142") (pin "1") (pinfunction "1_1") (pintype "passive"))
      (node (ref "C143") (pin "1") (pinfunction "1_1") (pintype "passive"))
      (node (ref "C144") (pin "1") (pinfunction "1_1") (pintype "passive"))
      (node (ref "C145") (pin "1") (pinfunction "1_1") (pintype "passive"))
      (node (ref "C146") (pin "1") (pinfunction "1_1") (pintype "passive"))
      (node (ref "C147") (pin "1") (pinfunction "1_1") (pintype "passive"))
      (node (ref "C148") (pin "1") (pinfunction "1_1") (pintype "passive"))
      (node (ref "C149") (pin "1") (pinfunction "1_1") (pintype "passive"))
      (node (ref "C150") (pin "1") (pinfunction "1_1") (pintype "passive"))
      (node (ref "C151") (pin "1") (pinfunction "1_1") (pintype "passive"))
      (node (ref "C152") (pin "1") (pinfunction "1_1") (pintype "passive"))
      (node (ref "C153") (pin "1") (pinfunction "1_1") (pintype "passive"))
      (node (ref "C154") (pin "1") (pinfunction "1_1") (pintype "passive"))
      (node (ref "C155") (pin "1") (pinfunction "1_1") (pintype "passive"))
      (node (ref "C156") (pin "1") (pinfunction "1_1") (pintype "passive"))
      (node (ref "U100") (pin "3") (pinfunction "GND_3") (pintype "passive"))
      (node (ref "U101") (pin "3") (pinfunction "GND_3") (pintype "passive"))
      (node (ref "U102") (pin "3") (pinfunction "GND_3") (pintype "passive"))
      (node (ref "U103") (pin "3") (pinfunction "GND_3") (pintype "passive"))
      (node (ref "U104") (pin "3") (pinfunction "GND_3") (pintype "passive"))
      (node (ref "U105") (pin "3") (pinfunction "GND_3") (pintype "passive"))
      (node (ref "U106") (pin "3") (pinfunction "GND_3") (pintype "passive"))
      (node (ref "U107") (pin "3") (pinfunction "GND_3") (pintype "passive"))
      (node (ref "U108") (pin "3") (pinfunction "GND_3") (pintype "passive"))
      (node (ref "U109") (pin "3") (pinfunction "GND_3") (pintype "passive"))
      (node (ref "U110") (pin "3") (pinfunction "GND_3") (pintype "passive"))
      (node (ref "U111") (pin "3") (pinfunction "GND_3") (pintype "passive"))
      (node (ref "U112") (pin "3") (pinfunction "GND_3") (pintype "passive"))
      (node (ref "U113") (pin "3") (pinfunction "GND_3") (pintype "passive"))
      (node (ref "U128") (pin "3") (pinfunction "GND_3") (pintype "passive"))
      (node (ref "U129") (pin "3") (pinfunction "GND_3") (pintype "passive"))
      (node (ref "U130") (pin "3") (pinfunction "GND_3") (pintype "passive"))
      (node (ref "U131") (pin "3") (pinfunction "GND_3") (pintype "passive"))
      (node (ref "U132") (pin "3") (pinfunction "GND_3") (pintype "passive"))
      (node (ref "U133") (pin "3") (pinfunction "GND_3") (pintype "passive"))
      (node (ref "U134") (pin "3") (pinfunction "GND_3") (pintype "passive"))
      (node (ref "U135") (pin "3") (pinfunction "GND_3") (pintype "passive"))
      (node (ref "U136") (pin "3") (pinfunction "GND_3") (pintype "passive"))
      (node (ref "U137") (pin "3") (pinfunction "GND_3") (pintype "passive"))
      (node (ref "U138") (pin "3") (pinfunction "GND_3") (pintype "passive"))
      (node (ref "U139") (pin "3") (pinfunction "GND_3") (pintype "passive"))
      (node (ref "U140") (pin "3") (pinfunction "GND_3") (pintype "passive"))
      (node (ref "U141") (pin "3") (pinfunction "GND_3") (pintype "passive"))
      (node (ref "U156") (pin "3") (pinfunction "GND_3") (pintype "passive"))
      (node (ref "U157") (pin "3") (pinfunction "GND_3") (pintype "passive"))
      (node (ref "U158") (pin "3") (pinfunction "GND_3") (pintype "passive"))
      (node (ref "U159") (pin "3") (pinfunction "GND_3") (pintype "passive"))
      (node (ref "U160") (pin "3") (pinfunction "GND_3") (pintype "passive"))
      (node (ref "U161") (pin "3") (pinfunction "GND_3") (pintype "passive"))
      (node (ref "U162") (pin "3") (pinfunction "GND_3") (pintype "passive"))
      (node (ref "U163") (pin "3") (pinfunction "GND_3") (pintype "passive"))
      (node (ref "U164") (pin "3") (pinfunction "GND_3") (pintype "passive"))
      (node (ref "U165") (pin "3") (pinfunction "GND_3") (pintype "passive"))
      (node (ref "U166") (pin "3") (pinfunction "GND_3") (pintype "passive"))
      (node (ref "U167") (pin "3") (pinfunction "GND_3") (pintype "passive"))
      (node (ref "U180") (pin "1") (pinfunction "GND_1") (pintype "passive"))
      (node (ref "U181") (pin "1") (pinfunction "GND_1") (pintype "passive"))
      (node (ref "U182") (pin "3") (pinfunction "GND_3") (pintype "passive"))
      (node (ref "U183") (pin "3") (pinfunction "GND_3") (pintype "passive"))
      (node (ref "U184") (pin "3") (pinfunction "GND_3") (pintype "passive"))
      (node (ref "U185") (pin "3") (pinfunction "GND_3") (pintype "passive"))
      (node (ref "U186") (pin "3") (pinfunction "GND_3") (pintype "passive"))
      (node (ref "U187") (pin "3") (pinfunction "GND_3") (pintype "passive"))
      (node (ref "U188") (pin "3") (pinfunction "GND_3") (pintype "passive"))
      (node (ref "U189") (pin "3") (pinfunction "GND_3") (pintype "passive"))
      (node (ref "U198") (pin "3") (pinfunction "GND_3") (pintype "passive"))
      (node (ref "U199") (pin "3") (pinfunction "GND_3") (pintype "passive"))
      (node (ref "U200") (pin "3") (pinfunction "GND_3") (pintype "passive"))
      (node (ref "U201") (pin "3") (pinfunction "GND_3") (pintype "passive"))
      (node (ref "U202") (pin "3") (pinfunction "GND_3") (pintype "passive"))
      (node (ref "U203") (pin "3") (pinfunction "GND_3") (pintype "passive"))
      (node (ref "U204") (pin "3") (pinfunction "GND_3") (pintype "passive"))
      (node (ref "U205") (pin "3") (pinfunction "GND_3") (pintype "passive"))
      (node (ref "U206") (pin "3") (pinfunction "GND_3") (pintype "passive"))
    )
    (net (code "27") (name "Net-(D100-A)") (class "Default")
      (node (ref "D100") (pin "2") (pinfunction "A_2") (pintype "passive"))
      (node (ref "U114") (pin "2") (pinfunction "2_2") (pintype "passive"))
    )
    (net (code "28") (name "Net-(D101-A)") (class "Default")
      (node (ref "D101") (pin "2") (pinfunction "A_2") (pintype "passive"))
      (node (ref "U115") (pin "2") (pinfunction "2_2") (pintype "passive"))
    )
    (net (code "29") (name "Net-(D102-A)") (class "Default")
      (node (ref "D102") (pin "2") (pinfunction "A_2") (pintype "passive"))
      (node (ref "U116") (pin "2") (pinfunction "2_2") (pintype "passive"))
    )
    (net (code "30") (name "Net-(D103-A)") (class "Default")
      (node (ref "D103") (pin "2") (pinfunction "A_2") (pintype "passive"))
      (node (ref "U117") (pin "2") (pinfunction "2_2") (pintype "passive"))
    )
    (net (code "31") (name "Net-(D104-A)") (class "Default")
      (node (ref "D104") (pin "2") (pinfunction "A_2") (pintype "passive"))
      (node (ref "U118") (pin "2") (pinfunction "2_2") (pintype "passive"))
    )
    (net (code "32") (name "Net-(D105-A)") (class "Default")
      (node (ref "D105") (pin "2") (pinfunction "A_2") (pintype "passive"))
      (node (ref "U119") (pin "2") (pinfunction "2_2") (pintype "passive"))
    )
    (net (code "33") (name "Net-(D106-A)") (class "Default")
      (node (ref "D106") (pin "2") (pinfunction "A_2") (pintype "passive"))
      (node (ref "U120") (pin "2") (pinfunction "2_2") (pintype "passive"))
    )
    (net (code "34") (name "Net-(D107-A)") (class "Default")
      (node (ref "D107") (pin "2") (pinfunction "A_2") (pintype "passive"))
      (node (ref "U121") (pin "2") (pinfunction "2_2") (pintype "passive"))
    )
    (net (code "35") (name "Net-(D108-A)") (class "Default")
      (node (ref "D108") (pin "2") (pinfunction "A_2") (pintype "passive"))
      (node (ref "U122") (pin "2") (pinfunction "2_2") (pintype "passive"))
    )
    (net (code "36") (name "Net-(D109-A)") (class "Default")
      (node (ref "D109") (pin "2") (pinfunction "A_2") (pintype "passive"))
      (node (ref "U123") (pin "2") (pinfunction "2_2") (pintype "passive"))
    )
    (net (code "37") (name "Net-(D110-A)") (class "Default")
      (node (ref "D110") (pin "2") (pinfunction "A_2") (pintype "passive"))
      (node (ref "U124") (pin "2") (pinfunction "2_2") (pintype "passive"))
    )
    (net (code "38") (name "Net-(D111-A)") (class "Default")
      (node (ref "D111") (pin "2") (pinfunction "A_2") (pintype "passive"))
      (node (ref "U125") (pin "2") (pinfunction "2_2") (pintype "passive"))
    )
    (net (code "39") (name "Net-(D112-A)") (class "Default")
      (node (ref "D112") (pin "2") (pinfunction "A_2") (pintype "passive"))
      (node (ref "U126") (pin "2") (pinfunction "2_2") (pintype "passive"))
    )
    (net (code "40") (name "Net-(D113-A)") (class "Default")
      (node (ref "D113") (pin "2") (pinfunction "A_2") (pintype "passive"))
      (node (ref "U127") (pin "2") (pinfunction "2_2") (pintype "passive"))
    )
    (net (code "41") (name "Net-(D114-A)") (class "Default")
      (node (ref "D114") (pin "2") (pinfunction "A_2") (pintype "passive"))
      (node (ref "U142") (pin "2") (pinfunction "2_2") (pintype "passive"))
    )
    (net (code "42") (name "Net-(D115-A)") (class "Default")
      (node (ref "D115") (pin "2") (pinfunction "A_2") (pintype "passive"))
      (node (ref "U143") (pin "2") (pinfunction "2_2") (pintype "passive"))
    )
    (net (code "43") (name "Net-(D116-A)") (class "Default")
      (node (ref "D116") (pin "2") (pinfunction "A_2") (pintype "passive"))
      (node (ref "U144") (pin "2") (pinfunction "2_2") (pintype "passive"))
    )
    (net (code "44") (name "Net-(D117-A)") (class "Default")
      (node (ref "D117") (pin "2") (pinfunction "A_2") (pintype "passive"))
      (node (ref "U145") (pin "2") (pinfunction "2_2") (pintype "passive"))
    )
    (net (code "45") (name "Net-(D118-A)") (class "Default")
      (node (ref "D118") (pin "2") (pinfunction "A_2") (pintype "passive"))
      (node (ref "U146") (pin "2") (pinfunction "2_2") (pintype "passive"))
    )
    (net (code "46") (name "Net-(D119-A)") (class "Default")
      (node (ref "D119") (pin "2") (pinfunction "A_2") (pintype "passive"))
      (node (ref "U147") (pin "2") (pinfunction "2_2") (pintype "passive"))
    )
    (net (code "47") (name "Net-(D120-A)") (class "Default")
      (node (ref "D120") (pin "2") (pinfunction "A_2") (pintype "passive"))
      (node (ref "U148") (pin "2") (pinfunction "2_2") (pintype "passive"))
    )
    (net (code "48") (name "Net-(D121-A)") (class "Default")
      (node (ref "D121") (pin "2") (pinfunction "A_2") (pintype "passive"))
      (node (ref "U149") (pin "2") (pinfunction "2_2") (pintype "passive"))
    )
    (net (code "49") (name "Net-(D122-A)") (class "Default")
      (node (ref "D122") (pin "2") (pinfunction "A_2") (pintype "passive"))
      (node (ref "U150") (pin "2") (pinfunction "2_2") (pintype "passive"))
    )
    (net (code "50") (name "Net-(D123-A)") (class "Default")
      (node (ref "D123") (pin "2") (pinfunction "A_2") (pintype "passive"))
      (node (ref "U151") (pin "2") (pinfunction "2_2") (pintype "passive"))
    )
    (net (code "51") (name "Net-(D124-A)") (class "Default")
      (node (ref "D124") (pin "2") (pinfunction "A_2") (pintype "passive"))
      (node (ref "U152") (pin "2") (pinfunction "2_2") (pintype "passive"))
    )
    (net (code "52") (name "Net-(D125-A)") (class "Default")
      (node (ref "D125") (pin "2") (pinfunction "A_2") (pintype "passive"))
      (node (ref "U153") (pin "2") (pinfunction "2_2") (pintype "passive"))
    )
    (net (code "53") (name "Net-(D126-A)") (class "Default")
      (node (ref "D126") (pin "2") (pinfunction "A_2") (pintype "passive"))
      (node (ref "U154") (pin "2") (pinfunction "2_2") (pintype "passive"))
    )
    (net (code "54") (name "Net-(D127-A)") (class "Default")
      (node (ref "D127") (pin "2") (pinfunction "A_2") (pintype "passive"))
      (node (ref "U155") (pin "2") (pinfunction "2_2") (pintype "passive"))
    )
    (net (code "55") (name "Net-(D128-A)") (class "Default")
      (node (ref "D128") (pin "2") (pinfunction "A_2") (pintype "passive"))
      (node (ref "U168") (pin "2") (pinfunction "2_2") (pintype "passive"))
    )
    (net (code "56") (name "Net-(D129-A)") (class "Default")
      (node (ref "D129") (pin "2") (pinfunction "A_2") (pintype "passive"))
      (node (ref "U169") (pin "2") (pinfunction "2_2") (pintype "passive"))
    )
    (net (code "57") (name "Net-(D130-A)") (class "Default")
      (node (ref "D130") (pin "2") (pinfunction "A_2") (pintype "passive"))
      (node (ref "U170") (pin "2") (pinfunction "2_2") (pintype "passive"))
    )
    (net (code "58") (name "Net-(D131-A)") (class "Default")
      (node (ref "D131") (pin "2") (pinfunction "A_2") (pintype "passive"))
      (node (ref "U171") (pin "2") (pinfunction "2_2") (pintype "passive"))
    )
    (net (code "59") (name "Net-(D132-A)") (class "Default")
      (node (ref "D132") (pin "2") (pinfunction "A_2") (pintype "passive"))
      (node (ref "U172") (pin "2") (pinfunction "2_2") (pintype "passive"))
    )
    (net (code "60") (name "Net-(D133-A)") (class "Default")
      (node (ref "D133") (pin "2") (pinfunction "A_2") (pintype "passive"))
      (node (ref "U173") (pin "2") (pinfunction "2_2") (pintype "passive"))
    )
    (net (code "61") (name "Net-(D134-A)") (class "Default")
      (node (ref "D134") (pin "2") (pinfunction "A_2") (pintype "passive"))
      (node (ref "U174") (pin "2") (pinfunction "2_2") (pintype "passive"))
    )
    (net (code "62") (name "Net-(D135-A)") (class "Default")
      (node (ref "D135") (pin "2") (pinfunction "A_2") (pintype "passive"))
      (node (ref "U175") (pin "2") (pinfunction "2_2") (pintype "passive"))
    )
    (net (code "63") (name "Net-(D136-A)") (class "Default")
      (node (ref "D136") (pin "2") (pinfunction "A_2") (pintype "passive"))
      (node (ref "U176") (pin "2") (pinfunction "2_2") (pintype "passive"))
    )
    (net (code "64") (name "Net-(D137-A)") (class "Default")
      (node (ref "D137") (pin "2") (pinfunction "A_2") (pintype "passive"))
      (node (ref "U177") (pin "2") (pinfunction "2_2") (pintype "passive"))
    )
    (net (code "65") (name "Net-(D138-A)") (class "Default")
      (node (ref "D138") (pin "2") (pinfunction "A_2") (pintype "passive"))
      (node (ref "U178") (pin "2") (pinfunction "2_2") (pintype "passive"))
    )
    (net (code "66") (name "Net-(D139-A)") (class "Default")
      (node (ref "D139") (pin "2") (pinfunction "A_2") (pintype "passive"))
      (node (ref "U179") (pin "2") (pinfunction "2_2") (pintype "passive"))
    )
    (net (code "67") (name "Net-(D140-A)") (class "Default")
      (node (ref "D140") (pin "2") (pinfunction "A_2") (pintype "passive"))
      (node (ref "SW100") (pin "3") (pinfunction "NC_3") (pintype "passive"))
    )
    (net (code "68") (name "Net-(D141-A)") (class "Default")
      (node (ref "D141") (pin "2") (pinfunction "A_2") (pintype "passive"))
      (node (ref "SW101") (pin "3") (pinfunction "NC_3") (pintype "passive"))
    )
    (net (code "69") (name "Net-(D142-A)") (class "Default")
      (node (ref "D142") (pin "2") (pinfunction "A_2") (pintype "passive"))
      (node (ref "U190") (pin "2") (pinfunction "2_2") (pintype "passive"))
    )
    (net (code "70") (name "Net-(D143-A)") (class "Default")
      (node (ref "D143") (pin "2") (pinfunction "A_2") (pintype "passive"))
      (node (ref "U191") (pin "2") (pinfunction "2_2") (pintype "passive"))
    )
    (net (code "71") (name "Net-(D144-A)") (class "Default")
      (node (ref "D144") (pin "2") (pinfunction "A_2") (pintype "passive"))
      (node (ref "U192") (pin "2") (pinfunction "2_2") (pintype "passive"))
    )
    (net (code "72") (name "Net-(D145-A)") (class "Default")
      (node (ref "D145") (pin "2") (pinfunction "A_2") (pintype "passive"))
      (node (ref "U193") (pin "2") (pinfunction "2_2") (pintype "passive"))
    )
    (net (code "73") (name "Net-(D146-A)") (class "Default")
      (node (ref "D146") (pin "2") (pinfunction "A_2") (pintype "passive"))
      (node (ref "U194") (pin "2") (pinfunction "2_2") (pintype "passive"))
    )
    (net (code "74") (name "Net-(D147-A)") (class "Default")
      (node (ref "D147") (pin "2") (pinfunction "A_2") (pintype "passive"))
      (node (ref "U195") (pin "2") (pinfunction "2_2") (pintype "passive"))
    )
    (net (code "75") (name "Net-(D148-A)") (class "Default")
      (node (ref "D148") (pin "2") (pinfunction "A_2") (pintype "passive"))
      (node (ref "U196") (pin "2") (pinfunction "2_2") (pintype "passive"))
    )
    (net (code "76") (name "Net-(D149-A)") (class "Default")
      (node (ref "D149") (pin "2") (pinfunction "A_2") (pintype "passive"))
      (node (ref "U197") (pin "2") (pinfunction "2_2") (pintype "passive"))
    )
    (net (code "77") (name "Net-(D150-A)") (class "Default")
      (node (ref "D150") (pin "2") (pinfunction "A_2") (pintype "passive"))
      (node (ref "U207") (pin "2") (pinfunction "2_2") (pintype "passive"))
    )
    (net (code "78") (name "Net-(D151-A)") (class "Default")
      (node (ref "D151") (pin "2") (pinfunction "A_2") (pintype "passive"))
      (node (ref "U208") (pin "2") (pinfunction "2_2") (pintype "passive"))
    )
    (net (code "79") (name "Net-(D152-A)") (class "Default")
      (node (ref "D152") (pin "2") (pinfunction "A_2") (pintype "passive"))
      (node (ref "U209") (pin "2") (pinfunction "2_2") (pintype "passive"))
    )
    (net (code "80") (name "Net-(D153-A)") (class "Default")
      (node (ref "D153") (pin "2") (pinfunction "A_2") (pintype "passive"))
      (node (ref "U210") (pin "2") (pinfunction "2_2") (pintype "passive"))
    )
    (net (code "81") (name "Net-(D154-A)") (class "Default")
      (node (ref "D154") (pin "2") (pinfunction "A_2") (pintype "passive"))
      (node (ref "U211") (pin "2") (pinfunction "2_2") (pintype "passive"))
    )
    (net (code "82") (name "Net-(D155-A)") (class "Default")
      (node (ref "D155") (pin "2") (pinfunction "A_2") (pintype "passive"))
      (node (ref "U212") (pin "2") (pinfunction "2_2") (pintype "passive"))
    )
    (net (code "83") (name "Net-(D156-A)") (class "Default")
      (node (ref "D156") (pin "2") (pinfunction "A_2") (pintype "passive"))
      (node (ref "U213") (pin "2") (pinfunction "2_2") (pintype "passive"))
    )
    (net (code "84") (name "Net-(D157-A)") (class "Default")
      (node (ref "D157") (pin "2") (pinfunction "A_2") (pintype "passive"))
      (node (ref "U214") (pin "2") (pinfunction "2_2") (pintype "passive"))
    )
    (net (code "85") (name "Net-(D158-A)") (class "Default")
      (node (ref "D158") (pin "2") (pinfunction "A_2") (pintype "passive"))
      (node (ref "U215") (pin "2") (pinfunction "2_2") (pintype "passive"))
    )
    (net (code "86") (name "Net-(U100-DOUT)") (class "Default")
      (node (ref "U100") (pin "2") (pinfunction "DOUT_2") (pintype "passive"))
      (node (ref "U101") (pin "4") (pinfunction "DIN_4") (pintype "passive"))
    )
    (net (code "87") (name "Net-(U101-DOUT)") (class "Default")
      (node (ref "U101") (pin "2") (pinfunction "DOUT_2") (pintype "passive"))
      (node (ref "U102") (pin "4") (pinfunction "DIN_4") (pintype "passive"))
    )
    (net (code "88") (name "Net-(U102-DOUT)") (class "Default")
      (node (ref "U102") (pin "2") (pinfunction "DOUT_2") (pintype "passive"))
      (node (ref "U103") (pin "4") (pinfunction "DIN_4") (pintype "passive"))
    )
    (net (code "89") (name "Net-(U103-DOUT)") (class "Default")
      (node (ref "U103") (pin "2") (pinfunction "DOUT_2") (pintype "passive"))
      (node (ref "U104") (pin "4") (pinfunction "DIN_4") (pintype "passive"))
    )
    (net (code "90") (name "Net-(U104-DOUT)") (class "Default")
      (node (ref "U104") (pin "2") (pinfunction "DOUT_2") (pintype "passive"))
      (node (ref "U105") (pin "4") (pinfunction "DIN_4") (pintype "passive"))
    )
    (net (code "91") (name "Net-(U105-DOUT)") (class "Default")
      (node (ref "U105") (pin "2") (pinfunction "DOUT_2") (pintype "passive"))
      (node (ref "U106") (pin "4") (pinfunction "DIN_4") (pintype "passive"))
    )
    (net (code "92") (name "Net-(U106-DOUT)") (class "Default")
      (node (ref "U106") (pin "2") (pinfunction "DOUT_2") (pintype "passive"))
      (node (ref "U107") (pin "4") (pinfunction "DIN_4") (pintype "passive"))
    )
    (net (code "93") (name "Net-(U107-DOUT)") (class "Default")
      (node (ref "U107") (pin "2") (pinfunction "DOUT_2") (pintype "passive"))
      (node (ref "U108") (pin "4") (pinfunction "DIN_4") (pintype "passive"))
    )
    (net (code "94") (name "Net-(U108-DOUT)") (class "Default")
      (node (ref "U108") (pin "2") (pinfunction "DOUT_2") (pintype "passive"))
      (node (ref "U109") (pin "4") (pinfunction "DIN_4") (pintype "passive"))
    )
    (net (code "95") (name "Net-(U109-DOUT)") (class "Default")
      (node (ref "U109") (pin "2") (pinfunction "DOUT_2") (pintype "passive"))
      (node (ref "U110") (pin "4") (pinfunction "DIN_4") (pintype "passive"))
    )
    (net (code "96") (name "Net-(U110-DOUT)") (class "Default")
      (node (ref "U110") (pin "2") (pinfunction "DOUT_2") (pintype "passive"))
      (node (ref "U111") (pin "4") (pinfunction "DIN_4") (pintype "passive"))
    )
    (net (code "97") (name "Net-(U111-DOUT)") (class "Default")
      (node (ref "U111") (pin "2") (pinfunction "DOUT_2") (pintype "passive"))
      (node (ref "U112") (pin "4") (pinfunction "DIN_4") (pintype "passive"))
    )
    (net (code "98") (name "Net-(U112-DOUT)") (class "Default")
      (node (ref "U112") (pin "2") (pinfunction "DOUT_2") (pintype "passive"))
      (node (ref "U113") (pin "4") (pinfunction "DIN_4") (pintype "passive"))
    )
    (net (code "99") (name "Net-(U128-DOUT)") (class "Default")
      (node (ref "U128") (pin "2") (pinfunction "DOUT_2") (pintype "passive"))
      (node (ref "U129") (pin "4") (pinfunction "DIN_4") (pintype "passive"))
    )
    (net (code "100") (name "Net-(U129-DOUT)") (class "Default")
      (node (ref "U129") (pin "2") (pinfunction "DOUT_2") (pintype "passive"))
      (node (ref "U130") (pin "4") (pinfunction "DIN_4") (pintype "passive"))
    )
    (net (code "101") (name "Net-(U130-DOUT)") (class "Default")
      (node (ref "U130") (pin "2") (pinfunction "DOUT_2") (pintype "passive"))
      (node (ref "U131") (pin "4") (pinfunction "DIN_4") (pintype "passive"))
    )
    (net (code "102") (name "Net-(U131-DOUT)") (class "Default")
      (node (ref "U131") (pin "2") (pinfunction "DOUT_2") (pintype "passive"))
      (node (ref "U132") (pin "4") (pinfunction "DIN_4") (pintype "passive"))
    )
    (net (code "103") (name "Net-(U132-DOUT)") (class "Default")
      (node (ref "U132") (pin "2") (pinfunction "DOUT_2") (pintype "passive"))
      (node (ref "U133") (pin "4") (pinfunction "DIN_4") (pintype "passive"))
    )
    (net (code "104") (name "Net-(U133-DOUT)") (class "Default")
      (node (ref "U133") (pin "2") (pinfunction "DOUT_2") (pintype "passive"))
      (node (ref "U134") (pin "4") (pinfunction "DIN_4") (pintype "passive"))
    )
    (net (code "105") (name "Net-(U134-DOUT)") (class "Default")
      (node (ref "U134") (pin "2") (pinfunction "DOUT_2") (pintype "passive"))
      (node (ref "U135") (pin "4") (pinfunction "DIN_4") (pintype "passive"))
    )
    (net (code "106") (name "Net-(U135-DOUT)") (class "Default")
      (node (ref "U135") (pin "2") (pinfunction "DOUT_2") (pintype "passive"))
      (node (ref "U136") (pin "4") (pinfunction "DIN_4") (pintype "passive"))
    )
    (net (code "107") (name "Net-(U136-DOUT)") (class "Default")
      (node (ref "U136") (pin "2") (pinfunction "DOUT_2") (pintype "passive"))
      (node (ref "U137") (pin "4") (pinfunction "DIN_4") (pintype "passive"))
    )
    (net (code "108") (name "Net-(U137-DOUT)") (class "Default")
      (node (ref "U137") (pin "2") (pinfunction "DOUT_2") (pintype "passive"))
      (node (ref "U138") (pin "4") (pinfunction "DIN_4") (pintype "passive"))
    )
    (net (code "109") (name "Net-(U138-DOUT)") (class "Default")
      (node (ref "U138") (pin "2") (pinfunction "DOUT_2") (pintype "passive"))
      (node (ref "U139") (pin "4") (pinfunction "DIN_4") (pintype "passive"))
    )
    (net (code "110") (name "Net-(U139-DOUT)") (class "Default")
      (node (ref "U139") (pin "2") (pinfunction "DOUT_2") (pintype "passive"))
      (node (ref "U140") (pin "4") (pinfunction "DIN_4") (pintype "passive"))
    )
    (net (code "111") (name "Net-(U140-DOUT)") (class "Default")
      (node (ref "U140") (pin "2") (pinfunction "DOUT_2") (pintype "passive"))
      (node (ref "U141") (pin "4") (pinfunction "DIN_4") (pintype "passive"))
    )
    (net (code "112") (name "Net-(U156-DOUT)") (class "Default")
      (node (ref "U156") (pin "2") (pinfunction "DOUT_2") (pintype "passive"))
      (node (ref "U157") (pin "4") (pinfunction "DIN_4") (pintype "passive"))
    )
    (net (code "113") (name "Net-(U157-DOUT)") (class "Default")
      (node (ref "U157") (pin "2") (pinfunction "DOUT_2") (pintype "passive"))
      (node (ref "U158") (pin "4") (pinfunction "DIN_4") (pintype "passive"))
    )
    (net (code "114") (name "Net-(U158-DOUT)") (class "Default")
      (node (ref "U158") (pin "2") (pinfunction "DOUT_2") (pintype "passive"))
      (node (ref "U159") (pin "4") (pinfunction "DIN_4") (pintype "passive"))
    )
    (net (code "115") (name "Net-(U159-DOUT)") (class "Default")
      (node (ref "U159") (pin "2") (pinfunction "DOUT_2") (pintype "passive"))
      (node (ref "U160") (pin "4") (pinfunction "DIN_4") (pintype "passive"))
    )
    (net (code "116") (name "Net-(U160-DOUT)") (class "Default")
      (node (ref "U160") (pin "2") (pinfunction "DOUT_2") (pintype "passive"))
      (node (ref "U161") (pin "4") (pinfunction "DIN_4") (pintype "passive"))
    )
    (net (code "117") (name "Net-(U161-DOUT)") (class "Default")
      (node (ref "U161") (pin "2") (pinfunction "DOUT_2") (pintype "passive"))
      (node (ref "U162") (pin "4") (pinfunction "DIN_4") (pintype "passive"))
    )
    (net (code "118") (name "Net-(U162-DOUT)") (class "Default")
      (node (ref "U162") (pin "2") (pinfunction "DOUT_2") (pintype "passive"))
      (node (ref "U163") (pin "4") (pinfunction "DIN_4") (pintype "passive"))
    )
    (net (code "119") (name "Net-(U163-DOUT)") (class "Default")
      (node (ref "U163") (pin "2") (pinfunction "DOUT_2") (pintype "passive"))
      (node (ref "U164") (pin "4") (pinfunction "DIN_4") (pintype "passive"))
    )
    (net (code "120") (name "Net-(U164-DOUT)") (class "Default")
      (node (ref "U164") (pin "2") (pinfunction "DOUT_2") (pintype "passive"))
      (node (ref "U165") (pin "4") (pinfunction "DIN_4") (pintype "passive"))
    )
    (net (code "121") (name "Net-(U165-DOUT)") (class "Default")
      (node (ref "U165") (pin "2") (pinfunction "DOUT_2") (pintype "passive"))
      (node (ref "U166") (pin "4") (pinfunction "DIN_4") (pintype "passive"))
    )
    (net (code "122") (name "Net-(U166-DOUT)") (class "Default")
      (node (ref "U166") (pin "2") (pinfunction "DOUT_2") (pintype "passive"))
      (node (ref "U167") (pin "4") (pinfunction "DIN_4") (pintype "passive"))
    )
    (net (code "123") (name "Net-(U180-DO)") (class "Default")
      (node (ref "U180") (pin "4") (pinfunction "DO_4") (pintype "passive"))
      (node (ref "U181") (pin "2") (pinfunction "DI_2") (pintype "passive"))
    )
    (net (code "124") (name "Net-(U181-DO)") (class "Default")
      (node (ref "U181") (pin "4") (pinfunction "DO_4") (pintype "passive"))
      (node (ref "U182") (pin "4") (pinfunction "DIN_4") (pintype "passive"))
    )
    (net (code "125") (name "Net-(U182-DOUT)") (class "Default")
      (node (ref "U182") (pin "2") (pinfunction "DOUT_2") (pintype "passive"))
      (node (ref "U183") (pin "4") (pinfunction "DIN_4") (pintype "passive"))
    )
    (net (code "126") (name "Net-(U183-DOUT)") (class "Default")
      (node (ref "U183") (pin "2") (pinfunction "DOUT_2") (pintype "passive"))
      (node (ref "U184") (pin "4") (pinfunction "DIN_4") (pintype "passive"))
    )
    (net (code "127") (name "Net-(U184-DOUT)") (class "Default")
      (node (ref "U184") (pin "2") (pinfunction "DOUT_2") (pintype "passive"))
      (node (ref "U185") (pin "4") (pinfunction "DIN_4") (pintype "passive"))
    )
    (net (code "128") (name "Net-(U185-DOUT)") (class "Default")
      (node (ref "U185") (pin "2") (pinfunction "DOUT_2") (pintype "passive"))
      (node (ref "U186") (pin "4") (pinfunction "DIN_4") (pintype "passive"))
    )
    (net (code "129") (name "Net-(U186-DOUT)") (class "Default")
      (node (ref "U186") (pin "2") (pinfunction "DOUT_2") (pintype "passive"))
      (node (ref "U187") (pin "4") (pinfunction "DIN_4") (pintype "passive"))
    )
    (net (code "130") (name "Net-(U187-DOUT)") (class "Default")
      (node (ref "U187") (pin "2") (pinfunction "DOUT_2") (pintype "passive"))
      (node (ref "U188") (pin "4") (pinfunction "DIN_4") (pintype "passive"))
    )
    (net (code "131") (name "Net-(U188-DOUT)") (class "Default")
      (node (ref "U188") (pin "2") (pinfunction "DOUT_2") (pintype "passive"))
      (node (ref "U189") (pin "4") (pinfunction "DIN_4") (pintype "passive"))
    )
    (net (code "132") (name "Net-(U198-DOUT)") (class "Default")
      (node (ref "U198") (pin "2") (pinfunction "DOUT_2") (pintype "passive"))
      (node (ref "U199") (pin "4") (pinfunction "DIN_4") (pintype "passive"))
    )
    (net (code "133") (name "Net-(U199-DOUT)") (class "Default")
      (node (ref "U199") (pin "2") (pinfunction "DOUT_2") (pintype "passive"))
      (node (ref "U200") (pin "4") (pinfunction "DIN_4") (pintype "passive"))
    )
    (net (code "134") (name "Net-(U200-DOUT)") (class "Default")
      (node (ref "U200") (pin "2") (pinfunction "DOUT_2") (pintype "passive"))
      (node (ref "U201") (pin "4") (pinfunction "DIN_4") (pintype "passive"))
    )
    (net (code "135") (name "Net-(U201-DOUT)") (class "Default")
      (node (ref "U201") (pin "2") (pinfunction "DOUT_2") (pintype "passive"))
      (node (ref "U202") (pin "4") (pinfunction "DIN_4") (pintype "passive"))
    )
    (net (code "136") (name "Net-(U202-DOUT)") (class "Default")
      (node (ref "U202") (pin "2") (pinfunction "DOUT_2") (pintype "passive"))
      (node (ref "U203") (pin "4") (pinfunction "DIN_4") (pintype "passive"))
    )
    (net (code "137") (name "Net-(U203-DOUT)") (class "Default")
      (node (ref "U203") (pin "2") (pinfunction "DOUT_2") (pintype "passive"))
      (node (ref "U204") (pin "4") (pinfunction "DIN_4") (pintype "passive"))
    )
    (net (code "138") (name "Net-(U204-DOUT)") (class "Default")
      (node (ref "U204") (pin "2") (pinfunction "DOUT_2") (pintype "passive"))
      (node (ref "U205") (pin "4") (pinfunction "DIN_4") (pintype "passive"))
    )
    (net (code "139") (name "Net-(U205-DOUT)") (class "Default")
      (node (ref "U205") (pin "2") (pinfunction "DOUT_2") (pintype "passive"))
      (node (ref "U206") (pin "4") (pinfunction "DIN_4") (pintype "passive"))
    )
    (net (code "140") (name "unconnected-(SW100-C-Pad1)") (class "Default")
      (node (ref "SW100") (pin "1") (pinfunction "C_1") (pintype "passive+no_connect"))
    )
    (net (code "141") (name "unconnected-(SW101-C-Pad1)") (class "Default")
      (node (ref "SW101") (pin "1") (pinfunction "C_1") (pintype "passive+no_connect"))
    )
    (net (code "142") (name "unconnected-(U206-DOUT-Pad2)") (class "Default")
      (node (ref "U206") (pin "2") (pinfunction "DOUT_2") (pintype "passive+no_connect"))
    )
  )
)
